# debug_backplane.net
KiCad netlist of a schematic drawn in EAGLE
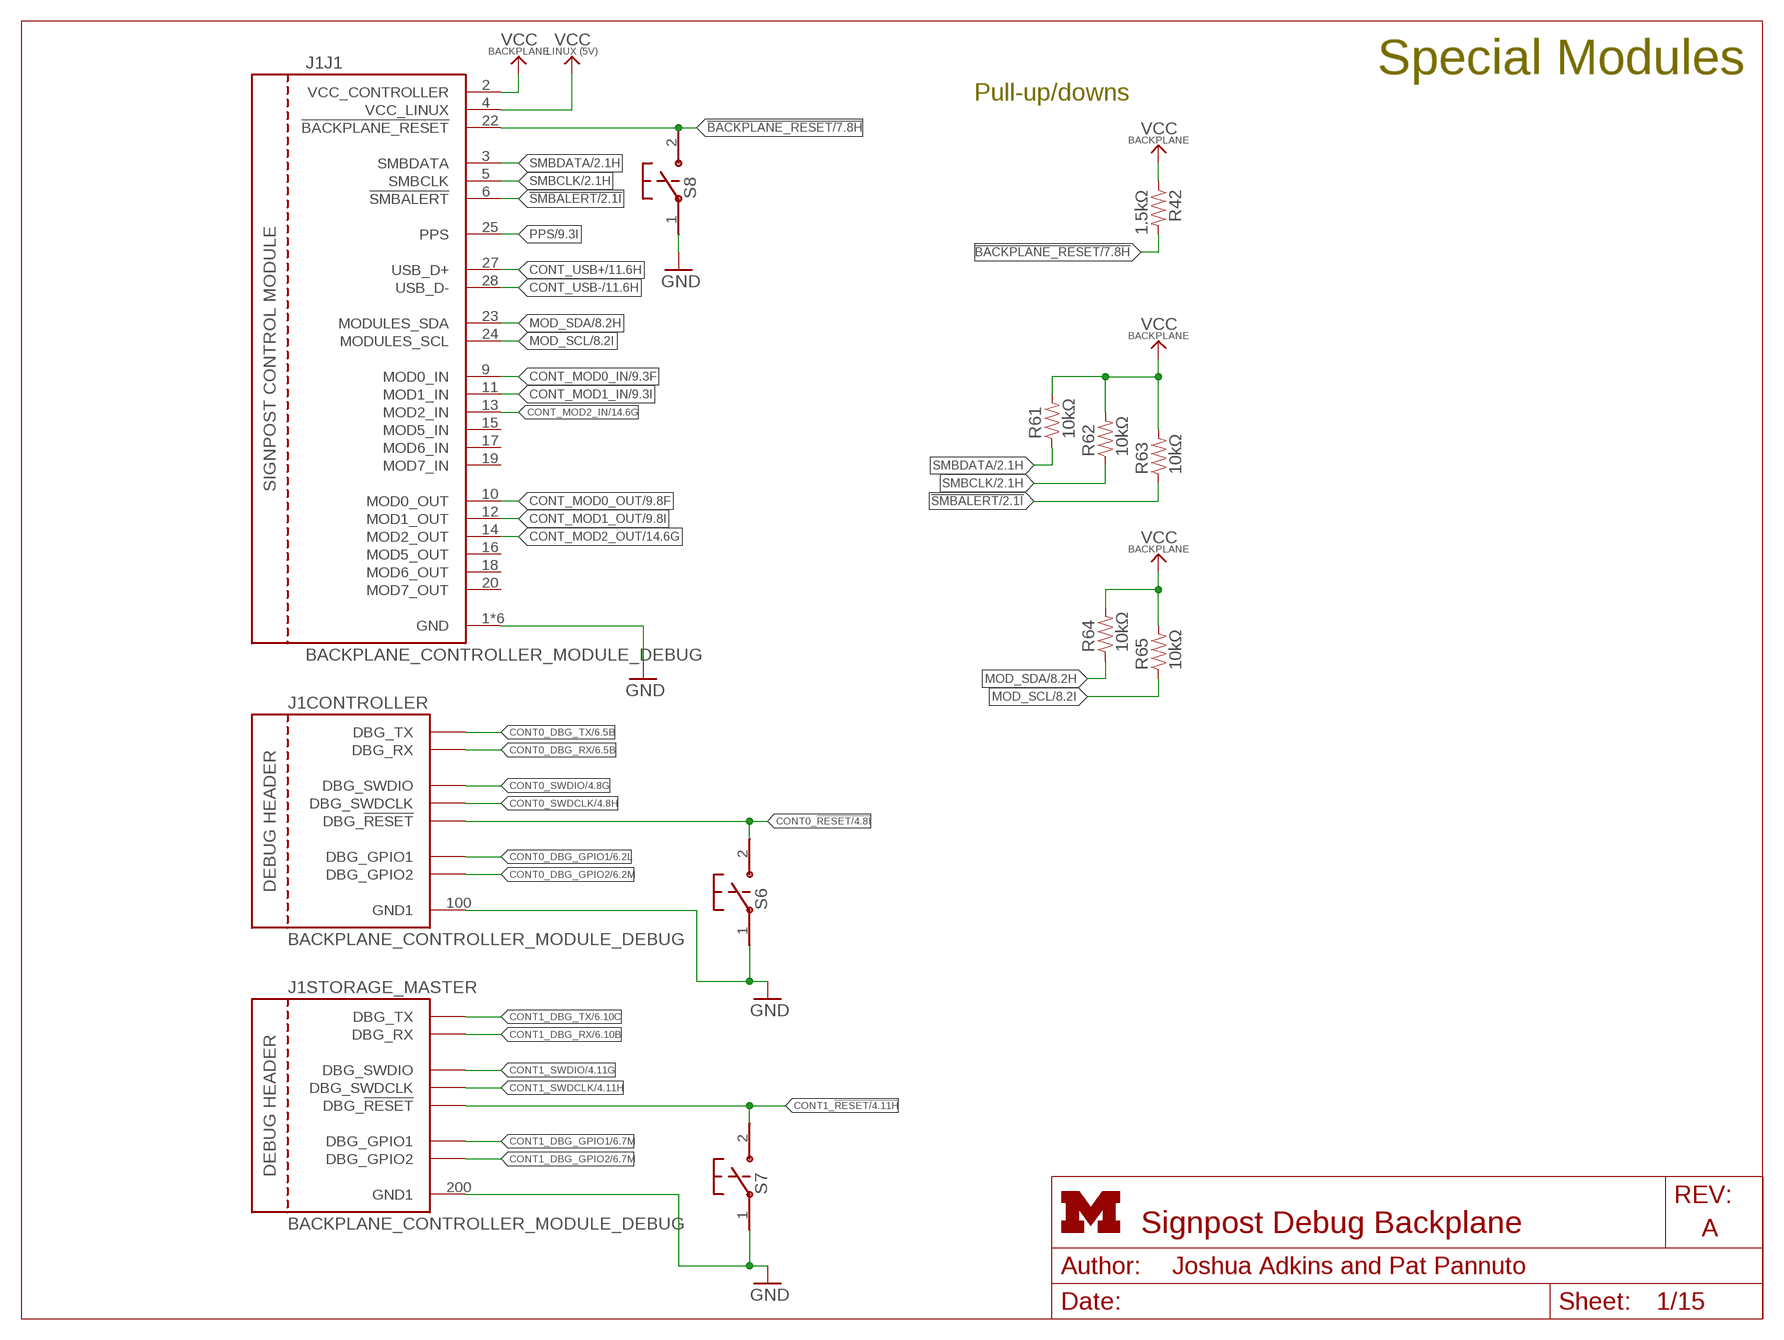
[diagram p0: schematic, sheet 1]
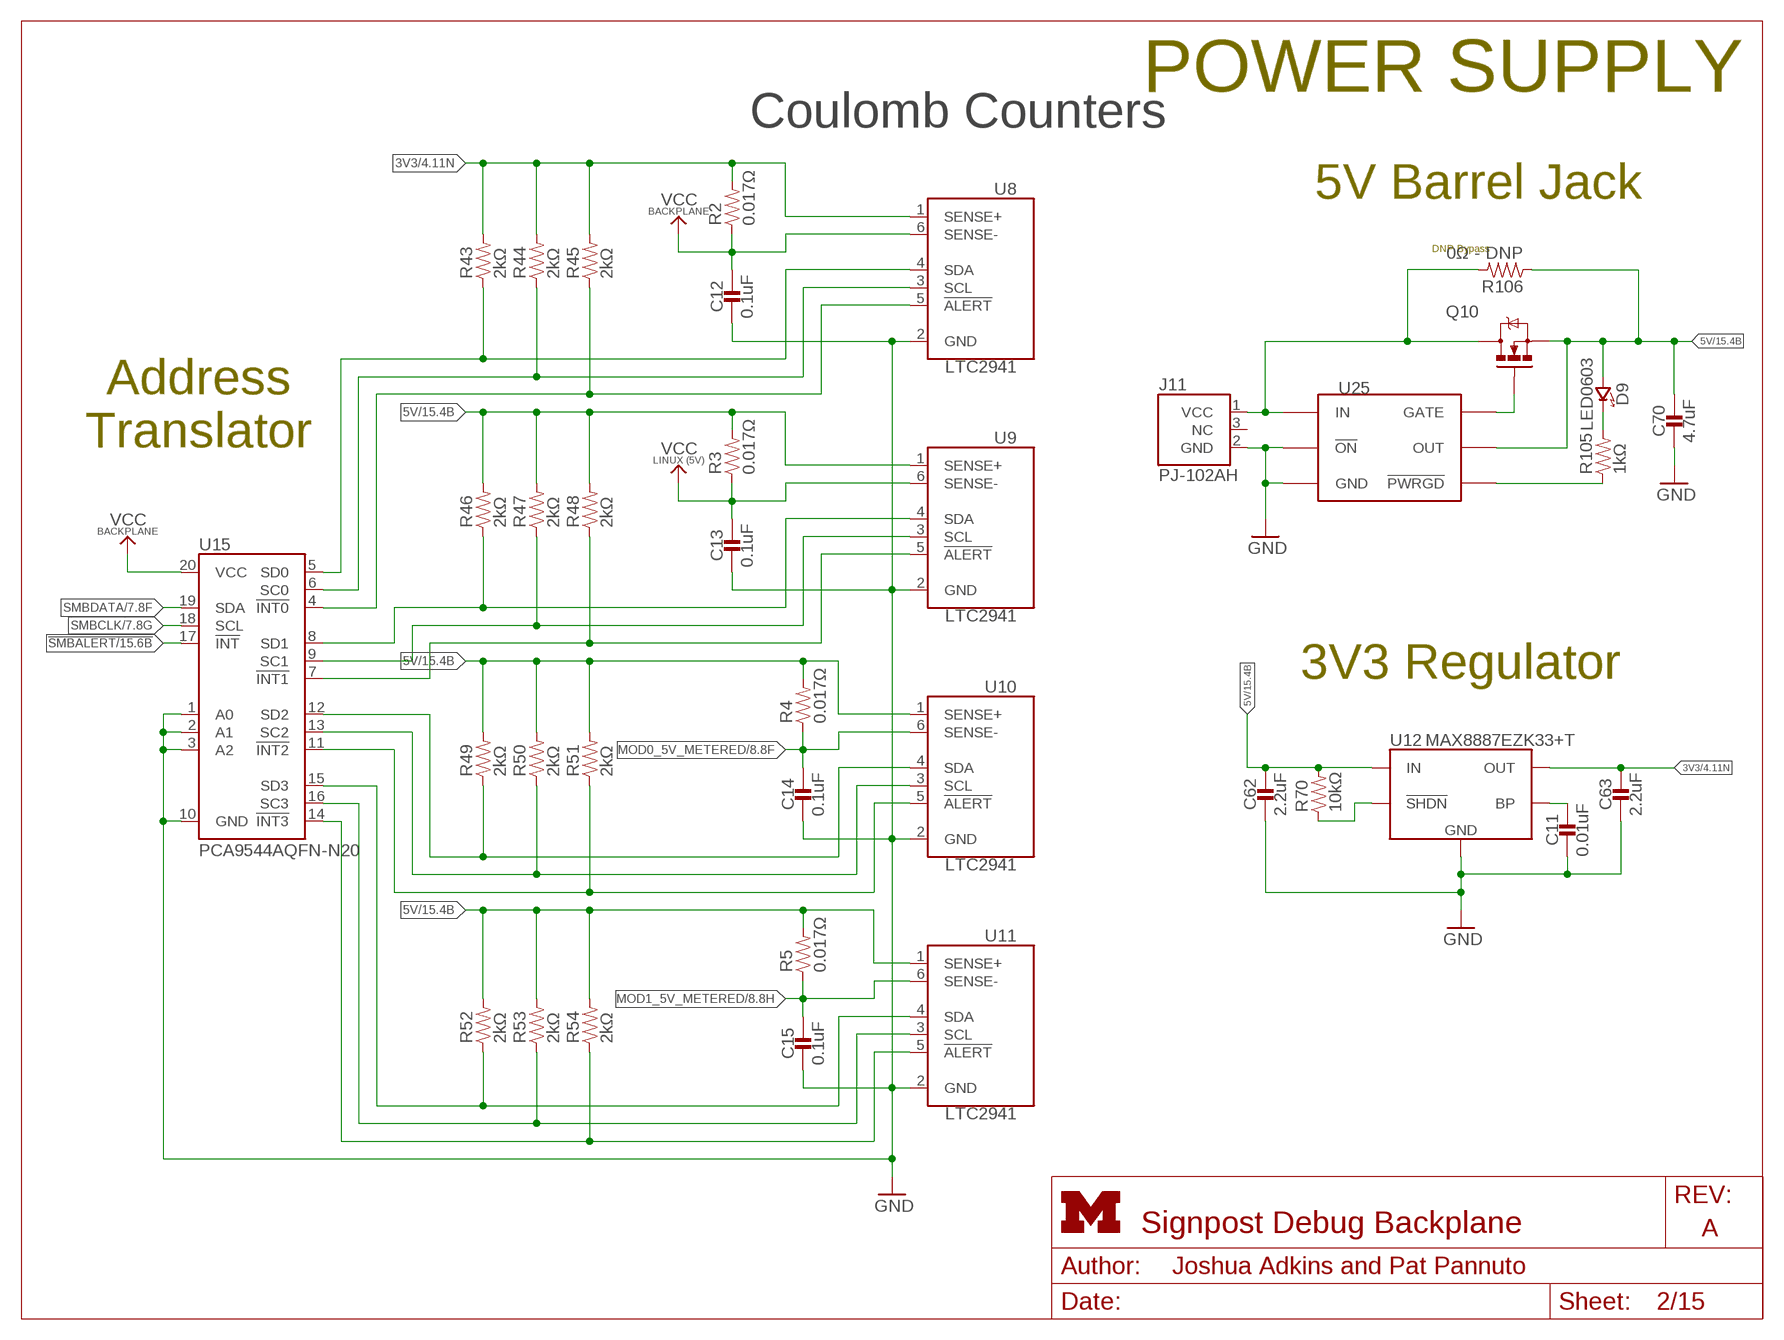
[diagram p1: schematic, sheet 2]
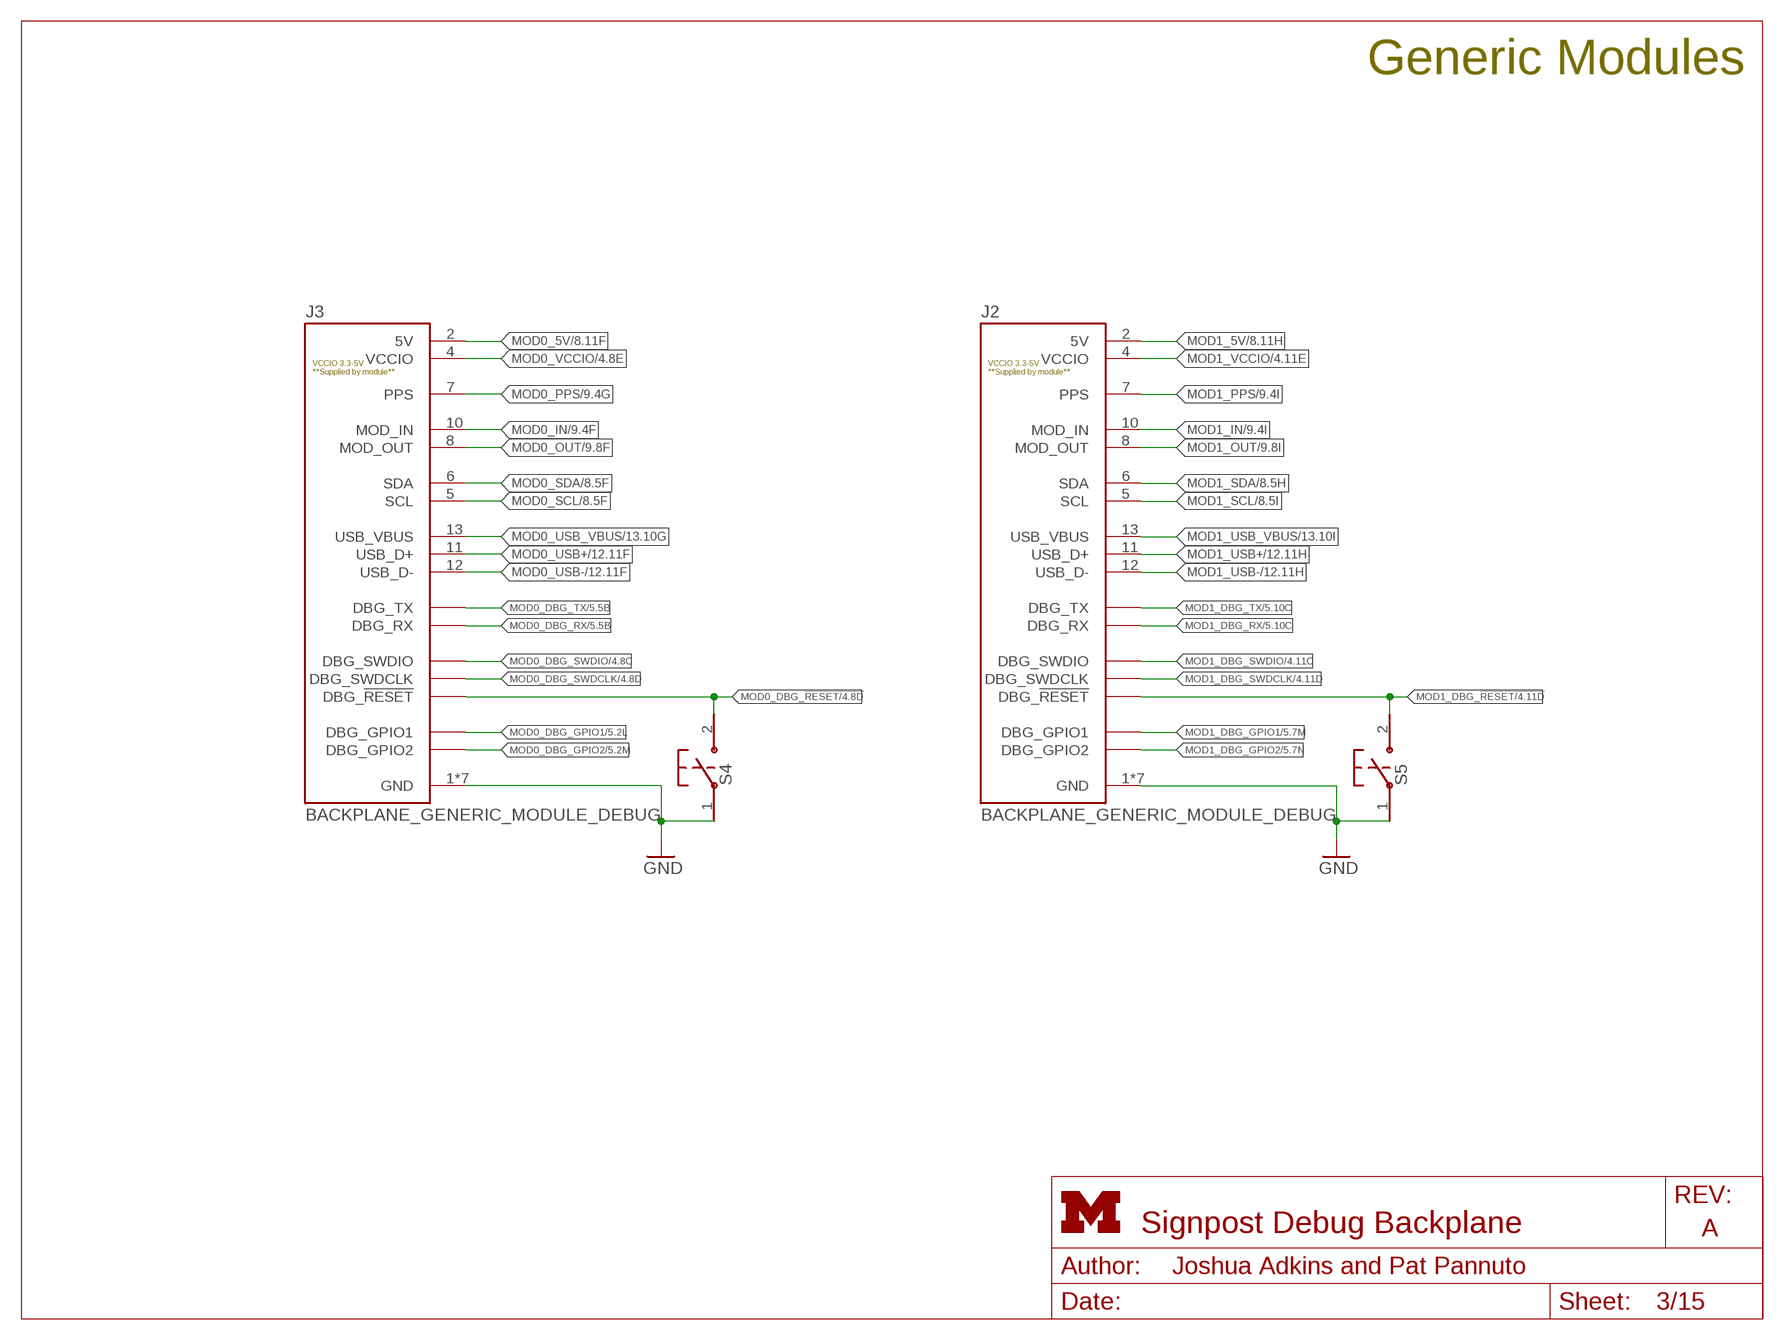
[diagram p2: schematic, sheet 3]
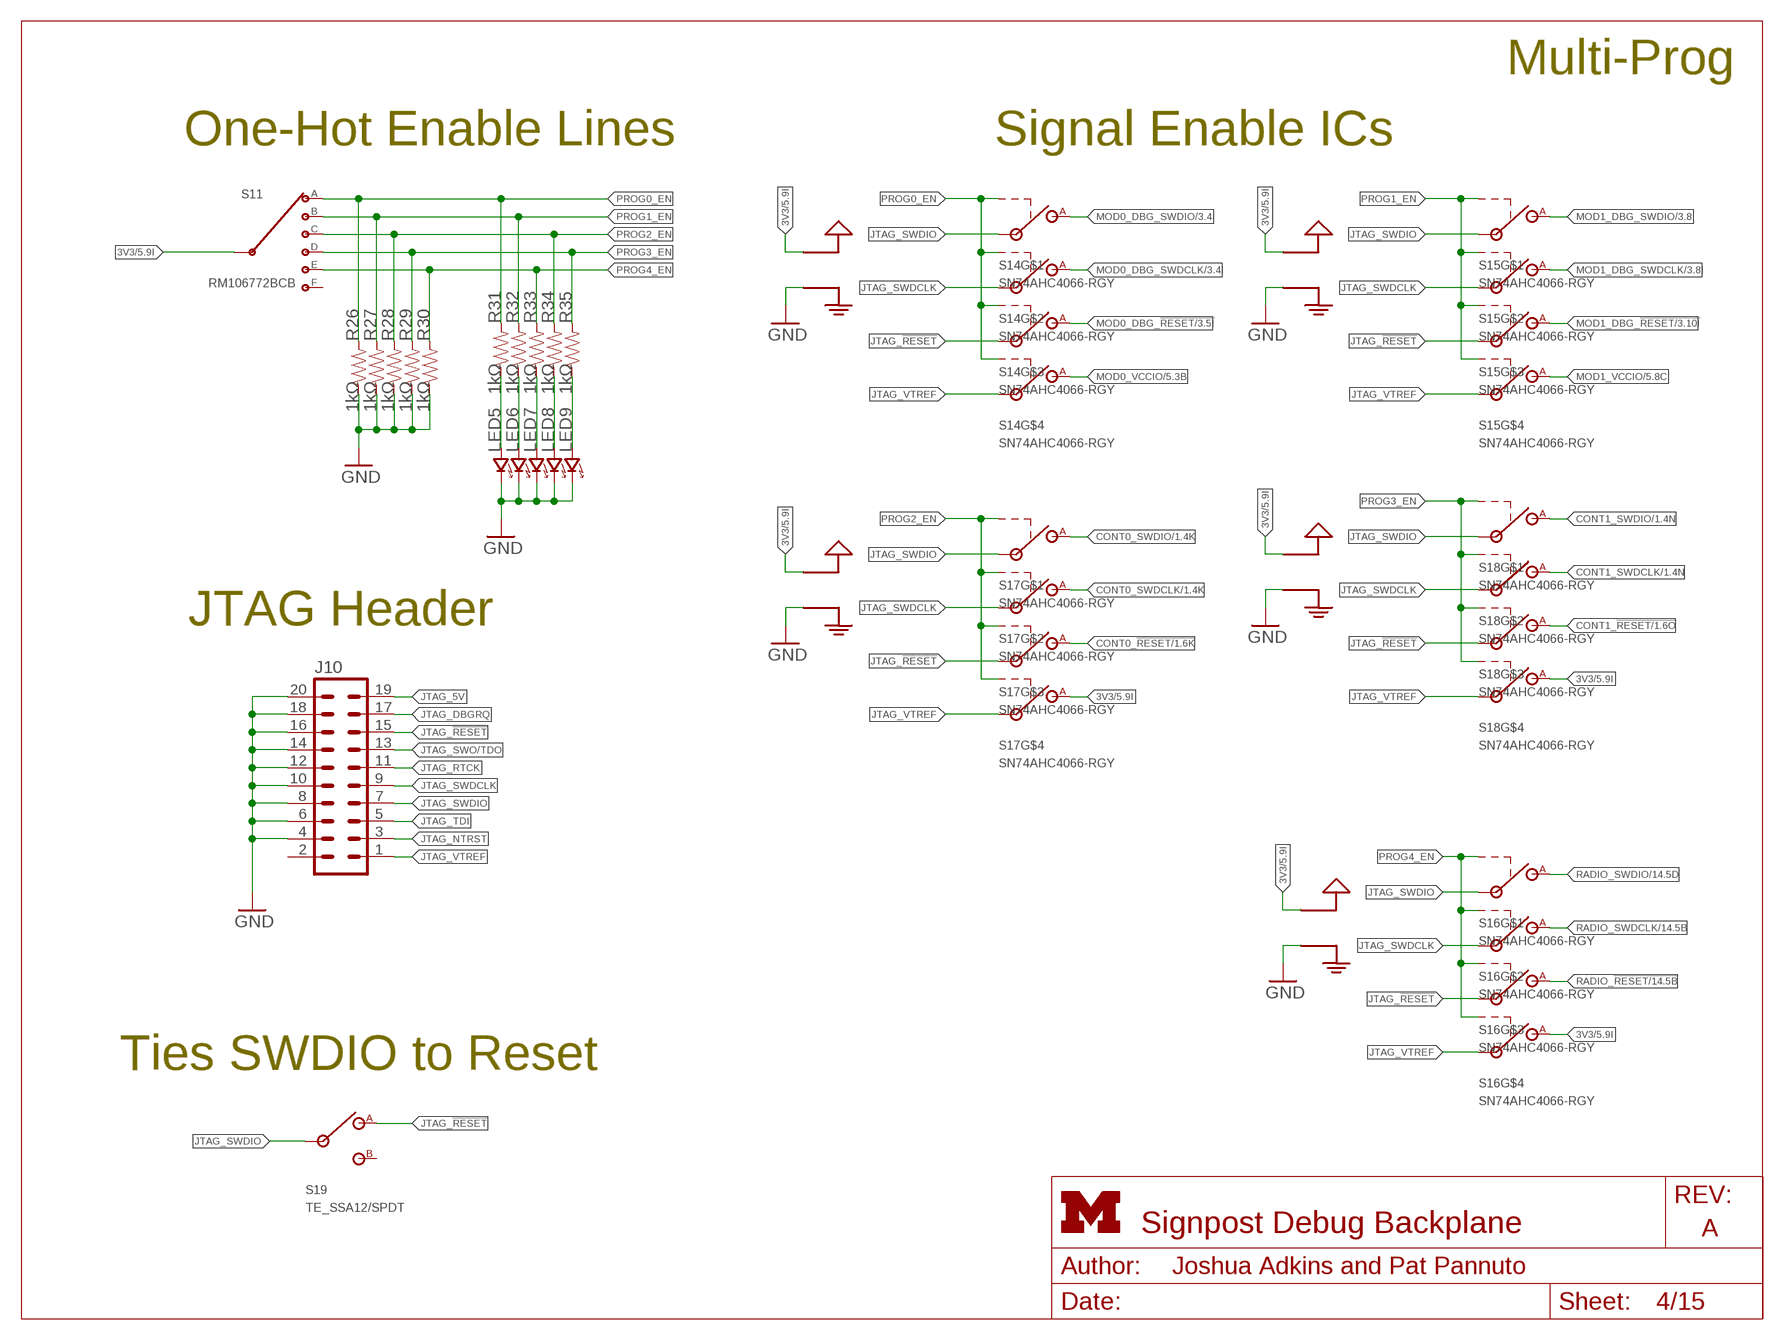
[diagram p3: schematic, sheet 4]
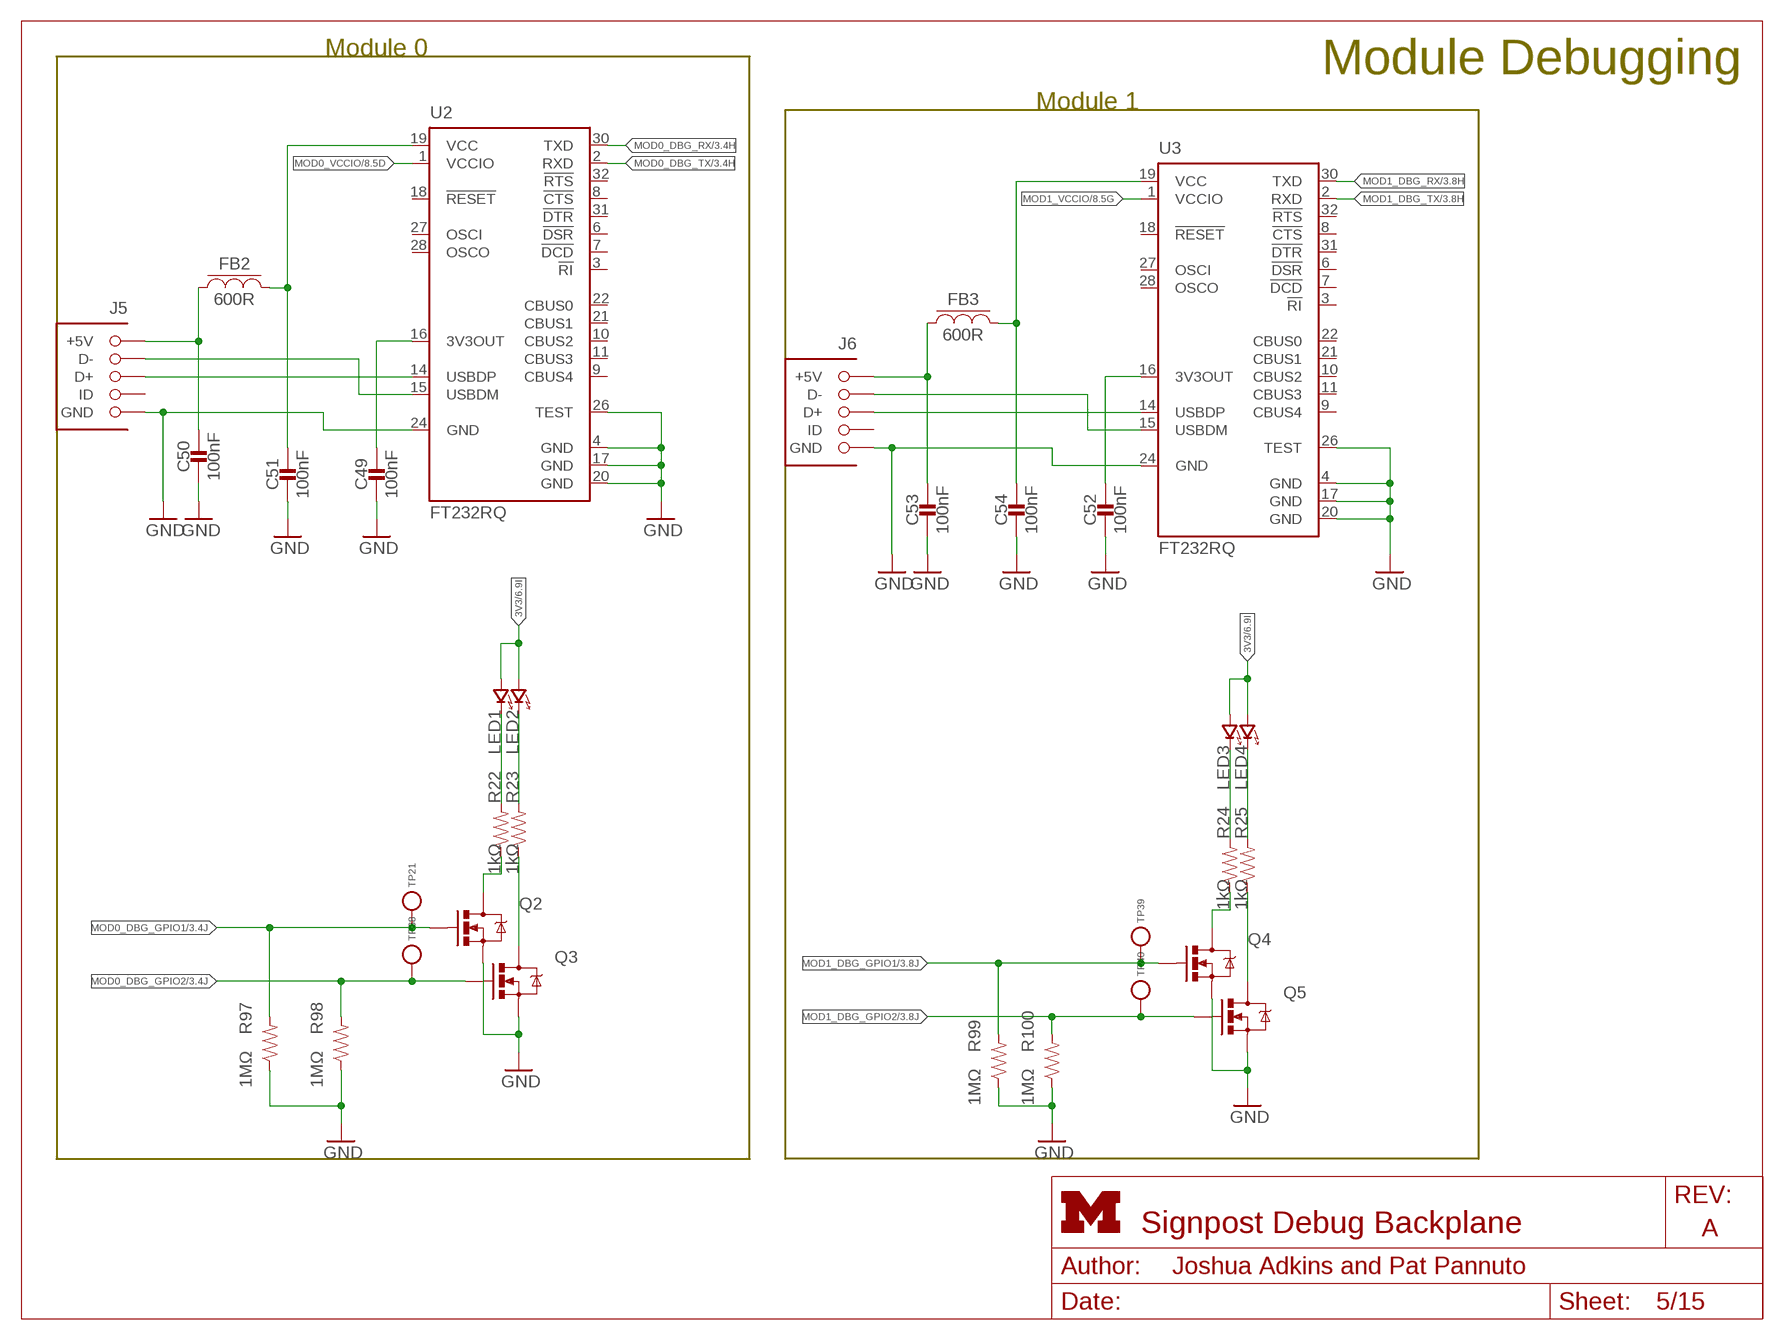
[diagram p4: schematic, sheet 5]
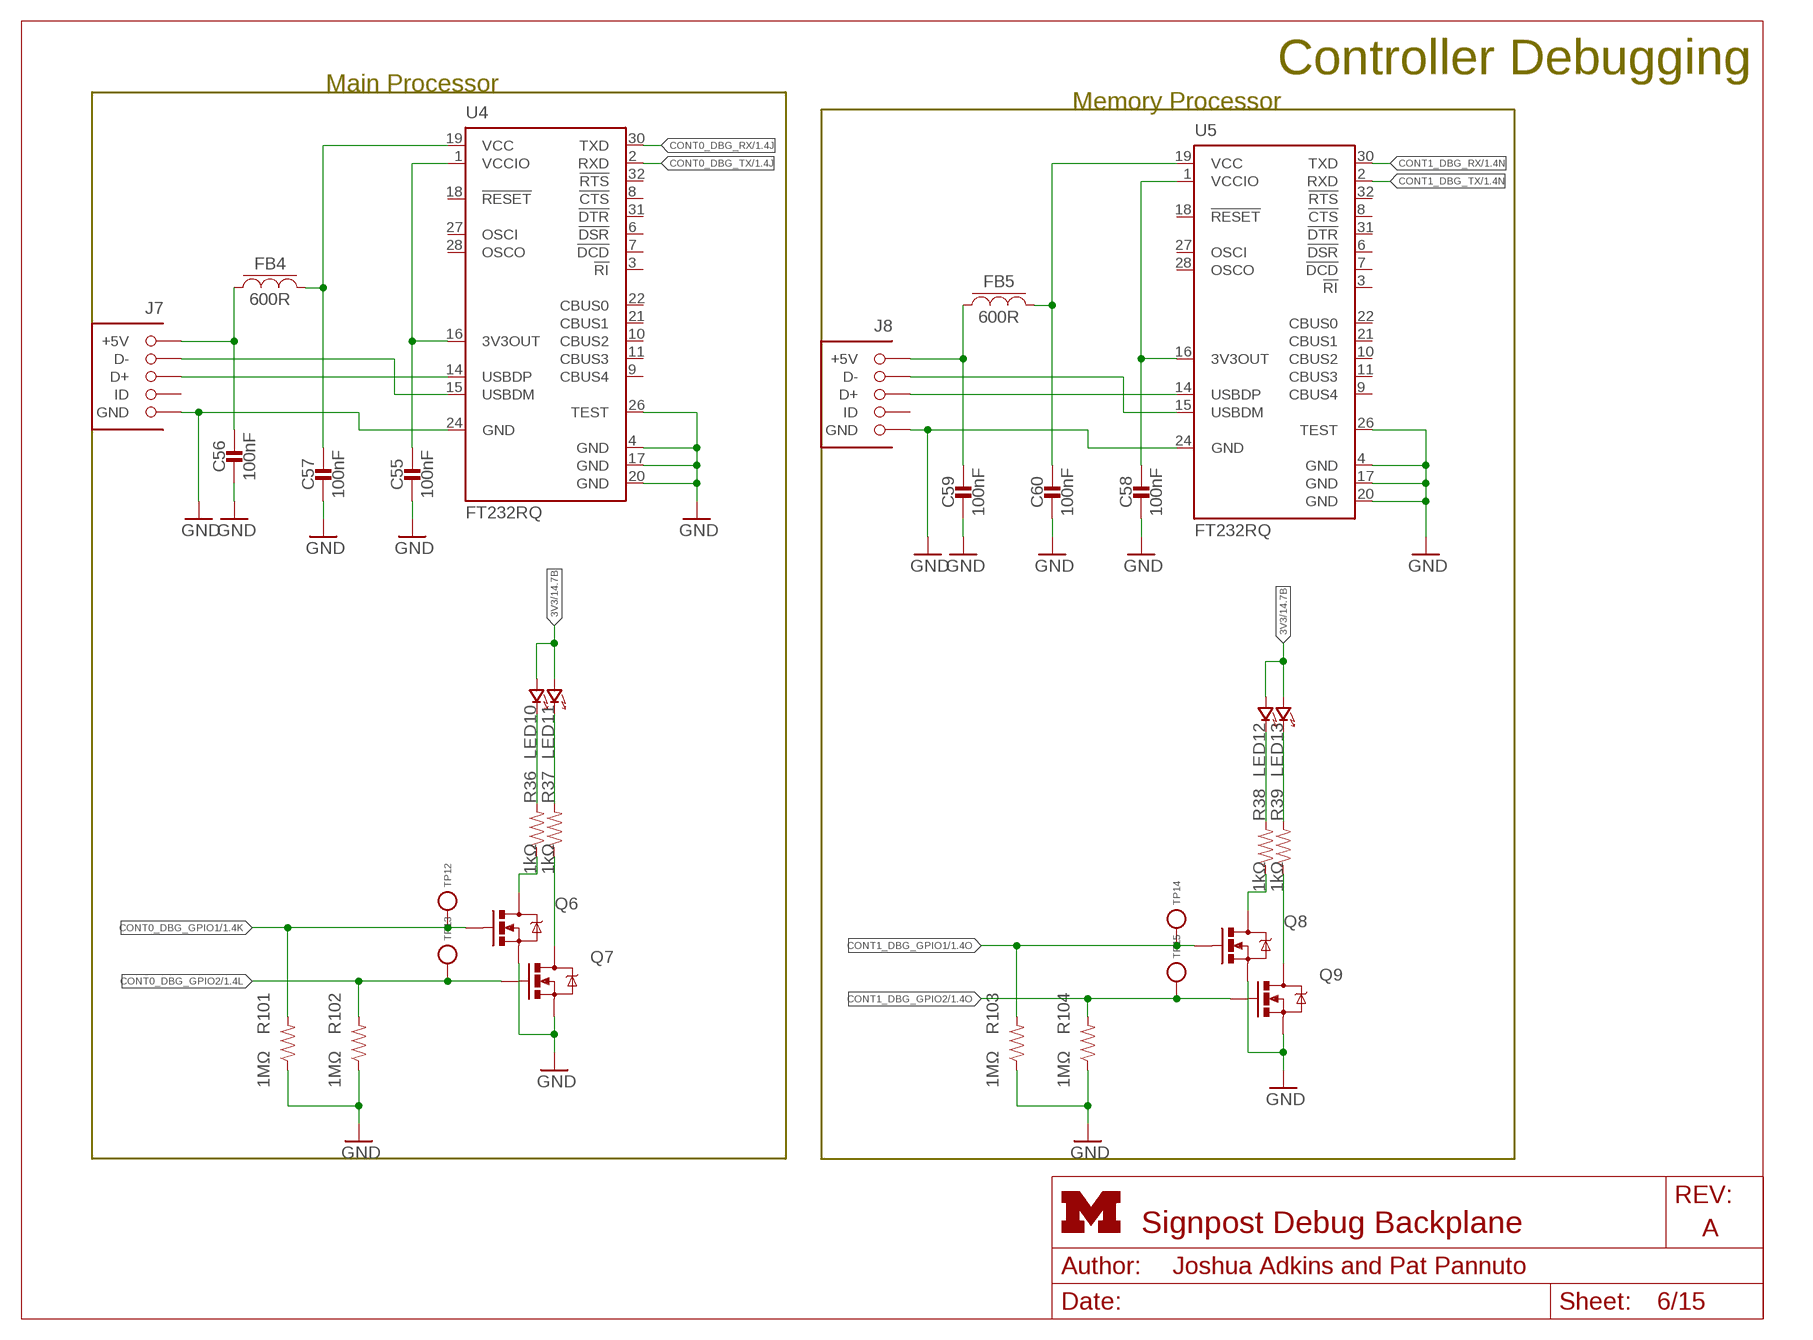
[diagram p5: schematic, sheet 6]
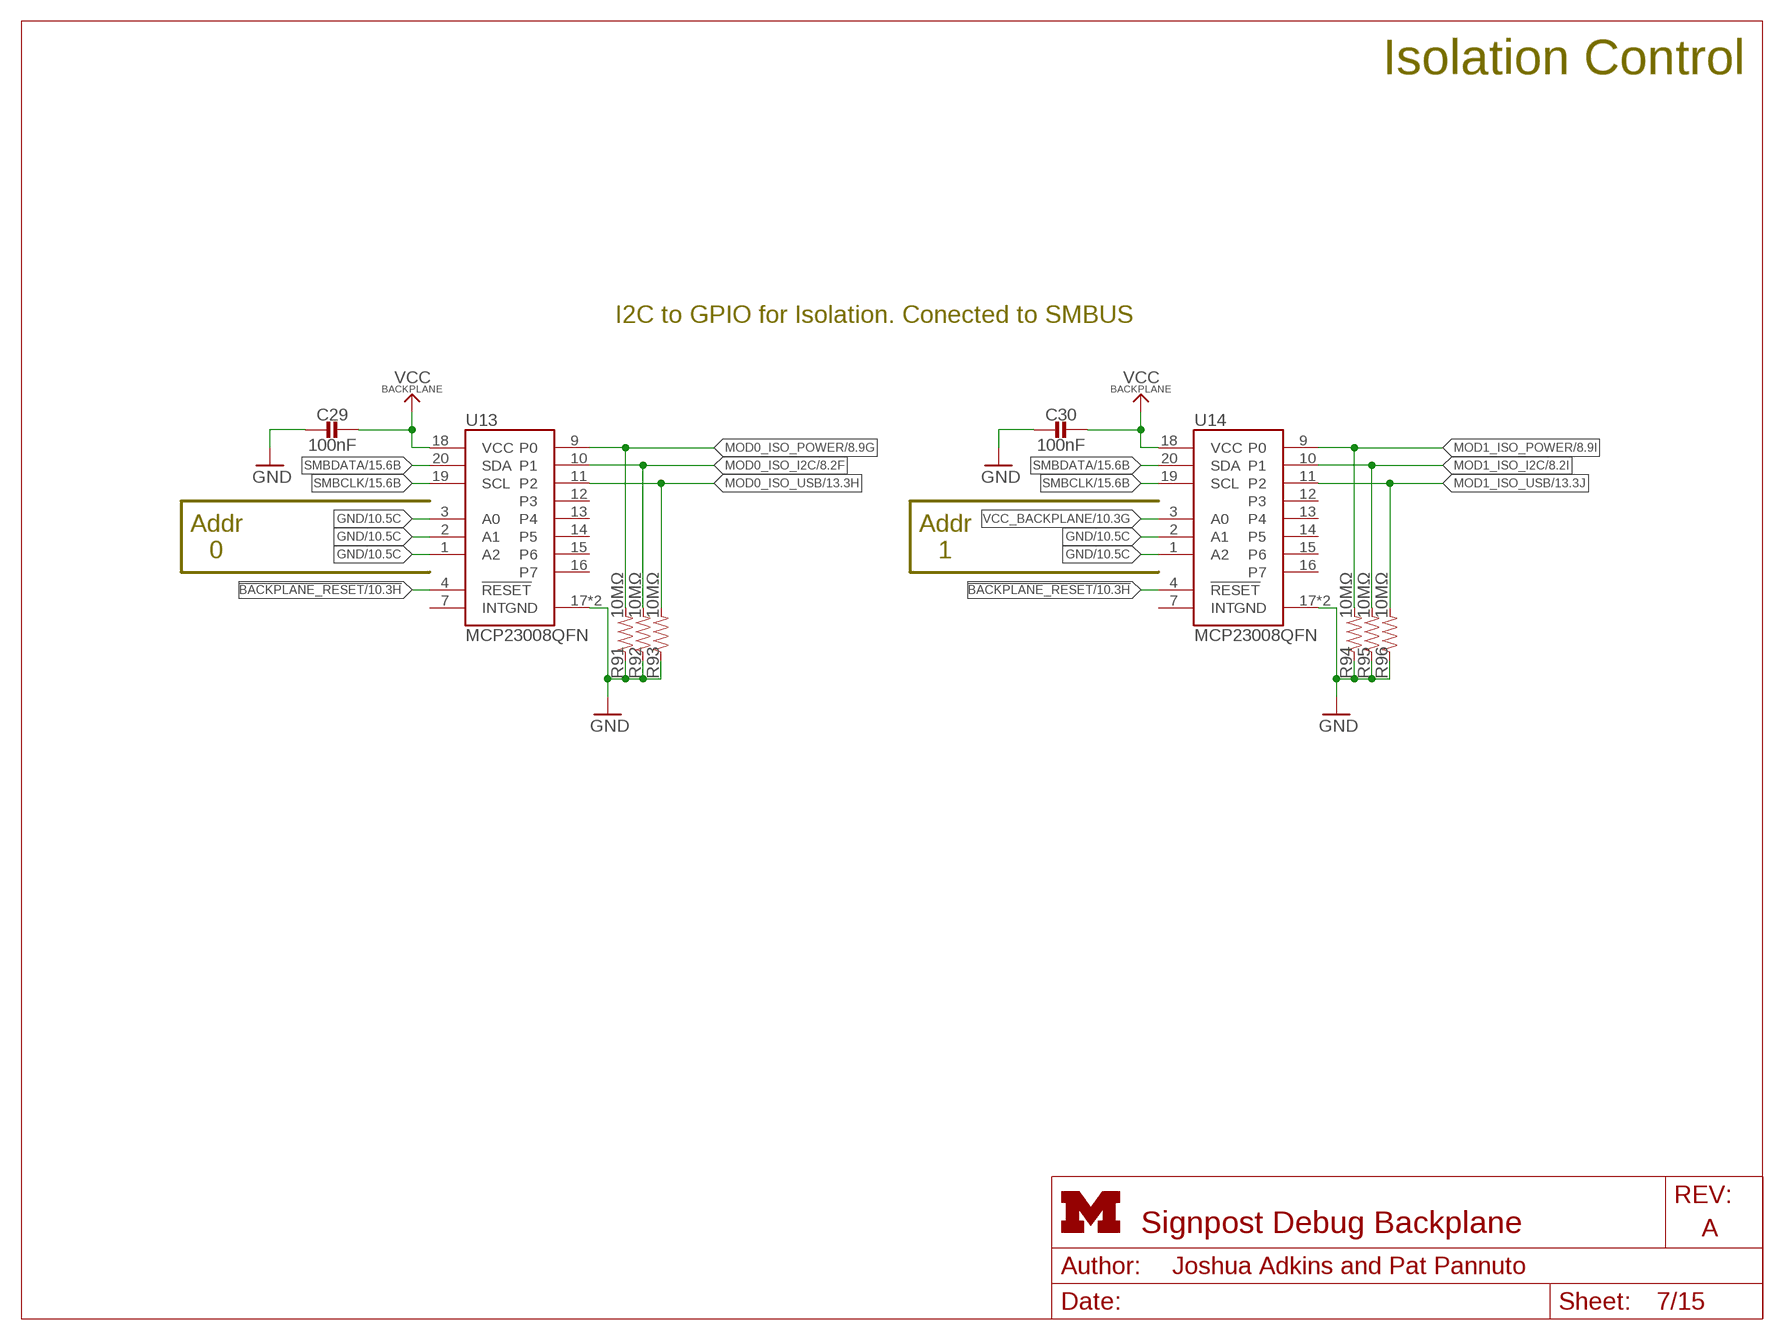
[diagram p6: schematic, sheet 7]
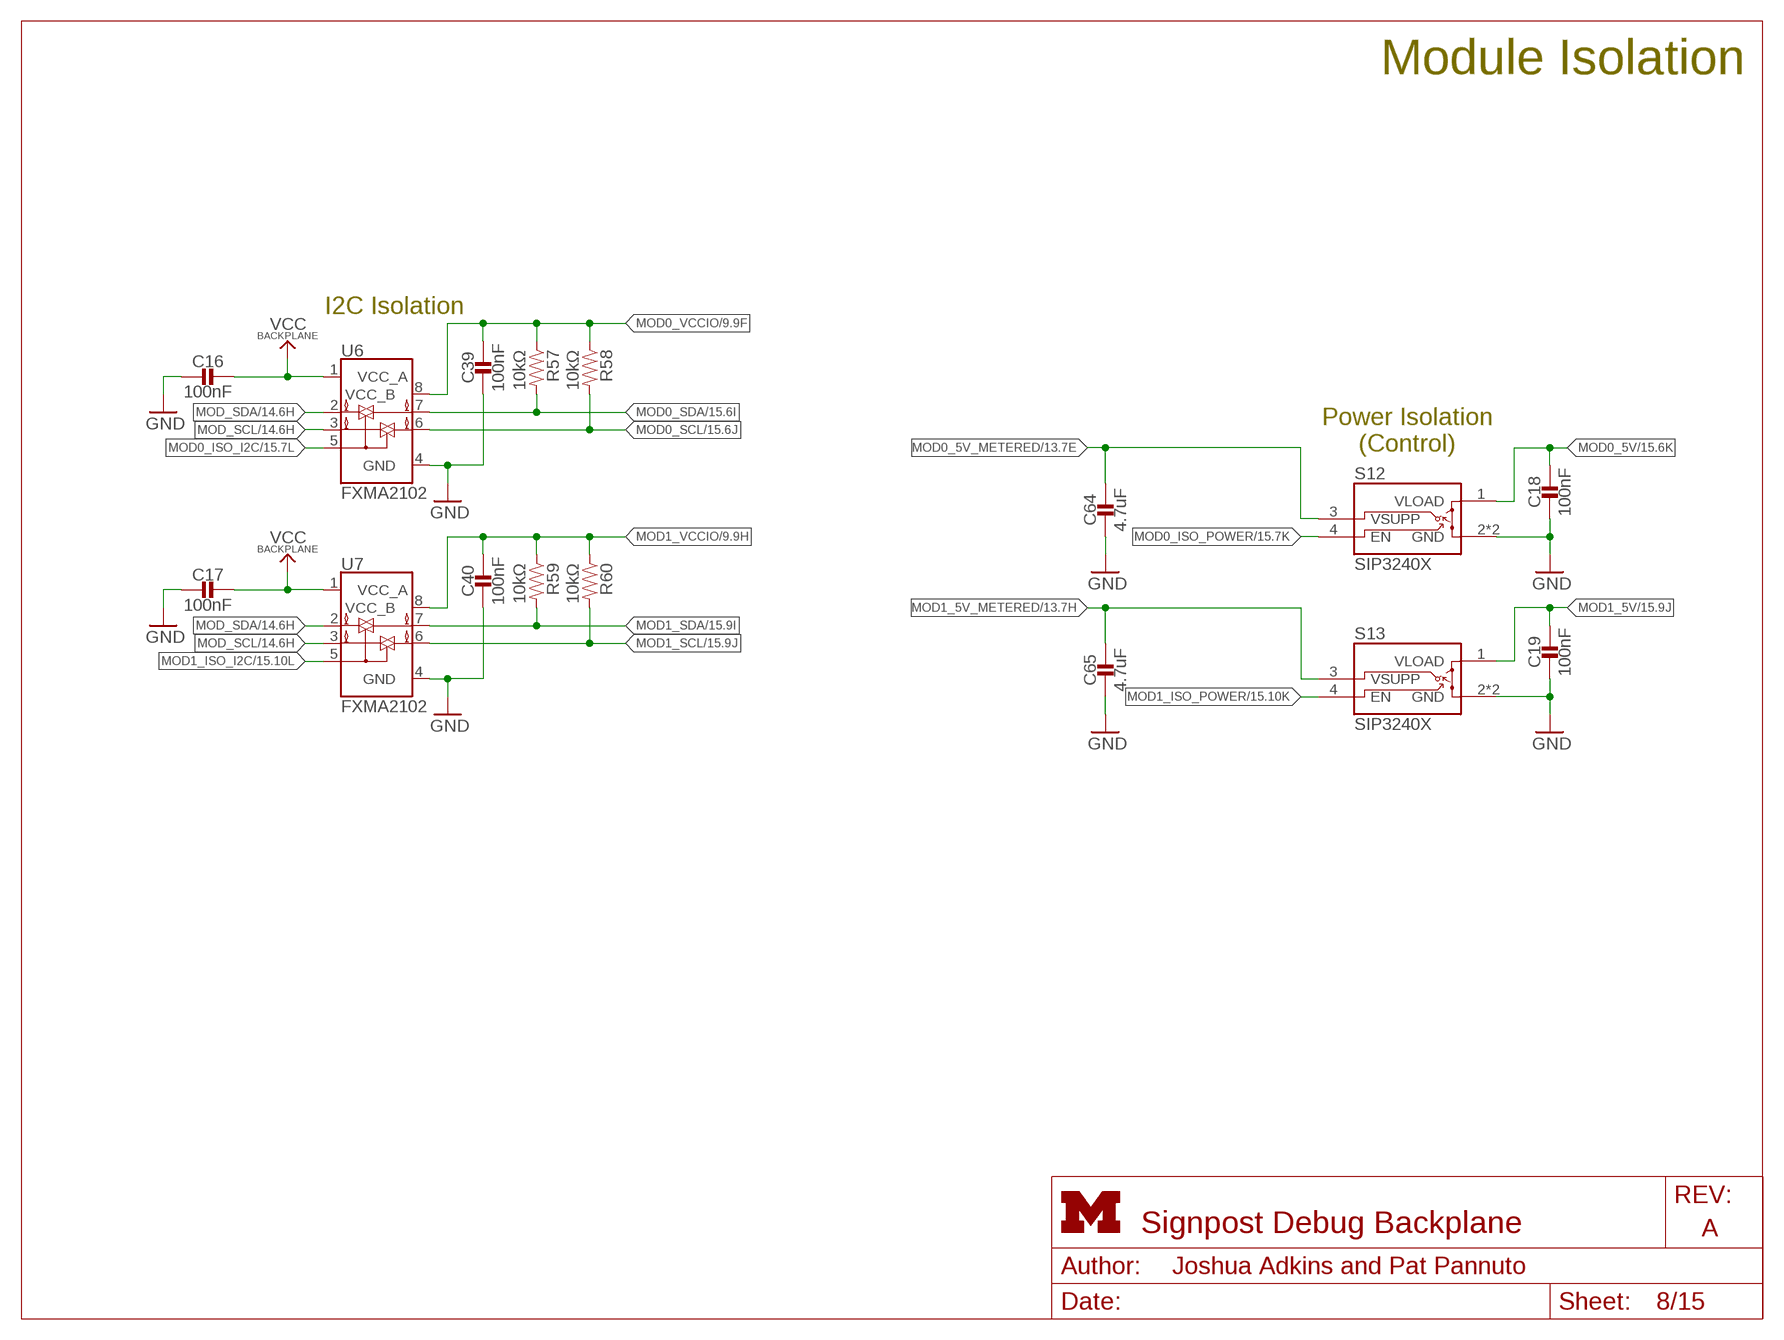
[diagram p7: schematic, sheet 8]
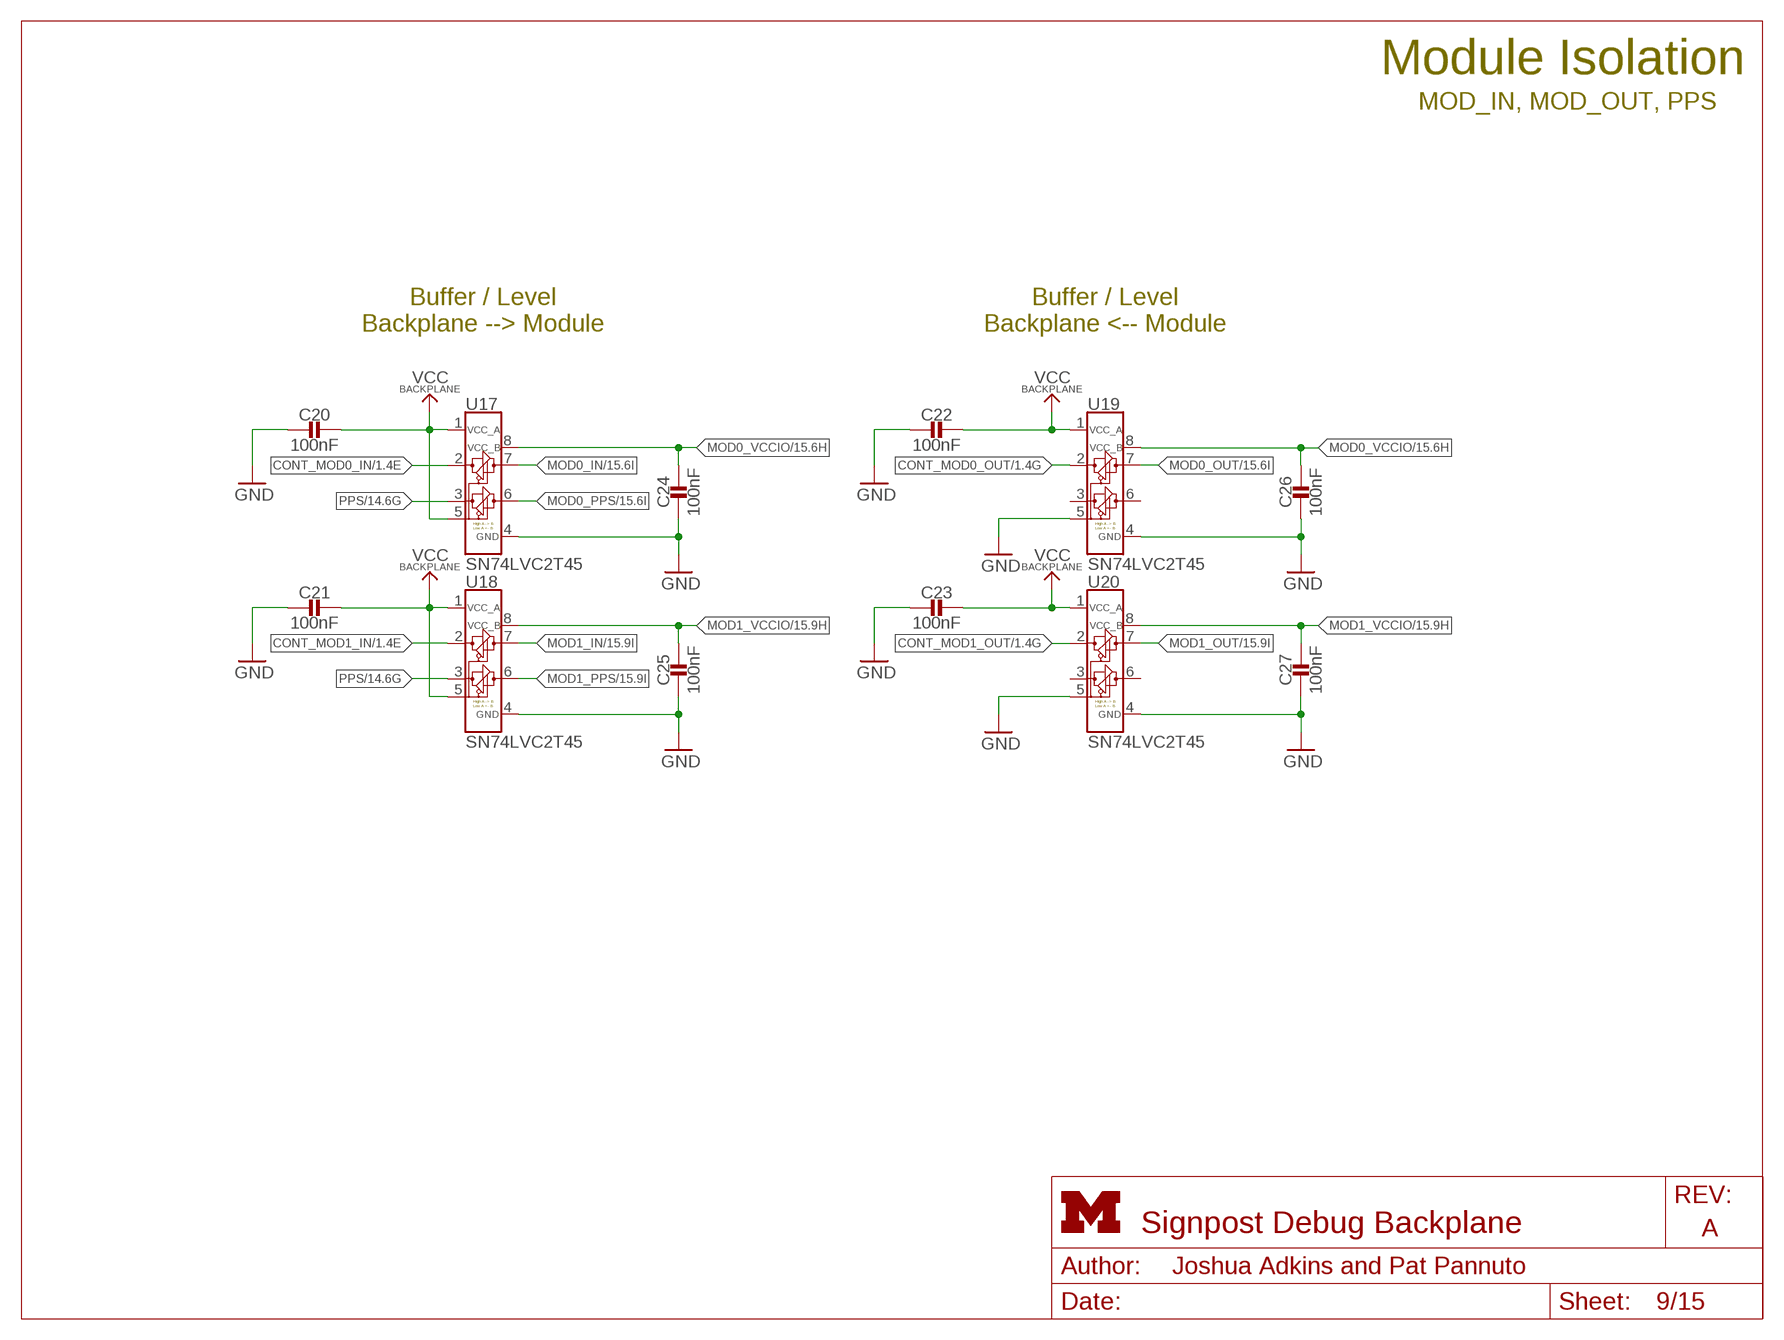
[diagram p8: schematic, sheet 9]
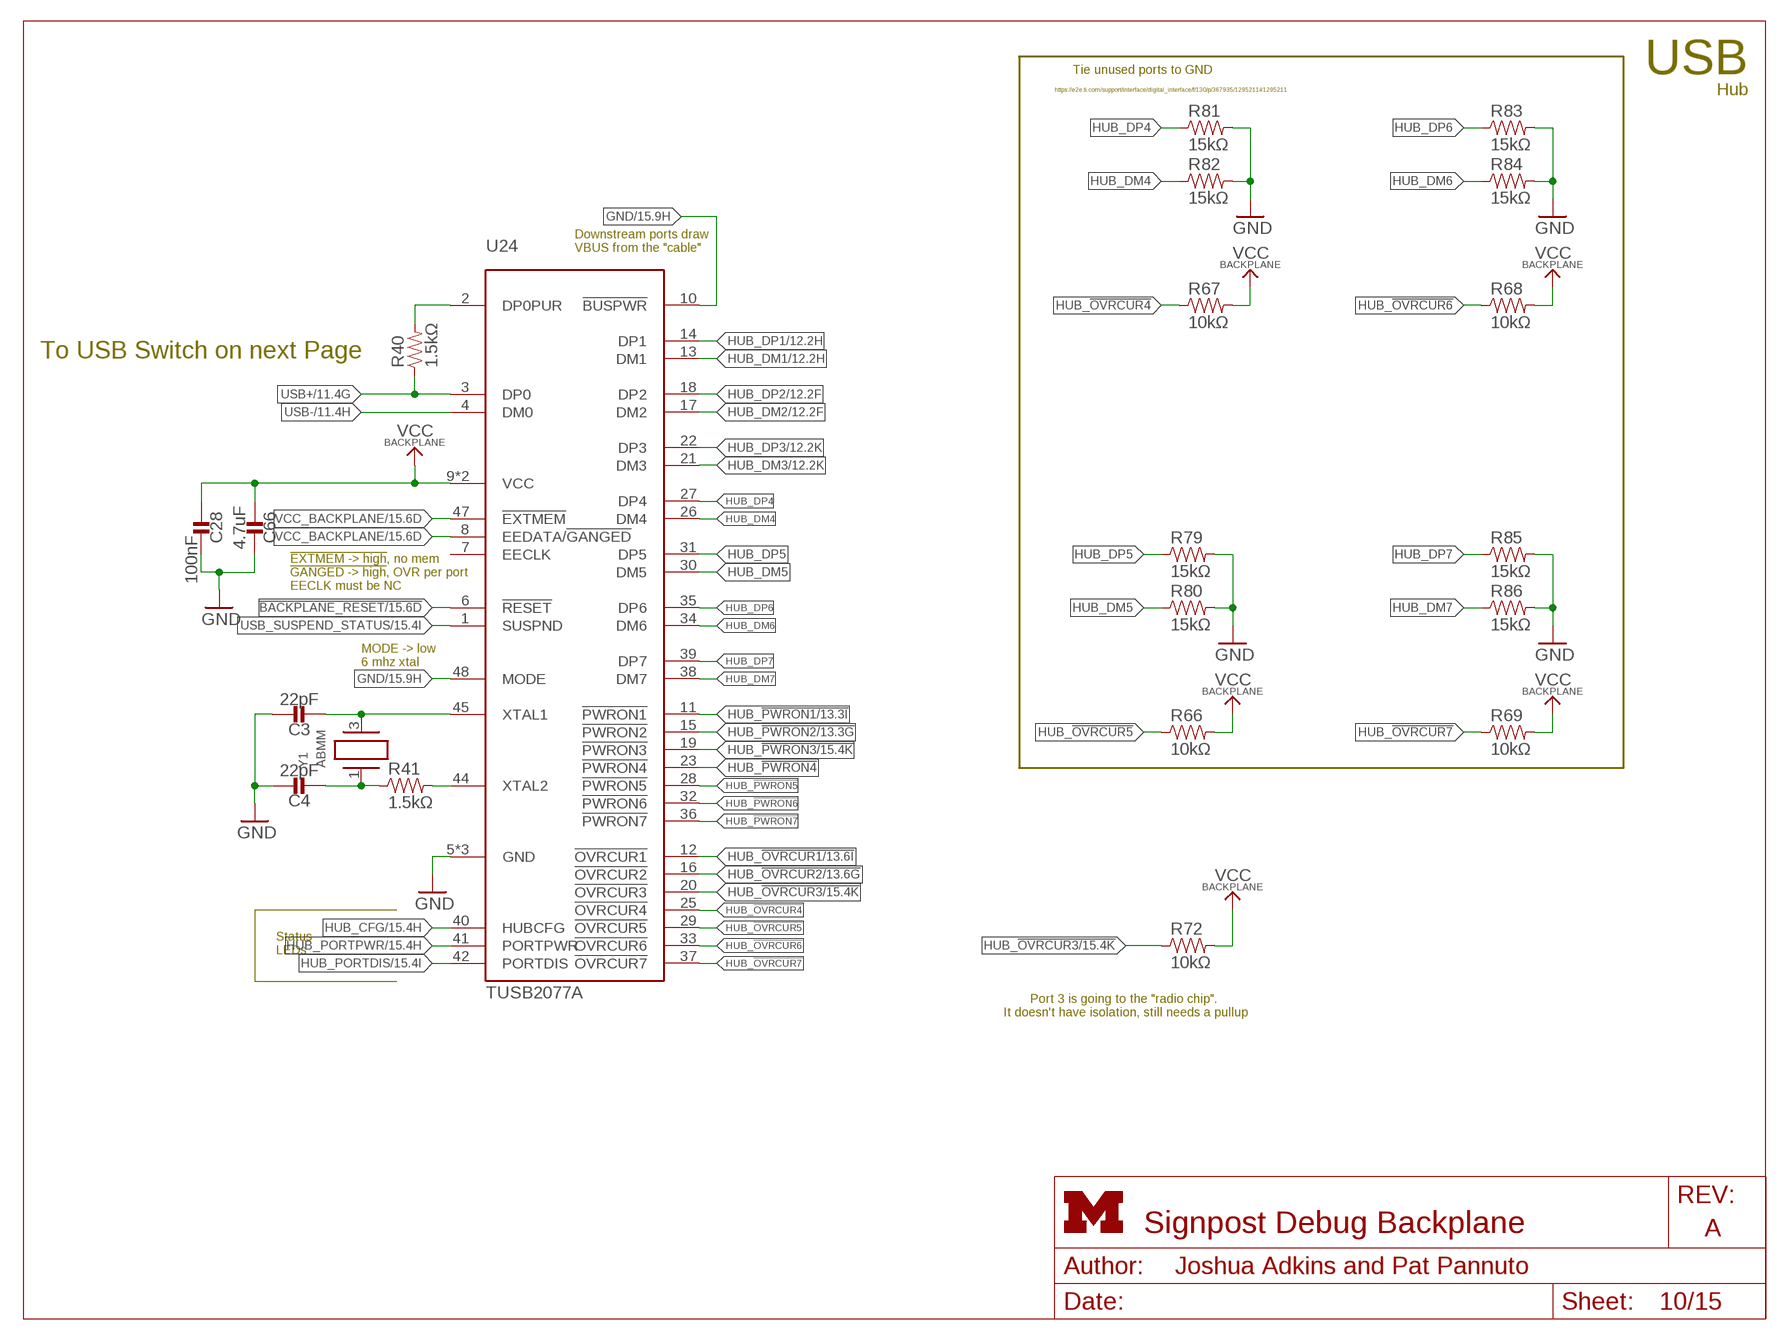
[diagram p9: schematic, sheet 10]
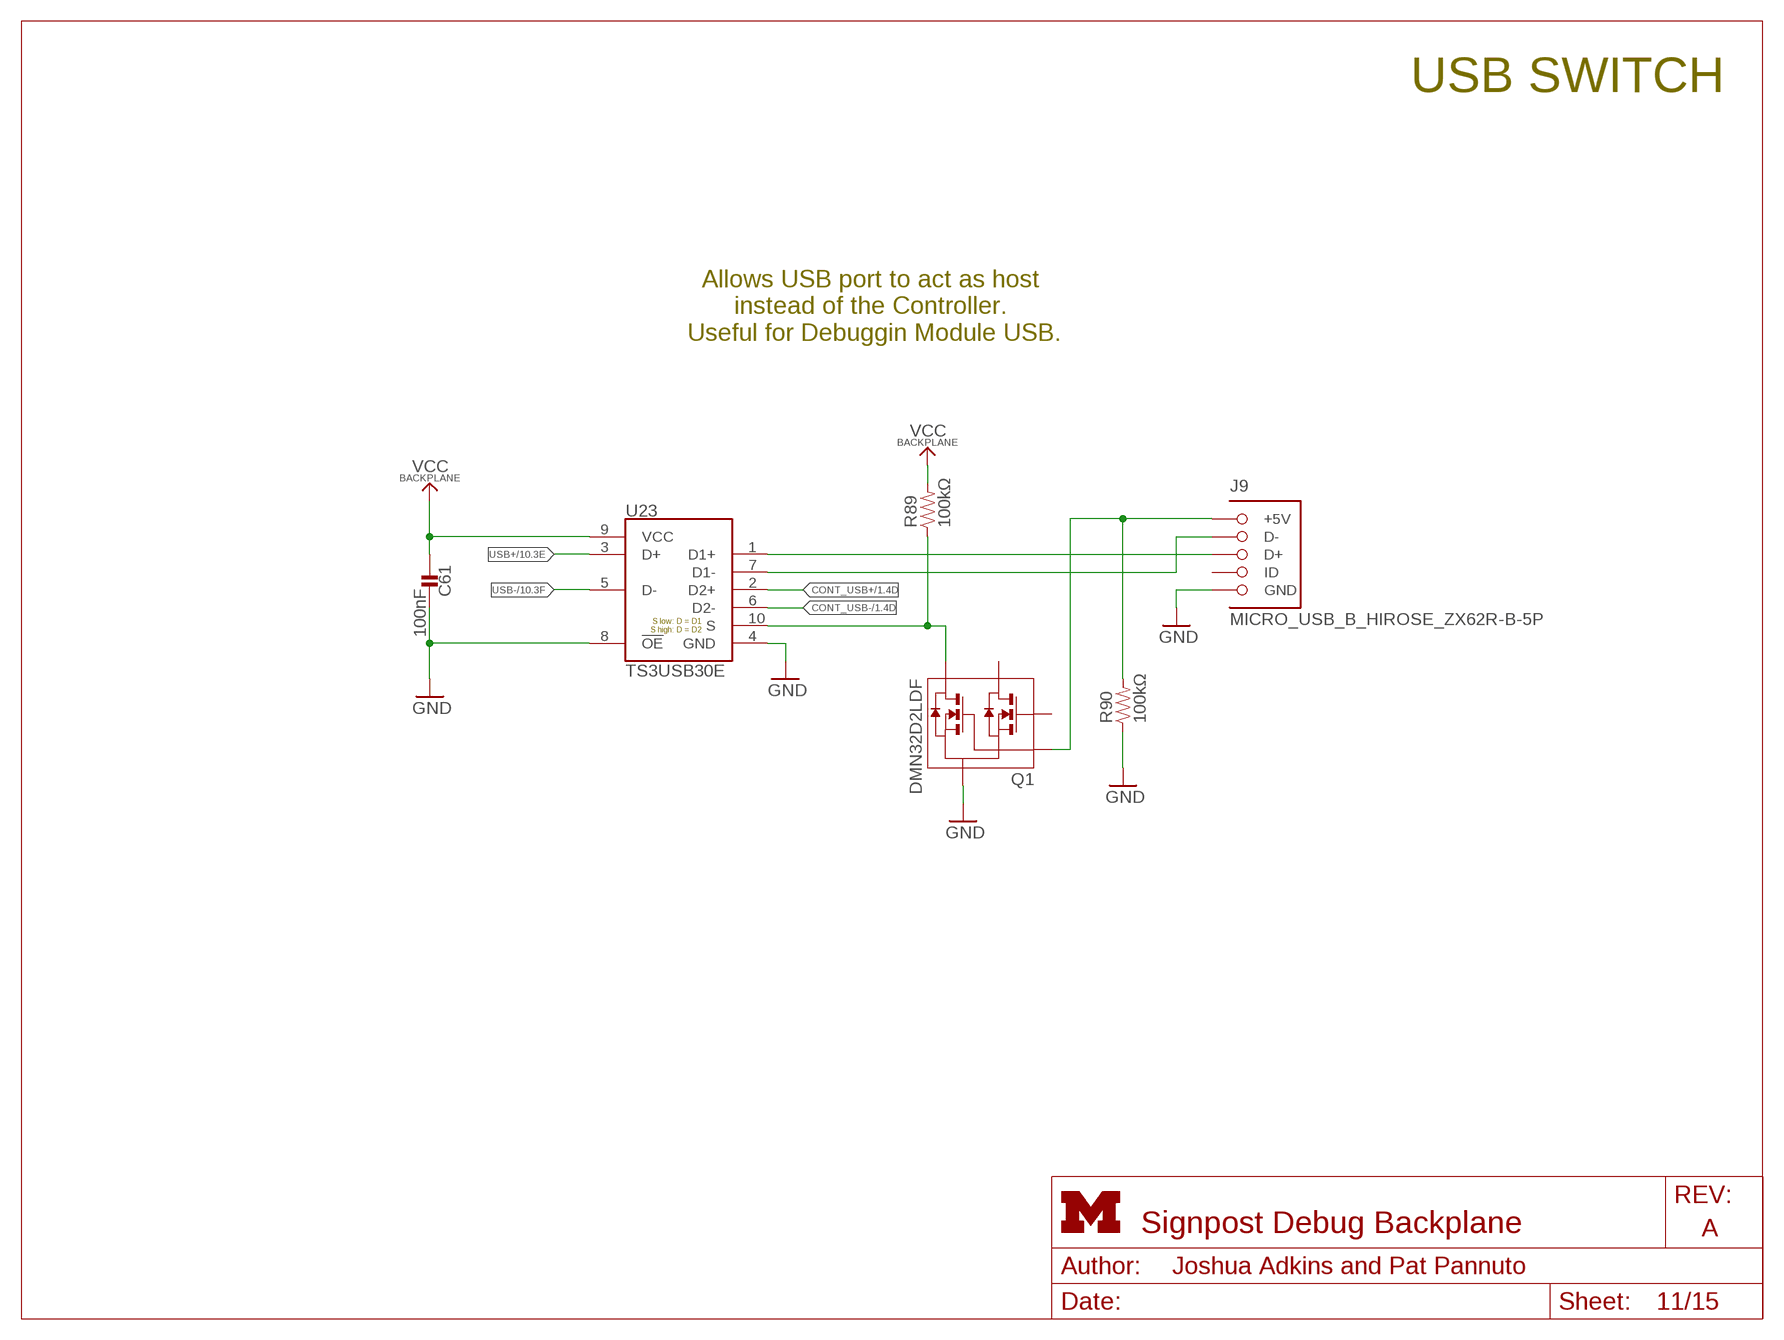
[diagram p10: schematic, sheet 11]
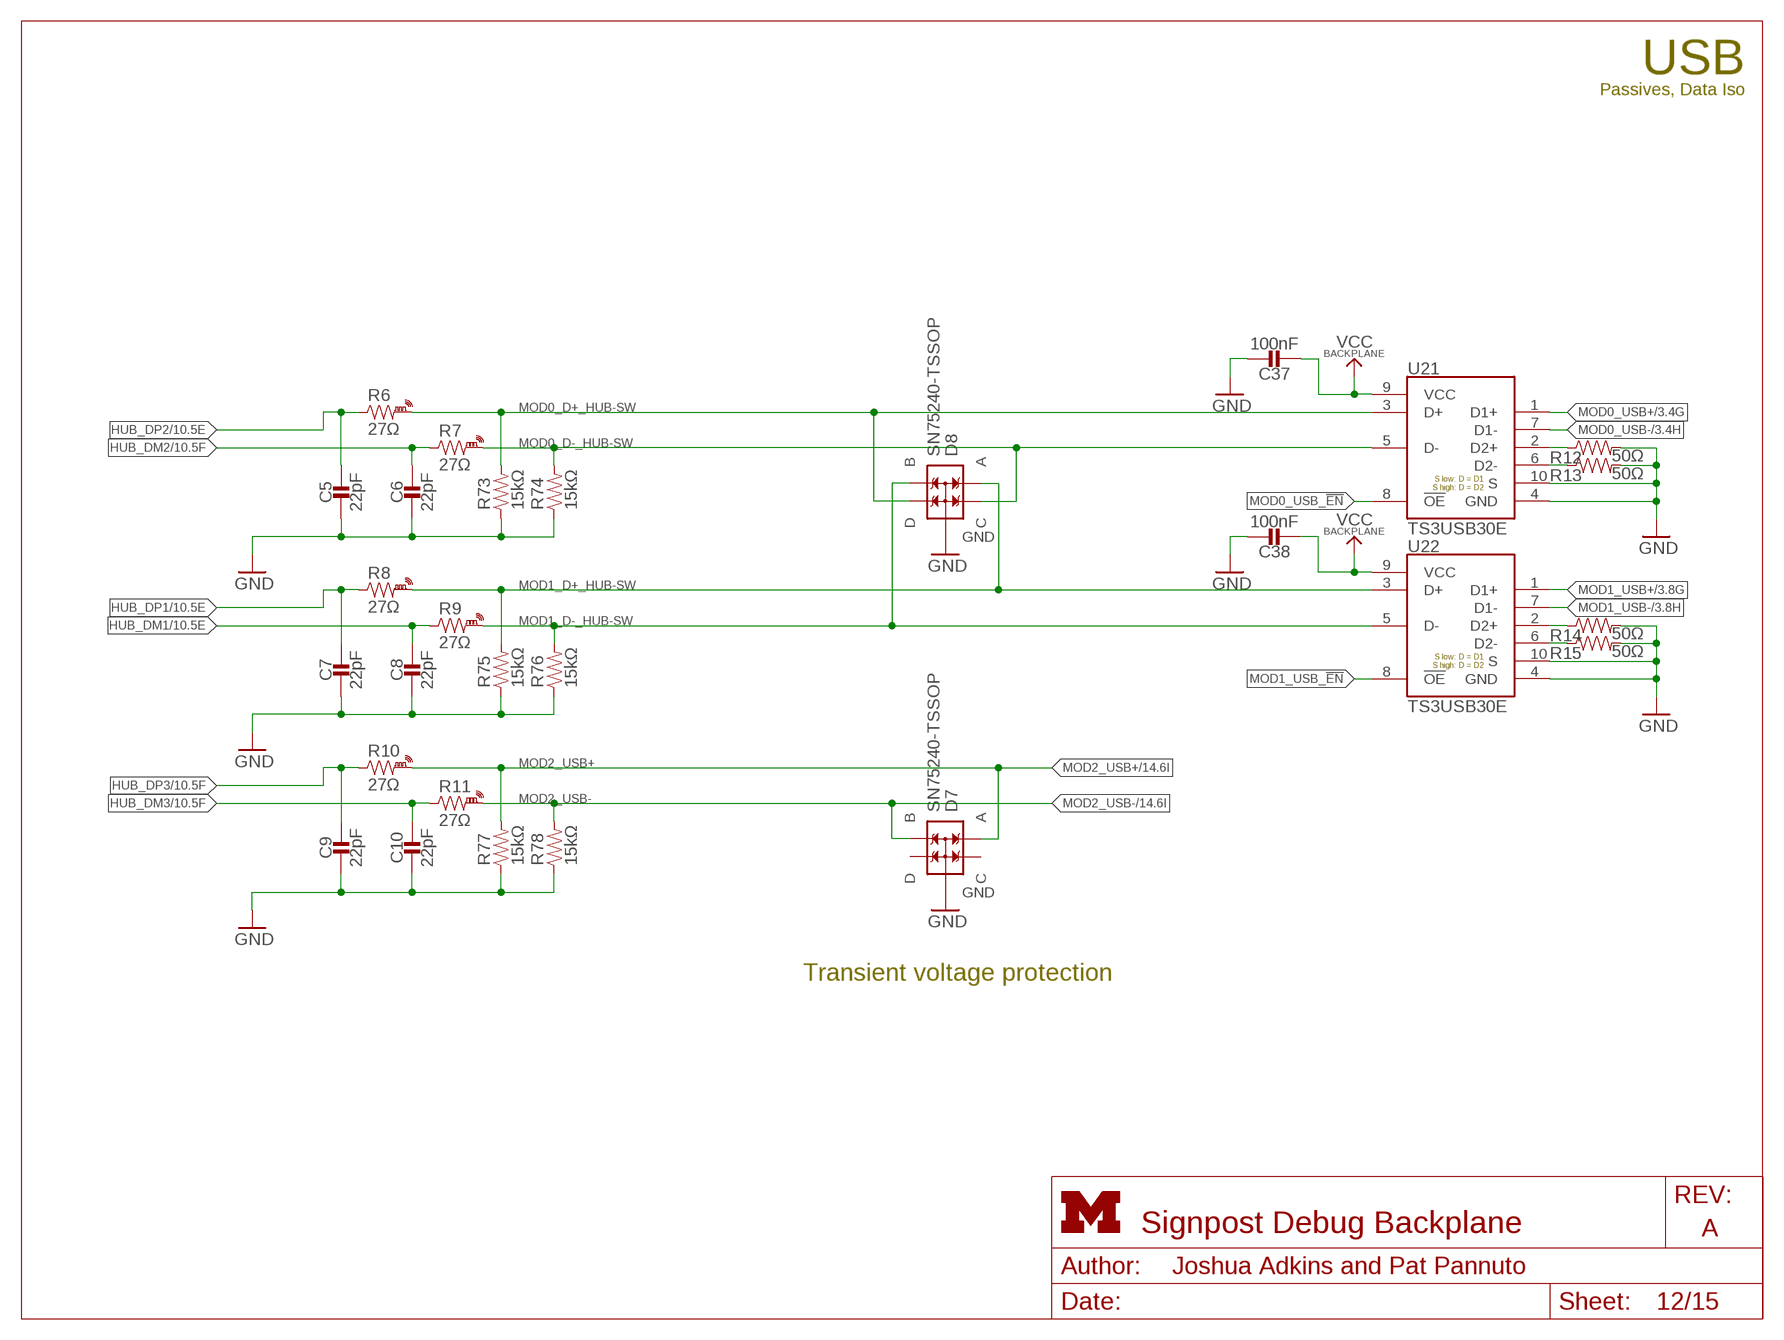
[diagram p11: schematic, sheet 12]
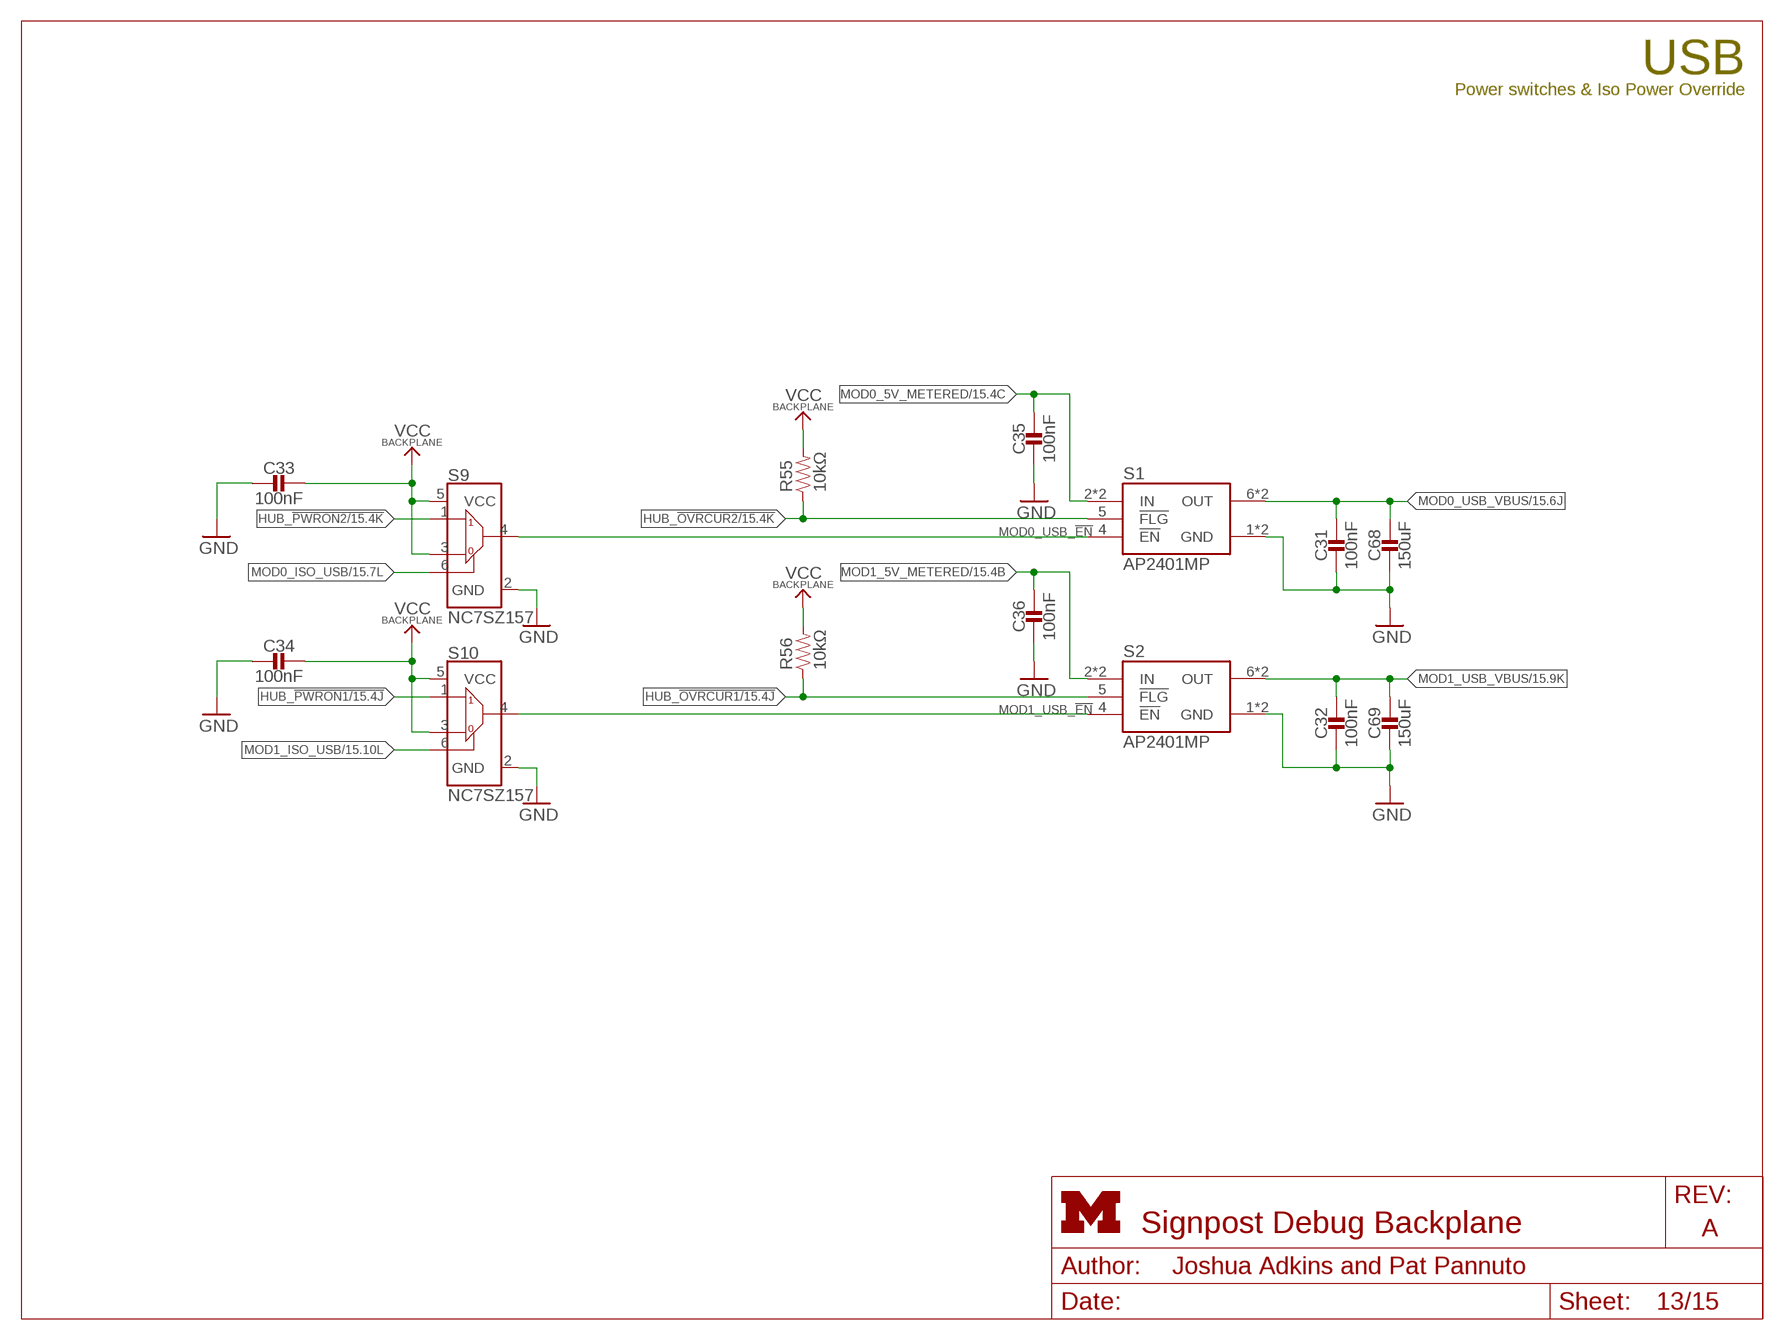
[diagram p12: schematic, sheet 13]
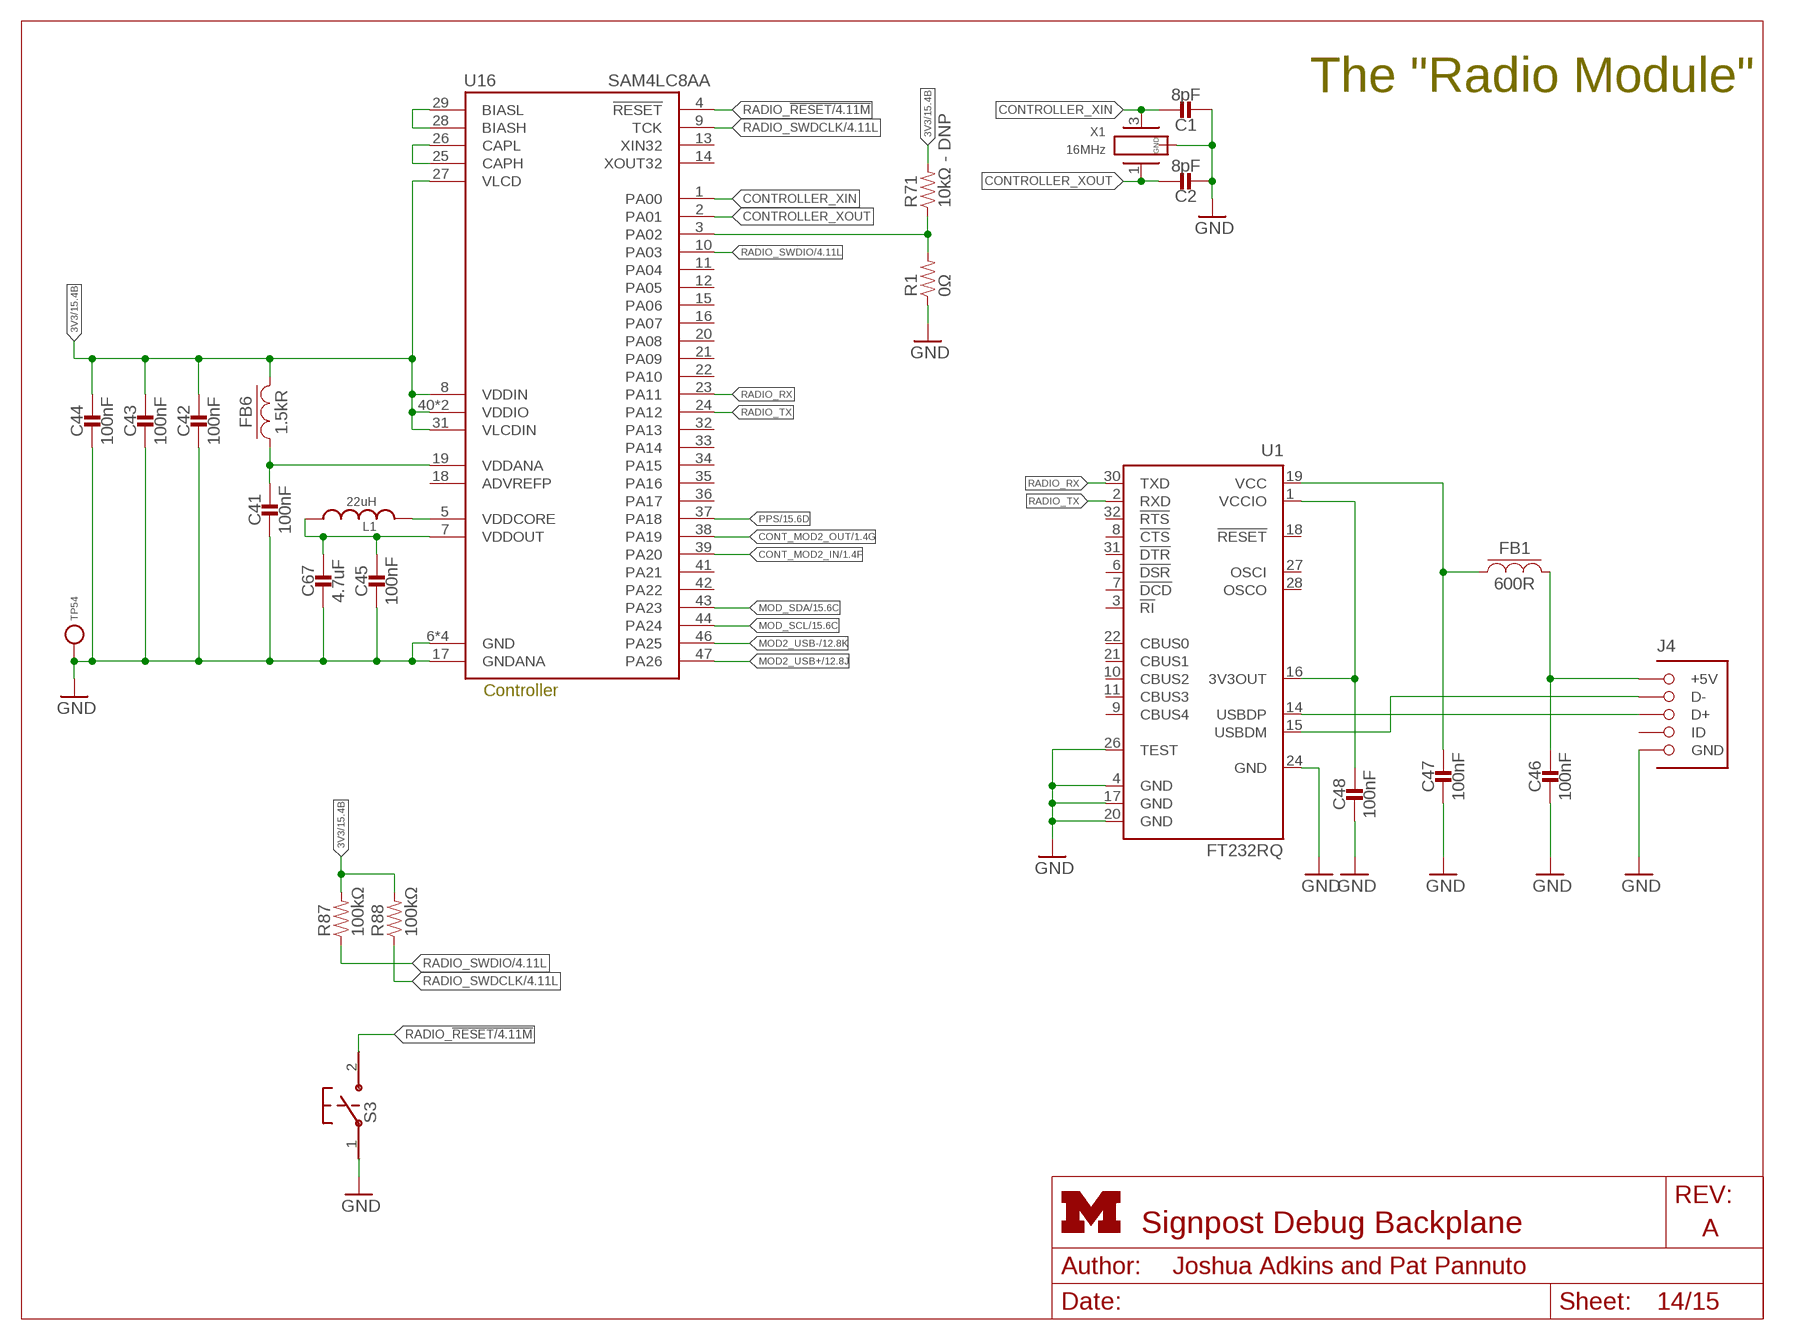
[diagram p13: schematic, sheet 14]
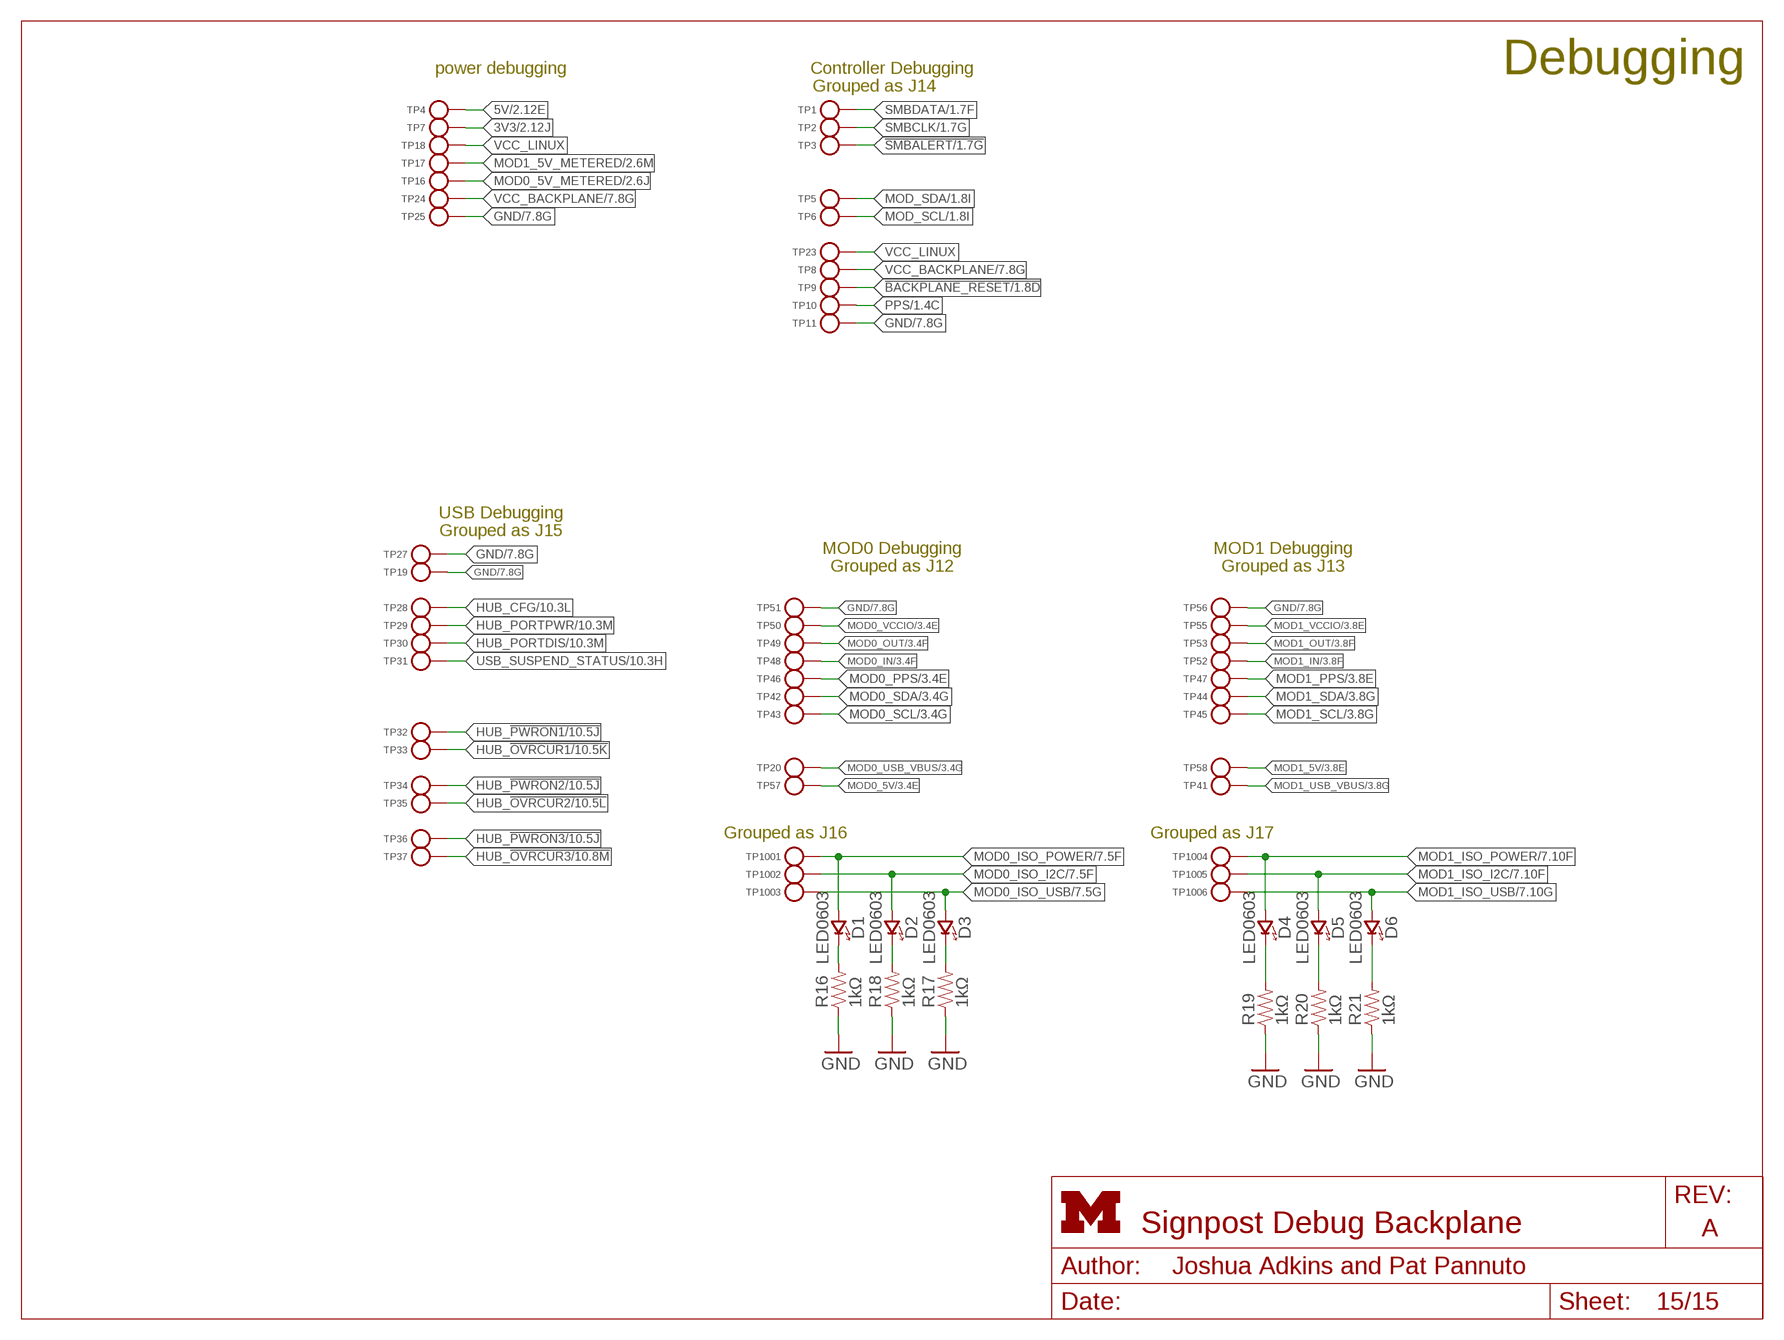
[diagram p14: schematic, sheet 15]

(export (version "E")
  (design (tool "Eeschema 10.0.6"))
  (components
    (comp (ref "C16")
      (value "100nF")
      (footprint "eagle-import:0603_CAP")
      (libsource (lib "eagle-import") (part "CAPACITOR0603_CAP"))
    )
    (comp (ref "C17")
      (value "100nF")
      (footprint "eagle-import:0603_CAP")
      (libsource (lib "eagle-import") (part "CAPACITOR0603_CAP"))
    )
    (comp (ref "C18")
      (value "100nF")
      (footprint "eagle-import:0603_CAP")
      (libsource (lib "eagle-import") (part "CAPACITOR0603_CAP"))
    )
    (comp (ref "C19")
      (value "100nF")
      (footprint "eagle-import:0603_CAP")
      (libsource (lib "eagle-import") (part "CAPACITOR0603_CAP"))
    )
    (comp (ref "C39")
      (value "100nF")
      (footprint "eagle-import:0603_CAP")
      (libsource (lib "eagle-import") (part "CAPACITOR0603_CAP"))
    )
    (comp (ref "C40")
      (value "100nF")
      (footprint "eagle-import:0603_CAP")
      (libsource (lib "eagle-import") (part "CAPACITOR0603_CAP"))
    )
    (comp (ref "C64")
      (value "4.7uF")
      (footprint "eagle-import:0603_CAP")
      (libsource (lib "eagle-import") (part "CAPACITOR0603_CAP"))
    )
    (comp (ref "C65")
      (value "4.7uF")
      (footprint "eagle-import:0603_CAP")
      (libsource (lib "eagle-import") (part "CAPACITOR0603_CAP"))
    )
    (comp (ref "R57")
      (value "10kΩ")
      (footprint "eagle-import:0603-RES")
      (libsource (lib "eagle-import") (part "RESISTOR0603_RES"))
    )
    (comp (ref "R58")
      (value "10kΩ")
      (footprint "eagle-import:0603-RES")
      (libsource (lib "eagle-import") (part "RESISTOR0603_RES"))
    )
    (comp (ref "R59")
      (value "10kΩ")
      (footprint "eagle-import:0603-RES")
      (libsource (lib "eagle-import") (part "RESISTOR0603_RES"))
    )
    (comp (ref "R60")
      (value "10kΩ")
      (footprint "eagle-import:0603-RES")
      (libsource (lib "eagle-import") (part "RESISTOR0603_RES"))
    )
    (comp (ref "S12")
      (value "SIP3240X")
      (footprint "eagle-import:TDFN4")
      (libsource (lib "eagle-import") (part "SIP3240X"))
    )
    (comp (ref "S13")
      (value "SIP3240X")
      (footprint "eagle-import:TDFN4")
      (libsource (lib "eagle-import") (part "SIP3240X"))
    )
    (comp (ref "U6")
      (value "FXMA2102")
      (footprint "eagle-import:UMLP-8")
      (libsource (lib "eagle-import") (part "FXMA2102"))
    )
    (comp (ref "U7")
      (value "FXMA2102")
      (footprint "eagle-import:UMLP-8")
      (libsource (lib "eagle-import") (part "FXMA2102"))
    )
    (comp (ref "C5")
      (value "22pF")
      (footprint "eagle-import:0402_CAP")
      (libsource (lib "eagle-import") (part "CAPACITOR0402_CAP"))
    )
    (comp (ref "C6")
      (value "22pF")
      (footprint "eagle-import:0402_CAP")
      (libsource (lib "eagle-import") (part "CAPACITOR0402_CAP"))
    )
    (comp (ref "C7")
      (value "22pF")
      (footprint "eagle-import:0402_CAP")
      (libsource (lib "eagle-import") (part "CAPACITOR0402_CAP"))
    )
    (comp (ref "C8")
      (value "22pF")
      (footprint "eagle-import:0402_CAP")
      (libsource (lib "eagle-import") (part "CAPACITOR0402_CAP"))
    )
    (comp (ref "C9")
      (value "22pF")
      (footprint "eagle-import:0402_CAP")
      (libsource (lib "eagle-import") (part "CAPACITOR0402_CAP"))
    )
    (comp (ref "C10")
      (value "22pF")
      (footprint "eagle-import:0402_CAP")
      (libsource (lib "eagle-import") (part "CAPACITOR0402_CAP"))
    )
    (comp (ref "C37")
      (value "100nF")
      (footprint "eagle-import:0603_CAP")
      (libsource (lib "eagle-import") (part "CAPACITOR0603_CAP"))
    )
    (comp (ref "C38")
      (value "100nF")
      (footprint "eagle-import:0603_CAP")
      (libsource (lib "eagle-import") (part "CAPACITOR0603_CAP"))
    )
    (comp (ref "D7")
      (value "SN75240-TSSOP")
      (footprint "eagle-import:TSSOP-8")
      (libsource (lib "eagle-import") (part "SN75240-TSSOP"))
    )
    (comp (ref "D8")
      (value "SN75240-TSSOP")
      (footprint "eagle-import:TSSOP-8")
      (libsource (lib "eagle-import") (part "SN75240-TSSOP"))
    )
    (comp (ref "R6")
      (value "27Ω")
      (footprint "eagle-import:0402_RES-HIGH_SPEED")
      (libsource (lib "eagle-import") (part "RESISTOR-HIGH_SPEED0402"))
    )
    (comp (ref "R7")
      (value "27Ω")
      (footprint "eagle-import:0402_RES-HIGH_SPEED")
      (libsource (lib "eagle-import") (part "RESISTOR-HIGH_SPEED0402"))
    )
    (comp (ref "R8")
      (value "27Ω")
      (footprint "eagle-import:0402_RES-HIGH_SPEED")
      (libsource (lib "eagle-import") (part "RESISTOR-HIGH_SPEED0402"))
    )
    (comp (ref "R9")
      (value "27Ω")
      (footprint "eagle-import:0402_RES-HIGH_SPEED")
      (libsource (lib "eagle-import") (part "RESISTOR-HIGH_SPEED0402"))
    )
    (comp (ref "R10")
      (value "27Ω")
      (footprint "eagle-import:0402_RES-HIGH_SPEED")
      (libsource (lib "eagle-import") (part "RESISTOR-HIGH_SPEED0402"))
    )
    (comp (ref "R11")
      (value "27Ω")
      (footprint "eagle-import:0402_RES-HIGH_SPEED")
      (libsource (lib "eagle-import") (part "RESISTOR-HIGH_SPEED0402"))
    )
    (comp (ref "R12")
      (value "50Ω")
      (footprint "eagle-import:0603-RES")
      (libsource (lib "eagle-import") (part "RESISTOR0603_RES"))
    )
    (comp (ref "R13")
      (value "50Ω")
      (footprint "eagle-import:0603-RES")
      (libsource (lib "eagle-import") (part "RESISTOR0603_RES"))
    )
    (comp (ref "R14")
      (value "50Ω")
      (footprint "eagle-import:0603-RES")
      (libsource (lib "eagle-import") (part "RESISTOR0603_RES"))
    )
    (comp (ref "R15")
      (value "50Ω")
      (footprint "eagle-import:0603-RES")
      (libsource (lib "eagle-import") (part "RESISTOR0603_RES"))
    )
    (comp (ref "R73")
      (value "15kΩ")
      (footprint "eagle-import:0603-RES")
      (libsource (lib "eagle-import") (part "RESISTOR0603_RES"))
    )
    (comp (ref "R74")
      (value "15kΩ")
      (footprint "eagle-import:0603-RES")
      (libsource (lib "eagle-import") (part "RESISTOR0603_RES"))
    )
    (comp (ref "R75")
      (value "15kΩ")
      (footprint "eagle-import:0603-RES")
      (libsource (lib "eagle-import") (part "RESISTOR0603_RES"))
    )
    (comp (ref "R76")
      (value "15kΩ")
      (footprint "eagle-import:0603-RES")
      (libsource (lib "eagle-import") (part "RESISTOR0603_RES"))
    )
    (comp (ref "R77")
      (value "15kΩ")
      (footprint "eagle-import:0603-RES")
      (libsource (lib "eagle-import") (part "RESISTOR0603_RES"))
    )
    (comp (ref "R78")
      (value "15kΩ")
      (footprint "eagle-import:0603-RES")
      (libsource (lib "eagle-import") (part "RESISTOR0603_RES"))
    )
    (comp (ref "U21")
      (value "TS3USB30E")
      (footprint "eagle-import:UQFN-10")
      (libsource (lib "eagle-import") (part "TS3USB30E"))
    )
    (comp (ref "U22")
      (value "TS3USB30E")
      (footprint "eagle-import:UQFN-10")
      (libsource (lib "eagle-import") (part "TS3USB30E"))
    )
    (comp (ref "C3")
      (value "22pF")
      (footprint "eagle-import:0603_CAP")
      (libsource (lib "eagle-import") (part "CAPACITOR0603_CAP"))
    )
    (comp (ref "C4")
      (value "22pF")
      (footprint "eagle-import:0603_CAP")
      (libsource (lib "eagle-import") (part "CAPACITOR0603_CAP"))
    )
    (comp (ref "C28")
      (value "100nF")
      (footprint "eagle-import:0603_CAP")
      (libsource (lib "eagle-import") (part "CAPACITOR0603_CAP"))
    )
    (comp (ref "C66")
      (value "4.7uF")
      (footprint "eagle-import:0603_CAP")
      (libsource (lib "eagle-import") (part "CAPACITOR0603_CAP"))
    )
    (comp (ref "R40")
      (value "1.5kΩ")
      (footprint "eagle-import:0603-RES")
      (libsource (lib "eagle-import") (part "RESISTOR0603_RES"))
    )
    (comp (ref "R41")
      (value "1.5kΩ")
      (footprint "eagle-import:0603-RES")
      (libsource (lib "eagle-import") (part "RESISTOR0603_RES"))
    )
    (comp (ref "R66")
      (value "10kΩ")
      (footprint "eagle-import:0603-RES")
      (libsource (lib "eagle-import") (part "RESISTOR0603_RES"))
    )
    (comp (ref "R67")
      (value "10kΩ")
      (footprint "eagle-import:0603-RES")
      (libsource (lib "eagle-import") (part "RESISTOR0603_RES"))
    )
    (comp (ref "R68")
      (value "10kΩ")
      (footprint "eagle-import:0603-RES")
      (libsource (lib "eagle-import") (part "RESISTOR0603_RES"))
    )
    (comp (ref "R69")
      (value "10kΩ")
      (footprint "eagle-import:0603-RES")
      (libsource (lib "eagle-import") (part "RESISTOR0603_RES"))
    )
    (comp (ref "R72")
      (value "10kΩ")
      (footprint "eagle-import:0603-RES")
      (libsource (lib "eagle-import") (part "RESISTOR0603_RES"))
    )
    (comp (ref "R79")
      (value "15kΩ")
      (footprint "eagle-import:0603-RES")
      (libsource (lib "eagle-import") (part "RESISTOR0603_RES"))
    )
    (comp (ref "R80")
      (value "15kΩ")
      (footprint "eagle-import:0603-RES")
      (libsource (lib "eagle-import") (part "RESISTOR0603_RES"))
    )
    (comp (ref "R81")
      (value "15kΩ")
      (footprint "eagle-import:0603-RES")
      (libsource (lib "eagle-import") (part "RESISTOR0603_RES"))
    )
    (comp (ref "R82")
      (value "15kΩ")
      (footprint "eagle-import:0603-RES")
      (libsource (lib "eagle-import") (part "RESISTOR0603_RES"))
    )
    (comp (ref "R83")
      (value "15kΩ")
      (footprint "eagle-import:0603-RES")
      (libsource (lib "eagle-import") (part "RESISTOR0603_RES"))
    )
    (comp (ref "R84")
      (value "15kΩ")
      (footprint "eagle-import:0603-RES")
      (libsource (lib "eagle-import") (part "RESISTOR0603_RES"))
    )
    (comp (ref "R85")
      (value "15kΩ")
      (footprint "eagle-import:0603-RES")
      (libsource (lib "eagle-import") (part "RESISTOR0603_RES"))
    )
    (comp (ref "R86")
      (value "15kΩ")
      (footprint "eagle-import:0603-RES")
      (libsource (lib "eagle-import") (part "RESISTOR0603_RES"))
    )
    (comp (ref "U24")
      (value "TUSB2077A")
      (footprint "eagle-import:LQFP-48")
      (libsource (lib "eagle-import") (part "TUSB2077A"))
    )
    (comp (ref "Y1")
      (value "ABMM")
      (footprint "eagle-import:ABMM")
      (libsource (lib "eagle-import") (part "ABMM"))
    )
    (comp (ref "C20")
      (value "100nF")
      (footprint "eagle-import:0603_CAP")
      (libsource (lib "eagle-import") (part "CAPACITOR0603_CAP"))
    )
    (comp (ref "C21")
      (value "100nF")
      (footprint "eagle-import:0603_CAP")
      (libsource (lib "eagle-import") (part "CAPACITOR0603_CAP"))
    )
    (comp (ref "C22")
      (value "100nF")
      (footprint "eagle-import:0603_CAP")
      (libsource (lib "eagle-import") (part "CAPACITOR0603_CAP"))
    )
    (comp (ref "C23")
      (value "100nF")
      (footprint "eagle-import:0603_CAP")
      (libsource (lib "eagle-import") (part "CAPACITOR0603_CAP"))
    )
    (comp (ref "C24")
      (value "100nF")
      (footprint "eagle-import:0603_CAP")
      (libsource (lib "eagle-import") (part "CAPACITOR0603_CAP"))
    )
    (comp (ref "C25")
      (value "100nF")
      (footprint "eagle-import:0603_CAP")
      (libsource (lib "eagle-import") (part "CAPACITOR0603_CAP"))
    )
    (comp (ref "C26")
      (value "100nF")
      (footprint "eagle-import:0603_CAP")
      (libsource (lib "eagle-import") (part "CAPACITOR0603_CAP"))
    )
    (comp (ref "C27")
      (value "100nF")
      (footprint "eagle-import:0603_CAP")
      (libsource (lib "eagle-import") (part "CAPACITOR0603_CAP"))
    )
    (comp (ref "U17")
      (value "SN74LVC2T45")
      (footprint "eagle-import:VFSOP-8")
      (libsource (lib "eagle-import") (part "SN74LVC2T45"))
    )
    (comp (ref "U18")
      (value "SN74LVC2T45")
      (footprint "eagle-import:VFSOP-8")
      (libsource (lib "eagle-import") (part "SN74LVC2T45"))
    )
    (comp (ref "U19")
      (value "SN74LVC2T45")
      (footprint "eagle-import:VFSOP-8")
      (libsource (lib "eagle-import") (part "SN74LVC2T45"))
    )
    (comp (ref "U20")
      (value "SN74LVC2T45")
      (footprint "eagle-import:VFSOP-8")
      (libsource (lib "eagle-import") (part "SN74LVC2T45"))
    )
    (comp (ref "J10")
      (value "ML20")
      (footprint "eagle-import:ML20")
      (libsource (lib "eagle-import") (part "ML20"))
    )
    (comp (ref "LED5")
      (value "LED0603")
      (footprint "eagle-import:LED-0603")
      (libsource (lib "eagle-import") (part "LED0603"))
    )
    (comp (ref "LED6")
      (value "LED0603")
      (footprint "eagle-import:LED-0603")
      (libsource (lib "eagle-import") (part "LED0603"))
    )
    (comp (ref "LED7")
      (value "LED0603")
      (footprint "eagle-import:LED-0603")
      (libsource (lib "eagle-import") (part "LED0603"))
    )
    (comp (ref "LED8")
      (value "LED0603")
      (footprint "eagle-import:LED-0603")
      (libsource (lib "eagle-import") (part "LED0603"))
    )
    (comp (ref "LED9")
      (value "LED0603")
      (footprint "eagle-import:LED-0603")
      (libsource (lib "eagle-import") (part "LED0603"))
    )
    (comp (ref "R26")
      (value "1kΩ")
      (footprint "eagle-import:0603-RES")
      (libsource (lib "eagle-import") (part "RESISTOR0603_RES"))
    )
    (comp (ref "R27")
      (value "1kΩ")
      (footprint "eagle-import:0603-RES")
      (libsource (lib "eagle-import") (part "RESISTOR0603_RES"))
    )
    (comp (ref "R28")
      (value "1kΩ")
      (footprint "eagle-import:0603-RES")
      (libsource (lib "eagle-import") (part "RESISTOR0603_RES"))
    )
    (comp (ref "R29")
      (value "1kΩ")
      (footprint "eagle-import:0603-RES")
      (libsource (lib "eagle-import") (part "RESISTOR0603_RES"))
    )
    (comp (ref "R30")
      (value "1kΩ")
      (footprint "eagle-import:0603-RES")
      (libsource (lib "eagle-import") (part "RESISTOR0603_RES"))
    )
    (comp (ref "R31")
      (value "1kΩ")
      (footprint "eagle-import:0603-RES")
      (libsource (lib "eagle-import") (part "RESISTOR0603_RES"))
    )
    (comp (ref "R32")
      (value "1kΩ")
      (footprint "eagle-import:0603-RES")
      (libsource (lib "eagle-import") (part "RESISTOR0603_RES"))
    )
    (comp (ref "R33")
      (value "1kΩ")
      (footprint "eagle-import:0603-RES")
      (libsource (lib "eagle-import") (part "RESISTOR0603_RES"))
    )
    (comp (ref "R34")
      (value "1kΩ")
      (footprint "eagle-import:0603-RES")
      (libsource (lib "eagle-import") (part "RESISTOR0603_RES"))
    )
    (comp (ref "R35")
      (value "1kΩ")
      (footprint "eagle-import:0603-RES")
      (libsource (lib "eagle-import") (part "RESISTOR0603_RES"))
    )
    (comp (ref "S11")
      (value "RM106772BCB")
      (footprint "eagle-import:RM-SWITCH")
      (libsource (lib "eagle-import") (part "RM106772BCB"))
    )
    (comp (ref "S14")
      (value "SN74AHC4066-RGY")
      (footprint "eagle-import:S-PVQFN-N14-3.5MM")
      (libsource (lib "eagle-import") (part "SN74AHC4066-RGY"))
    )
    (comp (ref "S15")
      (value "SN74AHC4066-RGY")
      (footprint "eagle-import:S-PVQFN-N14-3.5MM")
      (libsource (lib "eagle-import") (part "SN74AHC4066-RGY"))
    )
    (comp (ref "S16")
      (value "SN74AHC4066-RGY")
      (footprint "eagle-import:S-PVQFN-N14-3.5MM")
      (libsource (lib "eagle-import") (part "SN74AHC4066-RGY"))
    )
    (comp (ref "S17")
      (value "SN74AHC4066-RGY")
      (footprint "eagle-import:S-PVQFN-N14-3.5MM")
      (libsource (lib "eagle-import") (part "SN74AHC4066-RGY"))
    )
    (comp (ref "S18")
      (value "SN74AHC4066-RGY")
      (footprint "eagle-import:S-PVQFN-N14-3.5MM")
      (libsource (lib "eagle-import") (part "SN74AHC4066-RGY"))
    )
    (comp (ref "S19")
      (value "TE_SSA12/SPDT")
      (footprint "eagle-import:TE_SSA12_SPDT")
      (libsource (lib "eagle-import") (part "TE_SSA12/SPDT"))
    )
    (comp (ref "C29")
      (value "100nF")
      (footprint "eagle-import:0603_CAP")
      (libsource (lib "eagle-import") (part "CAPACITOR0603_CAP"))
    )
    (comp (ref "C30")
      (value "100nF")
      (footprint "eagle-import:0603_CAP")
      (libsource (lib "eagle-import") (part "CAPACITOR0603_CAP"))
    )
    (comp (ref "R91")
      (value "10MΩ")
      (footprint "eagle-import:0603-RES")
      (libsource (lib "eagle-import") (part "RESISTOR0603_RES"))
    )
    (comp (ref "R92")
      (value "10MΩ")
      (footprint "eagle-import:0603-RES")
      (libsource (lib "eagle-import") (part "RESISTOR0603_RES"))
    )
    (comp (ref "R93")
      (value "10MΩ")
      (footprint "eagle-import:0603-RES")
      (libsource (lib "eagle-import") (part "RESISTOR0603_RES"))
    )
    (comp (ref "R94")
      (value "10MΩ")
      (footprint "eagle-import:0603-RES")
      (libsource (lib "eagle-import") (part "RESISTOR0603_RES"))
    )
    (comp (ref "R95")
      (value "10MΩ")
      (footprint "eagle-import:0603-RES")
      (libsource (lib "eagle-import") (part "RESISTOR0603_RES"))
    )
    (comp (ref "R96")
      (value "10MΩ")
      (footprint "eagle-import:0603-RES")
      (libsource (lib "eagle-import") (part "RESISTOR0603_RES"))
    )
    (comp (ref "U13")
      (value "MCP23008QFN")
      (footprint "eagle-import:QFN-20-4MM")
      (libsource (lib "eagle-import") (part "MCP23008QFN"))
    )
    (comp (ref "U14")
      (value "MCP23008QFN")
      (footprint "eagle-import:QFN-20-4MM")
      (libsource (lib "eagle-import") (part "MCP23008QFN"))
    )
    (comp (ref "C1")
      (value "8pF")
      (footprint "eagle-import:0603_CAP")
      (libsource (lib "eagle-import") (part "CAPACITOR0603_CAP"))
    )
    (comp (ref "C2")
      (value "8pF")
      (footprint "eagle-import:0603_CAP")
      (libsource (lib "eagle-import") (part "CAPACITOR0603_CAP"))
    )
    (comp (ref "C41")
      (value "100nF")
      (footprint "eagle-import:0603_CAP")
      (libsource (lib "eagle-import") (part "CAPACITOR0603_CAP"))
    )
    (comp (ref "C42")
      (value "100nF")
      (footprint "eagle-import:0603_CAP")
      (libsource (lib "eagle-import") (part "CAPACITOR0603_CAP"))
    )
    (comp (ref "C43")
      (value "100nF")
      (footprint "eagle-import:0603_CAP")
      (libsource (lib "eagle-import") (part "CAPACITOR0603_CAP"))
    )
    (comp (ref "C44")
      (value "100nF")
      (footprint "eagle-import:0603_CAP")
      (libsource (lib "eagle-import") (part "CAPACITOR0603_CAP"))
    )
    (comp (ref "C45")
      (value "100nF")
      (footprint "eagle-import:0402_CAP")
      (libsource (lib "eagle-import") (part "CAPACITOR0402_CAP"))
    )
    (comp (ref "C46")
      (value "100nF")
      (footprint "eagle-import:0603_CAP")
      (libsource (lib "eagle-import") (part "CAPACITOR0603_CAP"))
    )
    (comp (ref "C47")
      (value "100nF")
      (footprint "eagle-import:0603_CAP")
      (libsource (lib "eagle-import") (part "CAPACITOR0603_CAP"))
    )
    (comp (ref "C48")
      (value "100nF")
      (footprint "eagle-import:0603_CAP")
      (libsource (lib "eagle-import") (part "CAPACITOR0603_CAP"))
    )
    (comp (ref "C67")
      (value "4.7uF")
      (footprint "eagle-import:0402_CAP")
      (libsource (lib "eagle-import") (part "CAPACITOR0402_CAP"))
    )
    (comp (ref "FB1")
      (value "600R")
      (footprint "eagle-import:0603_CAP")
      (libsource (lib "eagle-import") (part "FERRITE_BEAD0603"))
    )
    (comp (ref "FB6")
      (value "1.5kR")
      (footprint "eagle-import:0603_CAP")
      (libsource (lib "eagle-import") (part "FERRITE_BEAD0603"))
    )
    (comp (ref "J4")
      (value "MICRO_USB_B_HIROSE_ZX62R-B-5P")
      (footprint "eagle-import:USB_MICRO_B-HIROSE-ZX62R-B-5P")
      (libsource (lib "eagle-import") (part "MICRO_USB_B_HIROSE_ZX62R-B-5P"))
    )
    (comp (ref "L1")
      (value "22uH")
      (footprint "eagle-import:1212")
      (libsource (lib "eagle-import") (part "LHQ3NP"))
    )
    (comp (ref "R1")
      (value "0Ω")
      (footprint "eagle-import:0603-RES")
      (libsource (lib "eagle-import") (part "RESISTOR0603_RES"))
    )
    (comp (ref "R71")
      (value "10kΩ - DNP")
      (footprint "eagle-import:0603-RES")
      (libsource (lib "eagle-import") (part "RESISTOR0603_RES"))
    )
    (comp (ref "R87")
      (value "100kΩ")
      (footprint "eagle-import:0603-RES")
      (libsource (lib "eagle-import") (part "RESISTOR0603_RES"))
    )
    (comp (ref "R88")
      (value "100kΩ")
      (footprint "eagle-import:0603-RES")
      (libsource (lib "eagle-import") (part "RESISTOR0603_RES"))
    )
    (comp (ref "S3")
      (value "B3U-1000P")
      (footprint "eagle-import:B3U-1000P")
      (libsource (lib "eagle-import") (part "B3U-1000P"))
    )
    (comp (ref "TP54")
      (value "TEST_POINT_0.040IN")
      (footprint "eagle-import:TESTPOINT_0.040IN")
      (libsource (lib "eagle-import") (part "TEST_POINT_0.040IN"))
    )
    (comp (ref "U1")
      (value "FT232RQ")
      (footprint "eagle-import:QFN32")
      (libsource (lib "eagle-import") (part "FT232RQ"))
    )
    (comp (ref "U16")
      (value "SAM4LC8AA")
      (footprint "eagle-import:QFN-48-7MM")
      (libsource (lib "eagle-import") (part "SAM4LC8AA"))
    )
    (comp (ref "X1")
      (value "16MHz")
      (footprint "eagle-import:FHXXX")
      (libsource (lib "eagle-import") (part "FH1600015"))
    )
    (comp (ref "C11")
      (value "0.01uF")
      (footprint "eagle-import:0402_CAP")
      (libsource (lib "eagle-import") (part "CAPACITOR0402_CAP"))
    )
    (comp (ref "C12")
      (value "0.1uF")
      (footprint "eagle-import:0402_CAP")
      (libsource (lib "eagle-import") (part "CAPACITOR0402_CAP"))
    )
    (comp (ref "C13")
      (value "0.1uF")
      (footprint "eagle-import:0402_CAP")
      (libsource (lib "eagle-import") (part "CAPACITOR0402_CAP"))
    )
    (comp (ref "C14")
      (value "0.1uF")
      (footprint "eagle-import:0402_CAP")
      (libsource (lib "eagle-import") (part "CAPACITOR0402_CAP"))
    )
    (comp (ref "C15")
      (value "0.1uF")
      (footprint "eagle-import:0402_CAP")
      (libsource (lib "eagle-import") (part "CAPACITOR0402_CAP"))
    )
    (comp (ref "C62")
      (value "2.2uF")
      (footprint "eagle-import:0603_CAP")
      (libsource (lib "eagle-import") (part "CAPACITOR0603_CAP"))
    )
    (comp (ref "C63")
      (value "2.2uF")
      (footprint "eagle-import:0603_CAP")
      (libsource (lib "eagle-import") (part "CAPACITOR0603_CAP"))
    )
    (comp (ref "C70")
      (value "4.7uF")
      (footprint "eagle-import:0603_CAP")
      (libsource (lib "eagle-import") (part "CAPACITOR0603_CAP"))
    )
    (comp (ref "D9")
      (value "LED0603")
      (footprint "eagle-import:LED-0603")
      (libsource (lib "eagle-import") (part "LED0603"))
    )
    (comp (ref "J11")
      (value "PJ-102AH")
      (footprint "eagle-import:PJ-102AH")
      (libsource (lib "eagle-import") (part "PJ-102AH"))
    )
    (comp (ref "Q10")
      (value "MOSFET-NCHANNELSMD")
      (footprint "eagle-import:SOT23-3")
      (libsource (lib "eagle-import") (part "MOSFET-NCHANNELSMD"))
    )
    (comp (ref "R2")
      (value "0.017Ω")
      (footprint "eagle-import:0805_RES")
      (libsource (lib "eagle-import") (part "RESISTOR0805_RES"))
    )
    (comp (ref "R3")
      (value "0.017Ω")
      (footprint "eagle-import:0805_RES")
      (libsource (lib "eagle-import") (part "RESISTOR0805_RES"))
    )
    (comp (ref "R4")
      (value "0.017Ω")
      (footprint "eagle-import:0805_RES")
      (libsource (lib "eagle-import") (part "RESISTOR0805_RES"))
    )
    (comp (ref "R5")
      (value "0.017Ω")
      (footprint "eagle-import:0805_RES")
      (libsource (lib "eagle-import") (part "RESISTOR0805_RES"))
    )
    (comp (ref "R43")
      (value "2kΩ")
      (footprint "eagle-import:0402_RES")
      (libsource (lib "eagle-import") (part "RESISTOR0402_RES"))
    )
    (comp (ref "R44")
      (value "2kΩ")
      (footprint "eagle-import:0402_RES")
      (libsource (lib "eagle-import") (part "RESISTOR0402_RES"))
    )
    (comp (ref "R45")
      (value "2kΩ")
      (footprint "eagle-import:0402_RES")
      (libsource (lib "eagle-import") (part "RESISTOR0402_RES"))
    )
    (comp (ref "R46")
      (value "2kΩ")
      (footprint "eagle-import:0402_RES")
      (libsource (lib "eagle-import") (part "RESISTOR0402_RES"))
    )
    (comp (ref "R47")
      (value "2kΩ")
      (footprint "eagle-import:0402_RES")
      (libsource (lib "eagle-import") (part "RESISTOR0402_RES"))
    )
    (comp (ref "R48")
      (value "2kΩ")
      (footprint "eagle-import:0402_RES")
      (libsource (lib "eagle-import") (part "RESISTOR0402_RES"))
    )
    (comp (ref "R49")
      (value "2kΩ")
      (footprint "eagle-import:0402_RES")
      (libsource (lib "eagle-import") (part "RESISTOR0402_RES"))
    )
    (comp (ref "R50")
      (value "2kΩ")
      (footprint "eagle-import:0402_RES")
      (libsource (lib "eagle-import") (part "RESISTOR0402_RES"))
    )
    (comp (ref "R51")
      (value "2kΩ")
      (footprint "eagle-import:0402_RES")
      (libsource (lib "eagle-import") (part "RESISTOR0402_RES"))
    )
    (comp (ref "R52")
      (value "2kΩ")
      (footprint "eagle-import:0402_RES")
      (libsource (lib "eagle-import") (part "RESISTOR0402_RES"))
    )
    (comp (ref "R53")
      (value "2kΩ")
      (footprint "eagle-import:0402_RES")
      (libsource (lib "eagle-import") (part "RESISTOR0402_RES"))
    )
    (comp (ref "R54")
      (value "2kΩ")
      (footprint "eagle-import:0402_RES")
      (libsource (lib "eagle-import") (part "RESISTOR0402_RES"))
    )
    (comp (ref "R70")
      (value "10kΩ")
      (footprint "eagle-import:0603-RES")
      (libsource (lib "eagle-import") (part "RESISTOR0603_RES"))
    )
    (comp (ref "R105")
      (value "1kΩ")
      (footprint "eagle-import:0603-RES")
      (libsource (lib "eagle-import") (part "RESISTOR0603_RES"))
    )
    (comp (ref "R106")
      (value "0Ω - DNP")
      (footprint "eagle-import:0603-RES")
      (libsource (lib "eagle-import") (part "RESISTOR0603_RES"))
    )
    (comp (ref "U8")
      (value "LTC2941")
      (footprint "eagle-import:DFN-6-2MMX3MM")
      (libsource (lib "eagle-import") (part "LTC2941"))
    )
    (comp (ref "U9")
      (value "LTC2941")
      (footprint "eagle-import:DFN-6-2MMX3MM")
      (libsource (lib "eagle-import") (part "LTC2941"))
    )
    (comp (ref "U10")
      (value "LTC2941")
      (footprint "eagle-import:DFN-6-2MMX3MM")
      (libsource (lib "eagle-import") (part "LTC2941"))
    )
    (comp (ref "U11")
      (value "LTC2941")
      (footprint "eagle-import:DFN-6-2MMX3MM")
      (libsource (lib "eagle-import") (part "LTC2941"))
    )
    (comp (ref "U12")
      (value "MAX8887EZK33+T")
      (footprint "eagle-import:SOT-23-5")
      (libsource (lib "eagle-import") (part "MAX8887EZK33+T"))
    )
    (comp (ref "U15")
      (value "PCA9544AQFN-N20")
      (footprint "eagle-import:QFN-N20")
      (libsource (lib "eagle-import") (part "PCA9544AQFN-N20"))
    )
    (comp (ref "U25")
      (value "LTC4360")
      (footprint "eagle-import:SC70-8")
      (libsource (lib "eagle-import") (part "LTC4360"))
    )
    (comp (ref "D1")
      (value "LED0603")
      (footprint "eagle-import:LED-0603")
      (libsource (lib "eagle-import") (part "LED0603"))
    )
    (comp (ref "D2")
      (value "LED0603")
      (footprint "eagle-import:LED-0603")
      (libsource (lib "eagle-import") (part "LED0603"))
    )
    (comp (ref "D3")
      (value "LED0603")
      (footprint "eagle-import:LED-0603")
      (libsource (lib "eagle-import") (part "LED0603"))
    )
    (comp (ref "D4")
      (value "LED0603")
      (footprint "eagle-import:LED-0603")
      (libsource (lib "eagle-import") (part "LED0603"))
    )
    (comp (ref "D5")
      (value "LED0603")
      (footprint "eagle-import:LED-0603")
      (libsource (lib "eagle-import") (part "LED0603"))
    )
    (comp (ref "D6")
      (value "LED0603")
      (footprint "eagle-import:LED-0603")
      (libsource (lib "eagle-import") (part "LED0603"))
    )
    (comp (ref "R16")
      (value "1kΩ")
      (footprint "eagle-import:0603-RES")
      (libsource (lib "eagle-import") (part "RESISTOR0603_RES"))
    )
    (comp (ref "R17")
      (value "1kΩ")
      (footprint "eagle-import:0603-RES")
      (libsource (lib "eagle-import") (part "RESISTOR0603_RES"))
    )
    (comp (ref "R18")
      (value "1kΩ")
      (footprint "eagle-import:0603-RES")
      (libsource (lib "eagle-import") (part "RESISTOR0603_RES"))
    )
    (comp (ref "R19")
      (value "1kΩ")
      (footprint "eagle-import:0603-RES")
      (libsource (lib "eagle-import") (part "RESISTOR0603_RES"))
    )
    (comp (ref "R20")
      (value "1kΩ")
      (footprint "eagle-import:0603-RES")
      (libsource (lib "eagle-import") (part "RESISTOR0603_RES"))
    )
    (comp (ref "R21")
      (value "1kΩ")
      (footprint "eagle-import:0603-RES")
      (libsource (lib "eagle-import") (part "RESISTOR0603_RES"))
    )
    (comp (ref "TP1")
      (value "TEST_POINT_0.040IN")
      (footprint "eagle-import:TESTPOINT_0.040IN")
      (libsource (lib "eagle-import") (part "TEST_POINT_0.040IN"))
    )
    (comp (ref "TP2")
      (value "TEST_POINT_0.040IN")
      (footprint "eagle-import:TESTPOINT_0.040IN")
      (libsource (lib "eagle-import") (part "TEST_POINT_0.040IN"))
    )
    (comp (ref "TP3")
      (value "TEST_POINT_0.040IN")
      (footprint "eagle-import:TESTPOINT_0.040IN")
      (libsource (lib "eagle-import") (part "TEST_POINT_0.040IN"))
    )
    (comp (ref "TP4")
      (value "TEST_POINT_0.040IN")
      (footprint "eagle-import:TESTPOINT_0.040IN")
      (libsource (lib "eagle-import") (part "TEST_POINT_0.040IN"))
    )
    (comp (ref "TP5")
      (value "TEST_POINT_0.040IN")
      (footprint "eagle-import:TESTPOINT_0.040IN")
      (libsource (lib "eagle-import") (part "TEST_POINT_0.040IN"))
    )
    (comp (ref "TP6")
      (value "TEST_POINT_0.040IN")
      (footprint "eagle-import:TESTPOINT_0.040IN")
      (libsource (lib "eagle-import") (part "TEST_POINT_0.040IN"))
    )
    (comp (ref "TP7")
      (value "TEST_POINT_0.040IN")
      (footprint "eagle-import:TESTPOINT_0.040IN")
      (libsource (lib "eagle-import") (part "TEST_POINT_0.040IN"))
    )
    (comp (ref "TP8")
      (value "TEST_POINT_0.040IN")
      (footprint "eagle-import:TESTPOINT_0.040IN")
      (libsource (lib "eagle-import") (part "TEST_POINT_0.040IN"))
    )
    (comp (ref "TP9")
      (value "TEST_POINT_0.040IN")
      (footprint "eagle-import:TESTPOINT_0.040IN")
      (libsource (lib "eagle-import") (part "TEST_POINT_0.040IN"))
    )
    (comp (ref "TP10")
      (value "TEST_POINT_0.040IN")
      (footprint "eagle-import:TESTPOINT_0.040IN")
      (libsource (lib "eagle-import") (part "TEST_POINT_0.040IN"))
    )
    (comp (ref "TP11")
      (value "TEST_POINT_0.040IN")
      (footprint "eagle-import:TESTPOINT_0.040IN")
      (libsource (lib "eagle-import") (part "TEST_POINT_0.040IN"))
    )
    (comp (ref "TP16")
      (value "TEST_POINT_0.040IN")
      (footprint "eagle-import:TESTPOINT_0.040IN")
      (libsource (lib "eagle-import") (part "TEST_POINT_0.040IN"))
    )
    (comp (ref "TP17")
      (value "TEST_POINT_0.040IN")
      (footprint "eagle-import:TESTPOINT_0.040IN")
      (libsource (lib "eagle-import") (part "TEST_POINT_0.040IN"))
    )
    (comp (ref "TP18")
      (value "TEST_POINT_0.040IN")
      (footprint "eagle-import:TESTPOINT_0.040IN")
      (libsource (lib "eagle-import") (part "TEST_POINT_0.040IN"))
    )
    (comp (ref "TP19")
      (value "TEST_POINT_0.040IN")
      (footprint "eagle-import:TESTPOINT_0.040IN")
      (libsource (lib "eagle-import") (part "TEST_POINT_0.040IN"))
    )
    (comp (ref "TP20")
      (value "TEST_POINT_0.040IN")
      (footprint "eagle-import:TESTPOINT_0.040IN")
      (libsource (lib "eagle-import") (part "TEST_POINT_0.040IN"))
    )
    (comp (ref "TP23")
      (value "TEST_POINT_0.040IN")
      (footprint "eagle-import:TESTPOINT_0.040IN")
      (libsource (lib "eagle-import") (part "TEST_POINT_0.040IN"))
    )
    (comp (ref "TP24")
      (value "TEST_POINT_0.040IN")
      (footprint "eagle-import:TESTPOINT_0.040IN")
      (libsource (lib "eagle-import") (part "TEST_POINT_0.040IN"))
    )
    (comp (ref "TP25")
      (value "TEST_POINT_0.040IN")
      (footprint "eagle-import:TESTPOINT_0.040IN")
      (libsource (lib "eagle-import") (part "TEST_POINT_0.040IN"))
    )
    (comp (ref "TP27")
      (value "TEST_POINT_0.040IN")
      (footprint "eagle-import:TESTPOINT_0.040IN")
      (libsource (lib "eagle-import") (part "TEST_POINT_0.040IN"))
    )
    (comp (ref "TP28")
      (value "TEST_POINT_0.040IN")
      (footprint "eagle-import:TESTPOINT_0.040IN")
      (libsource (lib "eagle-import") (part "TEST_POINT_0.040IN"))
    )
    (comp (ref "TP29")
      (value "TEST_POINT_0.040IN")
      (footprint "eagle-import:TESTPOINT_0.040IN")
      (libsource (lib "eagle-import") (part "TEST_POINT_0.040IN"))
    )
    (comp (ref "TP30")
      (value "TEST_POINT_0.040IN")
      (footprint "eagle-import:TESTPOINT_0.040IN")
      (libsource (lib "eagle-import") (part "TEST_POINT_0.040IN"))
    )
    (comp (ref "TP31")
      (value "TEST_POINT_0.040IN")
      (footprint "eagle-import:TESTPOINT_0.040IN")
      (libsource (lib "eagle-import") (part "TEST_POINT_0.040IN"))
    )
    (comp (ref "TP32")
      (value "TEST_POINT_0.040IN")
      (footprint "eagle-import:TESTPOINT_0.040IN")
      (libsource (lib "eagle-import") (part "TEST_POINT_0.040IN"))
    )
    (comp (ref "TP33")
      (value "TEST_POINT_0.040IN")
      (footprint "eagle-import:TESTPOINT_0.040IN")
      (libsource (lib "eagle-import") (part "TEST_POINT_0.040IN"))
    )
    (comp (ref "TP34")
      (value "TEST_POINT_0.040IN")
      (footprint "eagle-import:TESTPOINT_0.040IN")
      (libsource (lib "eagle-import") (part "TEST_POINT_0.040IN"))
    )
    (comp (ref "TP35")
      (value "TEST_POINT_0.040IN")
      (footprint "eagle-import:TESTPOINT_0.040IN")
      (libsource (lib "eagle-import") (part "TEST_POINT_0.040IN"))
    )
    (comp (ref "TP36")
      (value "TEST_POINT_0.040IN")
      (footprint "eagle-import:TESTPOINT_0.040IN")
      (libsource (lib "eagle-import") (part "TEST_POINT_0.040IN"))
    )
    (comp (ref "TP37")
      (value "TEST_POINT_0.040IN")
      (footprint "eagle-import:TESTPOINT_0.040IN")
      (libsource (lib "eagle-import") (part "TEST_POINT_0.040IN"))
    )
    (comp (ref "TP41")
      (value "TEST_POINT_0.040IN")
      (footprint "eagle-import:TESTPOINT_0.040IN")
      (libsource (lib "eagle-import") (part "TEST_POINT_0.040IN"))
    )
    (comp (ref "TP42")
      (value "TEST_POINT_0.040IN")
      (footprint "eagle-import:TESTPOINT_0.040IN")
      (libsource (lib "eagle-import") (part "TEST_POINT_0.040IN"))
    )
    (comp (ref "TP43")
      (value "TEST_POINT_0.040IN")
      (footprint "eagle-import:TESTPOINT_0.040IN")
      (libsource (lib "eagle-import") (part "TEST_POINT_0.040IN"))
    )
    (comp (ref "TP44")
      (value "TEST_POINT_0.040IN")
      (footprint "eagle-import:TESTPOINT_0.040IN")
      (libsource (lib "eagle-import") (part "TEST_POINT_0.040IN"))
    )
    (comp (ref "TP45")
      (value "TEST_POINT_0.040IN")
      (footprint "eagle-import:TESTPOINT_0.040IN")
      (libsource (lib "eagle-import") (part "TEST_POINT_0.040IN"))
    )
    (comp (ref "TP46")
      (value "TEST_POINT_0.040IN")
      (footprint "eagle-import:TESTPOINT_0.040IN")
      (libsource (lib "eagle-import") (part "TEST_POINT_0.040IN"))
    )
    (comp (ref "TP47")
      (value "TEST_POINT_0.040IN")
      (footprint "eagle-import:TESTPOINT_0.040IN")
      (libsource (lib "eagle-import") (part "TEST_POINT_0.040IN"))
    )
    (comp (ref "TP48")
      (value "TEST_POINT_0.040IN")
      (footprint "eagle-import:TESTPOINT_0.040IN")
      (libsource (lib "eagle-import") (part "TEST_POINT_0.040IN"))
    )
    (comp (ref "TP49")
      (value "TEST_POINT_0.040IN")
      (footprint "eagle-import:TESTPOINT_0.040IN")
      (libsource (lib "eagle-import") (part "TEST_POINT_0.040IN"))
    )
    (comp (ref "TP50")
      (value "TEST_POINT_0.040IN")
      (footprint "eagle-import:TESTPOINT_0.040IN")
      (libsource (lib "eagle-import") (part "TEST_POINT_0.040IN"))
    )
    (comp (ref "TP51")
      (value "TEST_POINT_0.040IN")
      (footprint "eagle-import:TESTPOINT_0.040IN")
      (libsource (lib "eagle-import") (part "TEST_POINT_0.040IN"))
    )
    (comp (ref "TP52")
      (value "TEST_POINT_0.040IN")
      (footprint "eagle-import:TESTPOINT_0.040IN")
      (libsource (lib "eagle-import") (part "TEST_POINT_0.040IN"))
    )
    (comp (ref "TP53")
      (value "TEST_POINT_0.040IN")
      (footprint "eagle-import:TESTPOINT_0.040IN")
      (libsource (lib "eagle-import") (part "TEST_POINT_0.040IN"))
    )
    (comp (ref "TP55")
      (value "TEST_POINT_0.040IN")
      (footprint "eagle-import:TESTPOINT_0.040IN")
      (libsource (lib "eagle-import") (part "TEST_POINT_0.040IN"))
    )
    (comp (ref "TP56")
      (value "TEST_POINT_0.040IN")
      (footprint "eagle-import:TESTPOINT_0.040IN")
      (libsource (lib "eagle-import") (part "TEST_POINT_0.040IN"))
    )
    (comp (ref "TP57")
      (value "TEST_POINT_0.040IN")
      (footprint "eagle-import:TESTPOINT_0.040IN")
      (libsource (lib "eagle-import") (part "TEST_POINT_0.040IN"))
    )
    (comp (ref "TP58")
      (value "TEST_POINT_0.040IN")
      (footprint "eagle-import:TESTPOINT_0.040IN")
      (libsource (lib "eagle-import") (part "TEST_POINT_0.040IN"))
    )
    (comp (ref "TP1001")
      (value "TEST_POINT_0.040IN")
      (footprint "eagle-import:TESTPOINT_0.040IN")
      (libsource (lib "eagle-import") (part "TEST_POINT_0.040IN"))
    )
    (comp (ref "TP1002")
      (value "TEST_POINT_0.040IN")
      (footprint "eagle-import:TESTPOINT_0.040IN")
      (libsource (lib "eagle-import") (part "TEST_POINT_0.040IN"))
    )
    (comp (ref "TP1003")
      (value "TEST_POINT_0.040IN")
      (footprint "eagle-import:TESTPOINT_0.040IN")
      (libsource (lib "eagle-import") (part "TEST_POINT_0.040IN"))
    )
    (comp (ref "TP1004")
      (value "TEST_POINT_0.040IN")
      (footprint "eagle-import:TESTPOINT_0.040IN")
      (libsource (lib "eagle-import") (part "TEST_POINT_0.040IN"))
    )
    (comp (ref "TP1005")
      (value "TEST_POINT_0.040IN")
      (footprint "eagle-import:TESTPOINT_0.040IN")
      (libsource (lib "eagle-import") (part "TEST_POINT_0.040IN"))
    )
    (comp (ref "TP1006")
      (value "TEST_POINT_0.040IN")
      (footprint "eagle-import:TESTPOINT_0.040IN")
      (libsource (lib "eagle-import") (part "TEST_POINT_0.040IN"))
    )
    (comp (ref "C31")
      (value "100nF")
      (footprint "eagle-import:0603_CAP")
      (libsource (lib "eagle-import") (part "CAPACITOR0603_CAP"))
    )
    (comp (ref "C32")
      (value "100nF")
      (footprint "eagle-import:0603_CAP")
      (libsource (lib "eagle-import") (part "CAPACITOR0603_CAP"))
    )
    (comp (ref "C33")
      (value "100nF")
      (footprint "eagle-import:0603_CAP")
      (libsource (lib "eagle-import") (part "CAPACITOR0603_CAP"))
    )
    (comp (ref "C34")
      (value "100nF")
      (footprint "eagle-import:0603_CAP")
      (libsource (lib "eagle-import") (part "CAPACITOR0603_CAP"))
    )
    (comp (ref "C35")
      (value "100nF")
      (footprint "eagle-import:0603_CAP")
      (libsource (lib "eagle-import") (part "CAPACITOR0603_CAP"))
    )
    (comp (ref "C36")
      (value "100nF")
      (footprint "eagle-import:0603_CAP")
      (libsource (lib "eagle-import") (part "CAPACITOR0603_CAP"))
    )
    (comp (ref "C68")
      (value "150uF")
      (footprint "eagle-import:1210_CAP")
      (libsource (lib "eagle-import") (part "CAPACITOR1210_CAP"))
    )
    (comp (ref "C69")
      (value "150uF")
      (footprint "eagle-import:1210_CAP")
      (libsource (lib "eagle-import") (part "CAPACITOR1210_CAP"))
    )
    (comp (ref "R55")
      (value "10kΩ")
      (footprint "eagle-import:0603-RES")
      (libsource (lib "eagle-import") (part "RESISTOR0603_RES"))
    )
    (comp (ref "R56")
      (value "10kΩ")
      (footprint "eagle-import:0603-RES")
      (libsource (lib "eagle-import") (part "RESISTOR0603_RES"))
    )
    (comp (ref "S1")
      (value "AP2401MP")
      (footprint "eagle-import:MSOP-8EP")
      (libsource (lib "eagle-import") (part "AP2401MP"))
    )
    (comp (ref "S2")
      (value "AP2401MP")
      (footprint "eagle-import:MSOP-8EP")
      (libsource (lib "eagle-import") (part "AP2401MP"))
    )
    (comp (ref "S9")
      (value "NC7SZ157")
      (footprint "eagle-import:SC70-6")
      (libsource (lib "eagle-import") (part "NC7SZ157"))
    )
    (comp (ref "S10")
      (value "NC7SZ157")
      (footprint "eagle-import:SC70-6")
      (libsource (lib "eagle-import") (part "NC7SZ157"))
    )
    (comp (ref "J1")
      (value "BACKPLANE_CONTROLLER_MODULE_DEBUG")
      (footprint "eagle-import:BACKPLANE_MODULE_20PIN_10PIN_DEBUG")
      (libsource (lib "eagle-import") (part "BACKPLANE_CONTROLLER_MODULE_DEBUG"))
    )
    (comp (ref "R42")
      (value "1.5kΩ")
      (footprint "eagle-import:0603-RES")
      (libsource (lib "eagle-import") (part "RESISTOR0603_RES"))
    )
    (comp (ref "R61")
      (value "10kΩ")
      (footprint "eagle-import:0603-RES")
      (libsource (lib "eagle-import") (part "RESISTOR0603_RES"))
    )
    (comp (ref "R62")
      (value "10kΩ")
      (footprint "eagle-import:0603-RES")
      (libsource (lib "eagle-import") (part "RESISTOR0603_RES"))
    )
    (comp (ref "R63")
      (value "10kΩ")
      (footprint "eagle-import:0603-RES")
      (libsource (lib "eagle-import") (part "RESISTOR0603_RES"))
    )
    (comp (ref "R64")
      (value "10kΩ")
      (footprint "eagle-import:0603-RES")
      (libsource (lib "eagle-import") (part "RESISTOR0603_RES"))
    )
    (comp (ref "R65")
      (value "10kΩ")
      (footprint "eagle-import:0603-RES")
      (libsource (lib "eagle-import") (part "RESISTOR0603_RES"))
    )
    (comp (ref "S6")
      (value "B3U-1000P")
      (footprint "eagle-import:B3U-1000P")
      (libsource (lib "eagle-import") (part "B3U-1000P"))
    )
    (comp (ref "S7")
      (value "B3U-1000P")
      (footprint "eagle-import:B3U-1000P")
      (libsource (lib "eagle-import") (part "B3U-1000P"))
    )
    (comp (ref "S8")
      (value "B3U-1000P")
      (footprint "eagle-import:B3U-1000P")
      (libsource (lib "eagle-import") (part "B3U-1000P"))
    )
    (comp (ref "C49")
      (value "100nF")
      (footprint "eagle-import:0603_CAP")
      (libsource (lib "eagle-import") (part "CAPACITOR0603_CAP"))
    )
    (comp (ref "C50")
      (value "100nF")
      (footprint "eagle-import:0603_CAP")
      (libsource (lib "eagle-import") (part "CAPACITOR0603_CAP"))
    )
    (comp (ref "C51")
      (value "100nF")
      (footprint "eagle-import:0603_CAP")
      (libsource (lib "eagle-import") (part "CAPACITOR0603_CAP"))
    )
    (comp (ref "C52")
      (value "100nF")
      (footprint "eagle-import:0603_CAP")
      (libsource (lib "eagle-import") (part "CAPACITOR0603_CAP"))
    )
    (comp (ref "C53")
      (value "100nF")
      (footprint "eagle-import:0603_CAP")
      (libsource (lib "eagle-import") (part "CAPACITOR0603_CAP"))
    )
    (comp (ref "C54")
      (value "100nF")
      (footprint "eagle-import:0603_CAP")
      (libsource (lib "eagle-import") (part "CAPACITOR0603_CAP"))
    )
    (comp (ref "FB2")
      (value "600R")
      (footprint "eagle-import:0603_CAP")
      (libsource (lib "eagle-import") (part "FERRITE_BEAD0603"))
    )
    (comp (ref "FB3")
      (value "600R")
      (footprint "eagle-import:0603_CAP")
      (libsource (lib "eagle-import") (part "FERRITE_BEAD0603"))
    )
    (comp (ref "J5")
      (value "MICRO_USB_B_HIROSE_ZX62R-B-5P")
      (footprint "eagle-import:USB_MICRO_B-HIROSE-ZX62R-B-5P")
      (libsource (lib "eagle-import") (part "MICRO_USB_B_HIROSE_ZX62R-B-5P"))
    )
    (comp (ref "J6")
      (value "MICRO_USB_B_HIROSE_ZX62R-B-5P")
      (footprint "eagle-import:USB_MICRO_B-HIROSE-ZX62R-B-5P")
      (libsource (lib "eagle-import") (part "MICRO_USB_B_HIROSE_ZX62R-B-5P"))
    )
    (comp (ref "LED1")
      (value "LED0603")
      (footprint "eagle-import:LED-0603")
      (libsource (lib "eagle-import") (part "LED0603"))
    )
    (comp (ref "LED2")
      (value "LED0603")
      (footprint "eagle-import:LED-0603")
      (libsource (lib "eagle-import") (part "LED0603"))
    )
    (comp (ref "LED3")
      (value "LED0603")
      (footprint "eagle-import:LED-0603")
      (libsource (lib "eagle-import") (part "LED0603"))
    )
    (comp (ref "LED4")
      (value "LED0603")
      (footprint "eagle-import:LED-0603")
      (libsource (lib "eagle-import") (part "LED0603"))
    )
    (comp (ref "Q2")
      (value "MOSFET-NCHANNELSMD")
      (footprint "eagle-import:SOT23-3")
      (libsource (lib "eagle-import") (part "MOSFET-NCHANNELSMD"))
    )
    (comp (ref "Q3")
      (value "MOSFET-NCHANNELSMD")
      (footprint "eagle-import:SOT23-3")
      (libsource (lib "eagle-import") (part "MOSFET-NCHANNELSMD"))
    )
    (comp (ref "Q4")
      (value "MOSFET-NCHANNELSMD")
      (footprint "eagle-import:SOT23-3")
      (libsource (lib "eagle-import") (part "MOSFET-NCHANNELSMD"))
    )
    (comp (ref "Q5")
      (value "MOSFET-NCHANNELSMD")
      (footprint "eagle-import:SOT23-3")
      (libsource (lib "eagle-import") (part "MOSFET-NCHANNELSMD"))
    )
    (comp (ref "R22")
      (value "1kΩ")
      (footprint "eagle-import:0603-RES")
      (libsource (lib "eagle-import") (part "RESISTOR0603_RES"))
    )
    (comp (ref "R23")
      (value "1kΩ")
      (footprint "eagle-import:0603-RES")
      (libsource (lib "eagle-import") (part "RESISTOR0603_RES"))
    )
    (comp (ref "R24")
      (value "1kΩ")
      (footprint "eagle-import:0603-RES")
      (libsource (lib "eagle-import") (part "RESISTOR0603_RES"))
    )
    (comp (ref "R25")
      (value "1kΩ")
      (footprint "eagle-import:0603-RES")
      (libsource (lib "eagle-import") (part "RESISTOR0603_RES"))
    )
    (comp (ref "R97")
      (value "1MΩ")
      (footprint "eagle-import:0603-RES")
      (libsource (lib "eagle-import") (part "RESISTOR0603_RES"))
    )
    (comp (ref "R98")
      (value "1MΩ")
      (footprint "eagle-import:0603-RES")
      (libsource (lib "eagle-import") (part "RESISTOR0603_RES"))
    )
    (comp (ref "R99")
      (value "1MΩ")
      (footprint "eagle-import:0603-RES")
      (libsource (lib "eagle-import") (part "RESISTOR0603_RES"))
    )
    (comp (ref "R100")
      (value "1MΩ")
      (footprint "eagle-import:0603-RES")
      (libsource (lib "eagle-import") (part "RESISTOR0603_RES"))
    )
    (comp (ref "TP21")
      (value "TEST_POINT_0.040IN")
      (footprint "eagle-import:TESTPOINT_0.040IN")
      (libsource (lib "eagle-import") (part "TEST_POINT_0.040IN"))
    )
    (comp (ref "TP38")
      (value "TEST_POINT_0.040IN")
      (footprint "eagle-import:TESTPOINT_0.040IN")
      (libsource (lib "eagle-import") (part "TEST_POINT_0.040IN"))
    )
    (comp (ref "TP39")
      (value "TEST_POINT_0.040IN")
      (footprint "eagle-import:TESTPOINT_0.040IN")
      (libsource (lib "eagle-import") (part "TEST_POINT_0.040IN"))
    )
    (comp (ref "TP40")
      (value "TEST_POINT_0.040IN")
      (footprint "eagle-import:TESTPOINT_0.040IN")
      (libsource (lib "eagle-import") (part "TEST_POINT_0.040IN"))
    )
    (comp (ref "U2")
      (value "FT232RQ")
      (footprint "eagle-import:QFN32")
      (libsource (lib "eagle-import") (part "FT232RQ"))
    )
    (comp (ref "U3")
      (value "FT232RQ")
      (footprint "eagle-import:QFN32")
      (libsource (lib "eagle-import") (part "FT232RQ"))
    )
    (comp (ref "C61")
      (value "100nF")
      (footprint "eagle-import:0603_CAP")
      (libsource (lib "eagle-import") (part "CAPACITOR0603_CAP"))
    )
    (comp (ref "J9")
      (value "MICRO_USB_B_HIROSE_ZX62R-B-5P")
      (footprint "eagle-import:USB_MICRO_B-HIROSE-ZX62R-B-5P")
      (libsource (lib "eagle-import") (part "MICRO_USB_B_HIROSE_ZX62R-B-5P"))
    )
    (comp (ref "Q1")
      (value "DMN32D2LDF")
      (footprint "eagle-import:SOT353")
      (libsource (lib "eagle-import") (part "DMN32D2LDF"))
    )
    (comp (ref "R89")
      (value "100kΩ")
      (footprint "eagle-import:0603-RES")
      (libsource (lib "eagle-import") (part "RESISTOR0603_RES"))
    )
    (comp (ref "R90")
      (value "100kΩ")
      (footprint "eagle-import:0603-RES")
      (libsource (lib "eagle-import") (part "RESISTOR0603_RES"))
    )
    (comp (ref "U23")
      (value "TS3USB30E")
      (footprint "eagle-import:UQFN-10")
      (libsource (lib "eagle-import") (part "TS3USB30E"))
    )
    (comp (ref "C55")
      (value "100nF")
      (footprint "eagle-import:0603_CAP")
      (libsource (lib "eagle-import") (part "CAPACITOR0603_CAP"))
    )
    (comp (ref "C56")
      (value "100nF")
      (footprint "eagle-import:0603_CAP")
      (libsource (lib "eagle-import") (part "CAPACITOR0603_CAP"))
    )
    (comp (ref "C57")
      (value "100nF")
      (footprint "eagle-import:0603_CAP")
      (libsource (lib "eagle-import") (part "CAPACITOR0603_CAP"))
    )
    (comp (ref "C58")
      (value "100nF")
      (footprint "eagle-import:0603_CAP")
      (libsource (lib "eagle-import") (part "CAPACITOR0603_CAP"))
    )
    (comp (ref "C59")
      (value "100nF")
      (footprint "eagle-import:0603_CAP")
      (libsource (lib "eagle-import") (part "CAPACITOR0603_CAP"))
    )
    (comp (ref "C60")
      (value "100nF")
      (footprint "eagle-import:0603_CAP")
      (libsource (lib "eagle-import") (part "CAPACITOR0603_CAP"))
    )
    (comp (ref "FB4")
      (value "600R")
      (footprint "eagle-import:0603_CAP")
      (libsource (lib "eagle-import") (part "FERRITE_BEAD0603"))
    )
    (comp (ref "FB5")
      (value "600R")
      (footprint "eagle-import:0603_CAP")
      (libsource (lib "eagle-import") (part "FERRITE_BEAD0603"))
    )
    (comp (ref "J7")
      (value "MICRO_USB_B_HIROSE_ZX62R-B-5P")
      (footprint "eagle-import:USB_MICRO_B-HIROSE-ZX62R-B-5P")
      (libsource (lib "eagle-import") (part "MICRO_USB_B_HIROSE_ZX62R-B-5P"))
    )
    (comp (ref "J8")
      (value "MICRO_USB_B_HIROSE_ZX62R-B-5P")
      (footprint "eagle-import:USB_MICRO_B-HIROSE-ZX62R-B-5P")
      (libsource (lib "eagle-import") (part "MICRO_USB_B_HIROSE_ZX62R-B-5P"))
    )
    (comp (ref "LED10")
      (value "LED0603")
      (footprint "eagle-import:LED-0603")
      (libsource (lib "eagle-import") (part "LED0603"))
    )
    (comp (ref "LED11")
      (value "LED0603")
      (footprint "eagle-import:LED-0603")
      (libsource (lib "eagle-import") (part "LED0603"))
    )
    (comp (ref "LED12")
      (value "LED0603")
      (footprint "eagle-import:LED-0603")
      (libsource (lib "eagle-import") (part "LED0603"))
    )
    (comp (ref "LED13")
      (value "LED0603")
      (footprint "eagle-import:LED-0603")
      (libsource (lib "eagle-import") (part "LED0603"))
    )
    (comp (ref "Q6")
      (value "MOSFET-NCHANNELSMD")
      (footprint "eagle-import:SOT23-3")
      (libsource (lib "eagle-import") (part "MOSFET-NCHANNELSMD"))
    )
    (comp (ref "Q7")
      (value "MOSFET-NCHANNELSMD")
      (footprint "eagle-import:SOT23-3")
      (libsource (lib "eagle-import") (part "MOSFET-NCHANNELSMD"))
    )
    (comp (ref "Q8")
      (value "MOSFET-NCHANNELSMD")
      (footprint "eagle-import:SOT23-3")
      (libsource (lib "eagle-import") (part "MOSFET-NCHANNELSMD"))
    )
    (comp (ref "Q9")
      (value "MOSFET-NCHANNELSMD")
      (footprint "eagle-import:SOT23-3")
      (libsource (lib "eagle-import") (part "MOSFET-NCHANNELSMD"))
    )
    (comp (ref "R36")
      (value "1kΩ")
      (footprint "eagle-import:0603-RES")
      (libsource (lib "eagle-import") (part "RESISTOR0603_RES"))
    )
    (comp (ref "R37")
      (value "1kΩ")
      (footprint "eagle-import:0603-RES")
      (libsource (lib "eagle-import") (part "RESISTOR0603_RES"))
    )
    (comp (ref "R38")
      (value "1kΩ")
      (footprint "eagle-import:0603-RES")
      (libsource (lib "eagle-import") (part "RESISTOR0603_RES"))
    )
    (comp (ref "R39")
      (value "1kΩ")
      (footprint "eagle-import:0603-RES")
      (libsource (lib "eagle-import") (part "RESISTOR0603_RES"))
    )
    (comp (ref "R101")
      (value "1MΩ")
      (footprint "eagle-import:0603-RES")
      (libsource (lib "eagle-import") (part "RESISTOR0603_RES"))
    )
    (comp (ref "R102")
      (value "1MΩ")
      (footprint "eagle-import:0603-RES")
      (libsource (lib "eagle-import") (part "RESISTOR0603_RES"))
    )
    (comp (ref "R103")
      (value "1MΩ")
      (footprint "eagle-import:0603-RES")
      (libsource (lib "eagle-import") (part "RESISTOR0603_RES"))
    )
    (comp (ref "R104")
      (value "1MΩ")
      (footprint "eagle-import:0603-RES")
      (libsource (lib "eagle-import") (part "RESISTOR0603_RES"))
    )
    (comp (ref "TP12")
      (value "TEST_POINT_0.040IN")
      (footprint "eagle-import:TESTPOINT_0.040IN")
      (libsource (lib "eagle-import") (part "TEST_POINT_0.040IN"))
    )
    (comp (ref "TP13")
      (value "TEST_POINT_0.040IN")
      (footprint "eagle-import:TESTPOINT_0.040IN")
      (libsource (lib "eagle-import") (part "TEST_POINT_0.040IN"))
    )
    (comp (ref "TP14")
      (value "TEST_POINT_0.040IN")
      (footprint "eagle-import:TESTPOINT_0.040IN")
      (libsource (lib "eagle-import") (part "TEST_POINT_0.040IN"))
    )
    (comp (ref "TP15")
      (value "TEST_POINT_0.040IN")
      (footprint "eagle-import:TESTPOINT_0.040IN")
      (libsource (lib "eagle-import") (part "TEST_POINT_0.040IN"))
    )
    (comp (ref "U4")
      (value "FT232RQ")
      (footprint "eagle-import:QFN32")
      (libsource (lib "eagle-import") (part "FT232RQ"))
    )
    (comp (ref "U5")
      (value "FT232RQ")
      (footprint "eagle-import:QFN32")
      (libsource (lib "eagle-import") (part "FT232RQ"))
    )
    (comp (ref "J2")
      (value "BACKPLANE_GENERIC_MODULE_DEBUG")
      (footprint "eagle-import:BACKPLANE_MODULE_14PIN_8PIN")
      (libsource (lib "eagle-import") (part "BACKPLANE_GENERIC_MODULE_DEBUG"))
    )
    (comp (ref "J3")
      (value "BACKPLANE_GENERIC_MODULE_DEBUG")
      (footprint "eagle-import:BACKPLANE_MODULE_14PIN_8PIN")
      (libsource (lib "eagle-import") (part "BACKPLANE_GENERIC_MODULE_DEBUG"))
    )
    (comp (ref "S4")
      (value "B3U-1000P")
      (footprint "eagle-import:B3U-1000P")
      (libsource (lib "eagle-import") (part "B3U-1000P"))
    )
    (comp (ref "S5")
      (value "B3U-1000P")
      (footprint "eagle-import:B3U-1000P")
      (libsource (lib "eagle-import") (part "B3U-1000P"))
    )
  )
  (nets
    (net (code "1") (name "3V3") (class "Default")
      (node (ref "C42") (pin "1") (pinfunction "1_1") (pintype "bidirectional"))
      (node (ref "C43") (pin "1") (pinfunction "1_1") (pintype "bidirectional"))
      (node (ref "C44") (pin "1") (pinfunction "1_1") (pintype "bidirectional"))
      (node (ref "C63") (pin "1") (pinfunction "1_1") (pintype "bidirectional"))
      (node (ref "FB6") (pin "2") (pinfunction "P$2_2") (pintype "bidirectional"))
      (node (ref "LED1") (pin "A") (pinfunction "ANODE_A") (pintype "bidirectional"))
      (node (ref "LED10") (pin "A") (pinfunction "ANODE_A") (pintype "bidirectional"))
      (node (ref "LED11") (pin "A") (pinfunction "ANODE_A") (pintype "bidirectional"))
      (node (ref "LED12") (pin "A") (pinfunction "ANODE_A") (pintype "bidirectional"))
      (node (ref "LED13") (pin "A") (pinfunction "ANODE_A") (pintype "bidirectional"))
      (node (ref "LED2") (pin "A") (pinfunction "ANODE_A") (pintype "bidirectional"))
      (node (ref "LED3") (pin "A") (pinfunction "ANODE_A") (pintype "bidirectional"))
      (node (ref "LED4") (pin "A") (pinfunction "ANODE_A") (pintype "bidirectional"))
      (node (ref "R2") (pin "2") (pinfunction "2_2") (pintype "passive"))
      (node (ref "R43") (pin "2") (pinfunction "2_2") (pintype "passive"))
      (node (ref "R44") (pin "2") (pinfunction "2_2") (pintype "passive"))
      (node (ref "R45") (pin "2") (pinfunction "2_2") (pintype "passive"))
      (node (ref "R71") (pin "2") (pinfunction "2_2") (pintype "passive"))
      (node (ref "R87") (pin "2") (pinfunction "2_2") (pintype "passive"))
      (node (ref "R88") (pin "2") (pinfunction "2_2") (pintype "passive"))
      (node (ref "S11") (pin "C") (pinfunction "INPUT_C") (pintype "bidirectional"))
      (node (ref "S14") (pin "14") (pinfunction "VCC_14") (pintype "bidirectional"))
      (node (ref "S15") (pin "14") (pinfunction "VCC_14") (pintype "bidirectional"))
      (node (ref "S16") (pin "10") (pinfunction "A_10") (pintype "bidirectional"))
      (node (ref "S16") (pin "14") (pinfunction "VCC_14") (pintype "bidirectional"))
      (node (ref "S17") (pin "10") (pinfunction "A_10") (pintype "bidirectional"))
      (node (ref "S17") (pin "14") (pinfunction "VCC_14") (pintype "bidirectional"))
      (node (ref "S18") (pin "10") (pinfunction "A_10") (pintype "bidirectional"))
      (node (ref "S18") (pin "14") (pinfunction "VCC_14") (pintype "bidirectional"))
      (node (ref "TP7") (pin "TESTPOINT") (pinfunction "TESTPOINT_TESTPOINT") (pintype "bidirectional"))
      (node (ref "U12") (pin "5") (pinfunction "OUT_5") (pintype "bidirectional"))
      (node (ref "U16") (pin "27") (pinfunction "VLCD_27") (pintype "bidirectional"))
      (node (ref "U16") (pin "31") (pinfunction "VLCDIN_31") (pintype "power_in"))
      (node (ref "U16") (pin "40") (pinfunction "VDDIO_40") (pintype "power_in"))
      (node (ref "U16") (pin "45") (pinfunction "VDDIO_45") (pintype "power_in"))
      (node (ref "U16") (pin "8") (pinfunction "VDDIN_8") (pintype "power_in"))
      (node (ref "U8") (pin "1") (pinfunction "SENSE+_1") (pintype "open_collector"))
    )
    (net (code "2") (name "5V") (class "Default")
      (node (ref "C62") (pin "1") (pinfunction "1_1") (pintype "bidirectional"))
      (node (ref "C70") (pin "1") (pinfunction "1_1") (pintype "bidirectional"))
      (node (ref "D9") (pin "A") (pinfunction "ANODE_A") (pintype "bidirectional"))
      (node (ref "Q10") (pin "2") (pinfunction "S_2") (pintype "passive"))
      (node (ref "R106") (pin "1") (pinfunction "1_1") (pintype "passive"))
      (node (ref "R3") (pin "2") (pinfunction "2_2") (pintype "passive"))
      (node (ref "R4") (pin "2") (pinfunction "2_2") (pintype "passive"))
      (node (ref "R46") (pin "2") (pinfunction "2_2") (pintype "passive"))
      (node (ref "R47") (pin "2") (pinfunction "2_2") (pintype "passive"))
      (node (ref "R48") (pin "2") (pinfunction "2_2") (pintype "passive"))
      (node (ref "R49") (pin "2") (pinfunction "2_2") (pintype "passive"))
      (node (ref "R5") (pin "2") (pinfunction "2_2") (pintype "passive"))
      (node (ref "R50") (pin "2") (pinfunction "2_2") (pintype "passive"))
      (node (ref "R51") (pin "2") (pinfunction "2_2") (pintype "passive"))
      (node (ref "R52") (pin "2") (pinfunction "2_2") (pintype "passive"))
      (node (ref "R53") (pin "2") (pinfunction "2_2") (pintype "passive"))
      (node (ref "R54") (pin "2") (pinfunction "2_2") (pintype "passive"))
      (node (ref "R70") (pin "2") (pinfunction "2_2") (pintype "passive"))
      (node (ref "TP4") (pin "TESTPOINT") (pinfunction "TESTPOINT_TESTPOINT") (pintype "bidirectional"))
      (node (ref "U10") (pin "1") (pinfunction "SENSE+_1") (pintype "open_collector"))
      (node (ref "U11") (pin "1") (pinfunction "SENSE+_1") (pintype "open_collector"))
      (node (ref "U12") (pin "1") (pinfunction "IN_1") (pintype "bidirectional"))
      (node (ref "U25") (pin "7") (pinfunction "OUT_7") (pintype "bidirectional"))
      (node (ref "U9") (pin "1") (pinfunction "SENSE+_1") (pintype "open_collector"))
    )
    (net (code "3") (name "CONT0_DBG_GPIO1") (class "Default")
      (node (ref "J1") (pin "101") (pinfunction "DBG_GPIO1_101") (pintype "bidirectional"))
      (node (ref "Q6") (pin "1") (pinfunction "G_1") (pintype "passive"))
      (node (ref "R101") (pin "2") (pinfunction "2_2") (pintype "passive"))
      (node (ref "TP12") (pin "TESTPOINT") (pinfunction "TESTPOINT_TESTPOINT") (pintype "bidirectional"))
    )
    (net (code "4") (name "CONT0_DBG_GPIO2") (class "Default")
      (node (ref "J1") (pin "104") (pinfunction "DBG_GPIO2_104") (pintype "bidirectional"))
      (node (ref "Q7") (pin "1") (pinfunction "G_1") (pintype "passive"))
      (node (ref "R102") (pin "2") (pinfunction "2_2") (pintype "passive"))
      (node (ref "TP13") (pin "TESTPOINT") (pinfunction "TESTPOINT_TESTPOINT") (pintype "bidirectional"))
    )
    (net (code "5") (name "CONT0_DBG_RX") (class "Default")
      (node (ref "J1") (pin "103") (pinfunction "DBG_RX_103") (pintype "bidirectional"))
      (node (ref "U4") (pin "30") (pinfunction "TXD_30") (pintype "output"))
    )
    (net (code "6") (name "CONT0_DBG_TX") (class "Default")
      (node (ref "J1") (pin "102") (pinfunction "DBG_TX_102") (pintype "bidirectional"))
      (node (ref "U4") (pin "2") (pinfunction "RXD_2") (pintype "input"))
    )
    (net (code "7") (name "CONT0_SWDCLK") (class "Default")
      (node (ref "J1") (pin "106") (pinfunction "DBG_SWDCLK_106") (pintype "bidirectional"))
      (node (ref "S17") (pin "3") (pinfunction "A_3") (pintype "bidirectional"))
    )
    (net (code "8") (name "CONT0_SWDIO") (class "Default")
      (node (ref "J1") (pin "107") (pinfunction "DBG_SWDIO_107") (pintype "bidirectional"))
      (node (ref "S17") (pin "2") (pinfunction "A_2") (pintype "bidirectional"))
    )
    (net (code "9") (name "CONT0_~{RESET}") (class "Default")
      (node (ref "J1") (pin "105") (pinfunction "DBG_~{RESET}_105") (pintype "bidirectional"))
      (node (ref "S17") (pin "9") (pinfunction "A_9") (pintype "bidirectional"))
      (node (ref "S6") (pin "2") (pinfunction "P$2_2") (pintype "passive"))
    )
    (net (code "10") (name "CONT1_DBG_GPIO1") (class "Default")
      (node (ref "J1") (pin "201") (pinfunction "DBG_GPIO1_201") (pintype "bidirectional"))
      (node (ref "Q8") (pin "1") (pinfunction "G_1") (pintype "passive"))
      (node (ref "R103") (pin "2") (pinfunction "2_2") (pintype "passive"))
      (node (ref "TP14") (pin "TESTPOINT") (pinfunction "TESTPOINT_TESTPOINT") (pintype "bidirectional"))
    )
    (net (code "11") (name "CONT1_DBG_GPIO2") (class "Default")
      (node (ref "J1") (pin "204") (pinfunction "DBG_GPIO2_204") (pintype "bidirectional"))
      (node (ref "Q9") (pin "1") (pinfunction "G_1") (pintype "passive"))
      (node (ref "R104") (pin "2") (pinfunction "2_2") (pintype "passive"))
      (node (ref "TP15") (pin "TESTPOINT") (pinfunction "TESTPOINT_TESTPOINT") (pintype "bidirectional"))
    )
    (net (code "12") (name "CONT1_DBG_RX") (class "Default")
      (node (ref "J1") (pin "203") (pinfunction "DBG_RX_203") (pintype "bidirectional"))
      (node (ref "U5") (pin "30") (pinfunction "TXD_30") (pintype "output"))
    )
    (net (code "13") (name "CONT1_DBG_TX") (class "Default")
      (node (ref "J1") (pin "202") (pinfunction "DBG_TX_202") (pintype "bidirectional"))
      (node (ref "U5") (pin "2") (pinfunction "RXD_2") (pintype "input"))
    )
    (net (code "14") (name "CONT1_SWDCLK") (class "Default")
      (node (ref "J1") (pin "206") (pinfunction "DBG_SWDCLK_206") (pintype "bidirectional"))
      (node (ref "S18") (pin "3") (pinfunction "A_3") (pintype "bidirectional"))
    )
    (net (code "15") (name "CONT1_SWDIO") (class "Default")
      (node (ref "J1") (pin "207") (pinfunction "DBG_SWDIO_207") (pintype "bidirectional"))
      (node (ref "S18") (pin "2") (pinfunction "A_2") (pintype "bidirectional"))
    )
    (net (code "16") (name "CONT1_~{RESET}") (class "Default")
      (node (ref "J1") (pin "205") (pinfunction "DBG_~{RESET}_205") (pintype "bidirectional"))
      (node (ref "S18") (pin "9") (pinfunction "A_9") (pintype "bidirectional"))
      (node (ref "S7") (pin "2") (pinfunction "P$2_2") (pintype "passive"))
    )
    (net (code "17") (name "CONTROLLER_XIN") (class "Default")
      (node (ref "C1") (pin "1") (pinfunction "1_1") (pintype "bidirectional"))
      (node (ref "U16") (pin "1") (pinfunction "PA00_1") (pintype "bidirectional"))
      (node (ref "X1") (pin "3") (pinfunction "2_3") (pintype "bidirectional"))
    )
    (net (code "18") (name "CONTROLLER_XOUT") (class "Default")
      (node (ref "C2") (pin "1") (pinfunction "1_1") (pintype "bidirectional"))
      (node (ref "U16") (pin "2") (pinfunction "PA01_2") (pintype "bidirectional"))
      (node (ref "X1") (pin "1") (pinfunction "1_1") (pintype "bidirectional"))
    )
    (net (code "19") (name "CONT_MOD0_IN") (class "Default")
      (node (ref "J1") (pin "9") (pinfunction "MOD0_IN_9") (pintype "bidirectional"))
      (node (ref "U17") (pin "2") (pinfunction "A1_2") (pintype "bidirectional"))
    )
    (net (code "20") (name "CONT_MOD0_OUT") (class "Default")
      (node (ref "J1") (pin "10") (pinfunction "MOD0_OUT_10") (pintype "bidirectional"))
      (node (ref "U19") (pin "2") (pinfunction "A1_2") (pintype "bidirectional"))
    )
    (net (code "21") (name "CONT_MOD1_IN") (class "Default")
      (node (ref "J1") (pin "11") (pinfunction "MOD1_IN_11") (pintype "bidirectional"))
      (node (ref "U18") (pin "2") (pinfunction "A1_2") (pintype "bidirectional"))
    )
    (net (code "22") (name "CONT_MOD1_OUT") (class "Default")
      (node (ref "J1") (pin "12") (pinfunction "MOD1_OUT_12") (pintype "bidirectional"))
      (node (ref "U20") (pin "2") (pinfunction "A1_2") (pintype "bidirectional"))
    )
    (net (code "23") (name "CONT_MOD2_IN") (class "Default")
      (node (ref "J1") (pin "13") (pinfunction "MOD2_IN_13") (pintype "bidirectional"))
      (node (ref "U16") (pin "39") (pinfunction "PA20_39") (pintype "bidirectional"))
    )
    (net (code "24") (name "CONT_MOD2_OUT") (class "Default")
      (node (ref "J1") (pin "14") (pinfunction "MOD2_OUT_14") (pintype "bidirectional"))
      (node (ref "U16") (pin "38") (pinfunction "PA19_38") (pintype "bidirectional"))
    )
    (net (code "25") (name "CONT_USB+") (class "Default")
      (node (ref "J1") (pin "27") (pinfunction "USB_D+_27") (pintype "bidirectional"))
      (node (ref "U23") (pin "2") (pinfunction "D2+_2") (pintype "bidirectional"))
    )
    (net (code "26") (name "CONT_USB-") (class "Default")
      (node (ref "J1") (pin "28") (pinfunction "USB_D-_28") (pintype "bidirectional"))
      (node (ref "U23") (pin "6") (pinfunction "D2-_6") (pintype "bidirectional"))
    )
    (net (code "27") (name "GND") (class "Default")
      (node (ref "C1") (pin "2") (pinfunction "2_2") (pintype "bidirectional"))
      (node (ref "C10") (pin "2") (pinfunction "2_2") (pintype "bidirectional"))
      (node (ref "C11") (pin "2") (pinfunction "2_2") (pintype "bidirectional"))
      (node (ref "C12") (pin "2") (pinfunction "2_2") (pintype "bidirectional"))
      (node (ref "C13") (pin "2") (pinfunction "2_2") (pintype "bidirectional"))
      (node (ref "C14") (pin "2") (pinfunction "2_2") (pintype "bidirectional"))
      (node (ref "C15") (pin "2") (pinfunction "2_2") (pintype "bidirectional"))
      (node (ref "C16") (pin "2") (pinfunction "2_2") (pintype "bidirectional"))
      (node (ref "C17") (pin "2") (pinfunction "2_2") (pintype "bidirectional"))
      (node (ref "C18") (pin "2") (pinfunction "2_2") (pintype "bidirectional"))
      (node (ref "C19") (pin "2") (pinfunction "2_2") (pintype "bidirectional"))
      (node (ref "C2") (pin "2") (pinfunction "2_2") (pintype "bidirectional"))
      (node (ref "C20") (pin "2") (pinfunction "2_2") (pintype "bidirectional"))
      (node (ref "C21") (pin "2") (pinfunction "2_2") (pintype "bidirectional"))
      (node (ref "C22") (pin "2") (pinfunction "2_2") (pintype "bidirectional"))
      (node (ref "C23") (pin "2") (pinfunction "2_2") (pintype "bidirectional"))
      (node (ref "C24") (pin "2") (pinfunction "2_2") (pintype "bidirectional"))
      (node (ref "C25") (pin "2") (pinfunction "2_2") (pintype "bidirectional"))
      (node (ref "C26") (pin "2") (pinfunction "2_2") (pintype "bidirectional"))
      (node (ref "C27") (pin "2") (pinfunction "2_2") (pintype "bidirectional"))
      (node (ref "C28") (pin "1") (pinfunction "1_1") (pintype "bidirectional"))
      (node (ref "C29") (pin "2") (pinfunction "2_2") (pintype "bidirectional"))
      (node (ref "C3") (pin "1") (pinfunction "1_1") (pintype "bidirectional"))
      (node (ref "C30") (pin "2") (pinfunction "2_2") (pintype "bidirectional"))
      (node (ref "C31") (pin "2") (pinfunction "2_2") (pintype "bidirectional"))
      (node (ref "C32") (pin "2") (pinfunction "2_2") (pintype "bidirectional"))
      (node (ref "C33") (pin "2") (pinfunction "2_2") (pintype "bidirectional"))
      (node (ref "C34") (pin "2") (pinfunction "2_2") (pintype "bidirectional"))
      (node (ref "C35") (pin "2") (pinfunction "2_2") (pintype "bidirectional"))
      (node (ref "C36") (pin "2") (pinfunction "2_2") (pintype "bidirectional"))
      (node (ref "C37") (pin "1") (pinfunction "1_1") (pintype "bidirectional"))
      (node (ref "C38") (pin "1") (pinfunction "1_1") (pintype "bidirectional"))
      (node (ref "C39") (pin "2") (pinfunction "2_2") (pintype "bidirectional"))
      (node (ref "C4") (pin "1") (pinfunction "1_1") (pintype "bidirectional"))
      (node (ref "C40") (pin "2") (pinfunction "2_2") (pintype "bidirectional"))
      (node (ref "C41") (pin "2") (pinfunction "2_2") (pintype "bidirectional"))
      (node (ref "C42") (pin "2") (pinfunction "2_2") (pintype "bidirectional"))
      (node (ref "C43") (pin "2") (pinfunction "2_2") (pintype "bidirectional"))
      (node (ref "C44") (pin "2") (pinfunction "2_2") (pintype "bidirectional"))
      (node (ref "C45") (pin "2") (pinfunction "2_2") (pintype "bidirectional"))
      (node (ref "C46") (pin "2") (pinfunction "2_2") (pintype "bidirectional"))
      (node (ref "C47") (pin "2") (pinfunction "2_2") (pintype "bidirectional"))
      (node (ref "C48") (pin "2") (pinfunction "2_2") (pintype "bidirectional"))
      (node (ref "C49") (pin "2") (pinfunction "2_2") (pintype "bidirectional"))
      (node (ref "C5") (pin "2") (pinfunction "2_2") (pintype "bidirectional"))
      (node (ref "C50") (pin "2") (pinfunction "2_2") (pintype "bidirectional"))
      (node (ref "C51") (pin "2") (pinfunction "2_2") (pintype "bidirectional"))
      (node (ref "C52") (pin "2") (pinfunction "2_2") (pintype "bidirectional"))
      (node (ref "C53") (pin "2") (pinfunction "2_2") (pintype "bidirectional"))
      (node (ref "C54") (pin "2") (pinfunction "2_2") (pintype "bidirectional"))
      (node (ref "C55") (pin "2") (pinfunction "2_2") (pintype "bidirectional"))
      (node (ref "C56") (pin "2") (pinfunction "2_2") (pintype "bidirectional"))
      (node (ref "C57") (pin "2") (pinfunction "2_2") (pintype "bidirectional"))
      (node (ref "C58") (pin "2") (pinfunction "2_2") (pintype "bidirectional"))
      (node (ref "C59") (pin "2") (pinfunction "2_2") (pintype "bidirectional"))
      (node (ref "C6") (pin "2") (pinfunction "2_2") (pintype "bidirectional"))
      (node (ref "C60") (pin "2") (pinfunction "2_2") (pintype "bidirectional"))
      (node (ref "C61") (pin "1") (pinfunction "1_1") (pintype "bidirectional"))
      (node (ref "C62") (pin "2") (pinfunction "2_2") (pintype "bidirectional"))
      (node (ref "C63") (pin "2") (pinfunction "2_2") (pintype "bidirectional"))
      (node (ref "C64") (pin "2") (pinfunction "2_2") (pintype "bidirectional"))
      (node (ref "C65") (pin "2") (pinfunction "2_2") (pintype "bidirectional"))
      (node (ref "C66") (pin "1") (pinfunction "1_1") (pintype "bidirectional"))
      (node (ref "C67") (pin "2") (pinfunction "2_2") (pintype "bidirectional"))
      (node (ref "C68") (pin "2") (pinfunction "2_2") (pintype "bidirectional"))
      (node (ref "C69") (pin "2") (pinfunction "2_2") (pintype "bidirectional"))
      (node (ref "C7") (pin "2") (pinfunction "2_2") (pintype "bidirectional"))
      (node (ref "C70") (pin "2") (pinfunction "2_2") (pintype "bidirectional"))
      (node (ref "C8") (pin "2") (pinfunction "2_2") (pintype "bidirectional"))
      (node (ref "C9") (pin "2") (pinfunction "2_2") (pintype "bidirectional"))
      (node (ref "D7") (pin "1") (pinfunction "GND_1") (pintype "bidirectional"))
      (node (ref "D7") (pin "3") (pinfunction "GND_3") (pintype "bidirectional"))
      (node (ref "D7") (pin "5") (pinfunction "GND_5") (pintype "bidirectional"))
      (node (ref "D7") (pin "7") (pinfunction "GND_7") (pintype "bidirectional"))
      (node (ref "D8") (pin "1") (pinfunction "GND_1") (pintype "bidirectional"))
      (node (ref "D8") (pin "3") (pinfunction "GND_3") (pintype "bidirectional"))
      (node (ref "D8") (pin "5") (pinfunction "GND_5") (pintype "bidirectional"))
      (node (ref "D8") (pin "7") (pinfunction "GND_7") (pintype "bidirectional"))
      (node (ref "J1") (pin "1") (pinfunction "GND_1") (pintype "bidirectional"))
      (node (ref "J1") (pin "100") (pinfunction "GND1_100") (pintype "bidirectional"))
      (node (ref "J1") (pin "200") (pinfunction "GND1_200") (pintype "bidirectional"))
      (node (ref "J1") (pin "21") (pinfunction "GND_21") (pintype "bidirectional"))
      (node (ref "J1") (pin "MNT1") (pinfunction "GND_MNT1") (pintype "bidirectional"))
      (node (ref "J1") (pin "MNT2") (pinfunction "GND_MNT2") (pintype "bidirectional"))
      (node (ref "J1") (pin "MNT3") (pinfunction "GND_MNT3") (pintype "bidirectional"))
      (node (ref "J1") (pin "MNT4") (pinfunction "GND_MNT4") (pintype "bidirectional"))
      (node (ref "J10") (pin "10") (pinfunction "10_10") (pintype "passive"))
      (node (ref "J10") (pin "12") (pinfunction "12_12") (pintype "passive"))
      (node (ref "J10") (pin "14") (pinfunction "14_14") (pintype "passive"))
      (node (ref "J10") (pin "16") (pinfunction "16_16") (pintype "passive"))
      (node (ref "J10") (pin "18") (pinfunction "18_18") (pintype "passive"))
      (node (ref "J10") (pin "20") (pinfunction "20_20") (pintype "passive"))
      (node (ref "J10") (pin "4") (pinfunction "4_4") (pintype "passive"))
      (node (ref "J10") (pin "6") (pinfunction "6_6") (pintype "passive"))
      (node (ref "J10") (pin "8") (pinfunction "8_8") (pintype "passive"))
      (node (ref "J11") (pin "2") (pinfunction "GND_2") (pintype "bidirectional"))
      (node (ref "J2") (pin "1") (pinfunction "GND_1") (pintype "bidirectional"))
      (node (ref "J2") (pin "14") (pinfunction "GND_14") (pintype "bidirectional"))
      (node (ref "J2") (pin "15") (pinfunction "GND_15") (pintype "bidirectional"))
      (node (ref "J2") (pin "MNT1") (pinfunction "GND_MNT1") (pintype "bidirectional"))
      (node (ref "J2") (pin "MNT2") (pinfunction "GND_MNT2") (pintype "bidirectional"))
      (node (ref "J2") (pin "MNT3") (pinfunction "GND_MNT3") (pintype "bidirectional"))
      (node (ref "J2") (pin "MNT4") (pinfunction "GND_MNT4") (pintype "bidirectional"))
      (node (ref "J3") (pin "1") (pinfunction "GND_1") (pintype "bidirectional"))
      (node (ref "J3") (pin "14") (pinfunction "GND_14") (pintype "bidirectional"))
      (node (ref "J3") (pin "15") (pinfunction "GND_15") (pintype "bidirectional"))
      (node (ref "J3") (pin "MNT1") (pinfunction "GND_MNT1") (pintype "bidirectional"))
      (node (ref "J3") (pin "MNT2") (pinfunction "GND_MNT2") (pintype "bidirectional"))
      (node (ref "J3") (pin "MNT3") (pinfunction "GND_MNT3") (pintype "bidirectional"))
      (node (ref "J3") (pin "MNT4") (pinfunction "GND_MNT4") (pintype "bidirectional"))
      (node (ref "J4") (pin "5") (pinfunction "GND_5") (pintype "bidirectional"))
      (node (ref "J5") (pin "5") (pinfunction "GND_5") (pintype "bidirectional"))
      (node (ref "J6") (pin "5") (pinfunction "GND_5") (pintype "bidirectional"))
      (node (ref "J7") (pin "5") (pinfunction "GND_5") (pintype "bidirectional"))
      (node (ref "J8") (pin "5") (pinfunction "GND_5") (pintype "bidirectional"))
      (node (ref "J9") (pin "5") (pinfunction "GND_5") (pintype "bidirectional"))
      (node (ref "LED5") (pin "C") (pinfunction "CATHODE_C") (pintype "bidirectional"))
      (node (ref "LED6") (pin "C") (pinfunction "CATHODE_C") (pintype "bidirectional"))
      (node (ref "LED7") (pin "C") (pinfunction "CATHODE_C") (pintype "bidirectional"))
      (node (ref "LED8") (pin "C") (pinfunction "CATHODE_C") (pintype "bidirectional"))
      (node (ref "LED9") (pin "C") (pinfunction "CATHODE_C") (pintype "bidirectional"))
      (node (ref "Q1") (pin "S") (pinfunction "S_S") (pintype "bidirectional"))
      (node (ref "Q2") (pin "2") (pinfunction "S_2") (pintype "passive"))
      (node (ref "Q3") (pin "2") (pinfunction "S_2") (pintype "passive"))
      (node (ref "Q4") (pin "2") (pinfunction "S_2") (pintype "passive"))
      (node (ref "Q5") (pin "2") (pinfunction "S_2") (pintype "passive"))
      (node (ref "Q6") (pin "2") (pinfunction "S_2") (pintype "passive"))
      (node (ref "Q7") (pin "2") (pinfunction "S_2") (pintype "passive"))
      (node (ref "Q8") (pin "2") (pinfunction "S_2") (pintype "passive"))
      (node (ref "Q9") (pin "2") (pinfunction "S_2") (pintype "passive"))
      (node (ref "R1") (pin "1") (pinfunction "1_1") (pintype "passive"))
      (node (ref "R100") (pin "1") (pinfunction "1_1") (pintype "passive"))
      (node (ref "R101") (pin "1") (pinfunction "1_1") (pintype "passive"))
      (node (ref "R102") (pin "1") (pinfunction "1_1") (pintype "passive"))
      (node (ref "R103") (pin "1") (pinfunction "1_1") (pintype "passive"))
      (node (ref "R104") (pin "1") (pinfunction "1_1") (pintype "passive"))
      (node (ref "R12") (pin "2") (pinfunction "2_2") (pintype "passive"))
      (node (ref "R13") (pin "2") (pinfunction "2_2") (pintype "passive"))
      (node (ref "R14") (pin "2") (pinfunction "2_2") (pintype "passive"))
      (node (ref "R15") (pin "2") (pinfunction "2_2") (pintype "passive"))
      (node (ref "R16") (pin "1") (pinfunction "1_1") (pintype "passive"))
      (node (ref "R17") (pin "1") (pinfunction "1_1") (pintype "passive"))
      (node (ref "R18") (pin "1") (pinfunction "1_1") (pintype "passive"))
      (node (ref "R19") (pin "1") (pinfunction "1_1") (pintype "passive"))
      (node (ref "R20") (pin "1") (pinfunction "1_1") (pintype "passive"))
      (node (ref "R21") (pin "1") (pinfunction "1_1") (pintype "passive"))
      (node (ref "R26") (pin "1") (pinfunction "1_1") (pintype "passive"))
      (node (ref "R27") (pin "1") (pinfunction "1_1") (pintype "passive"))
      (node (ref "R28") (pin "1") (pinfunction "1_1") (pintype "passive"))
      (node (ref "R29") (pin "1") (pinfunction "1_1") (pintype "passive"))
      (node (ref "R30") (pin "1") (pinfunction "1_1") (pintype "passive"))
      (node (ref "R73") (pin "1") (pinfunction "1_1") (pintype "passive"))
      (node (ref "R74") (pin "1") (pinfunction "1_1") (pintype "passive"))
      (node (ref "R75") (pin "1") (pinfunction "1_1") (pintype "passive"))
      (node (ref "R76") (pin "1") (pinfunction "1_1") (pintype "passive"))
      (node (ref "R77") (pin "1") (pinfunction "1_1") (pintype "passive"))
      (node (ref "R78") (pin "1") (pinfunction "1_1") (pintype "passive"))
      (node (ref "R79") (pin "2") (pinfunction "2_2") (pintype "passive"))
      (node (ref "R80") (pin "2") (pinfunction "2_2") (pintype "passive"))
      (node (ref "R81") (pin "2") (pinfunction "2_2") (pintype "passive"))
      (node (ref "R82") (pin "2") (pinfunction "2_2") (pintype "passive"))
      (node (ref "R83") (pin "2") (pinfunction "2_2") (pintype "passive"))
      (node (ref "R84") (pin "2") (pinfunction "2_2") (pintype "passive"))
      (node (ref "R85") (pin "2") (pinfunction "2_2") (pintype "passive"))
      (node (ref "R86") (pin "2") (pinfunction "2_2") (pintype "passive"))
      (node (ref "R90") (pin "1") (pinfunction "1_1") (pintype "passive"))
      (node (ref "R91") (pin "1") (pinfunction "1_1") (pintype "passive"))
      (node (ref "R92") (pin "1") (pinfunction "1_1") (pintype "passive"))
      (node (ref "R93") (pin "1") (pinfunction "1_1") (pintype "passive"))
      (node (ref "R94") (pin "1") (pinfunction "1_1") (pintype "passive"))
      (node (ref "R95") (pin "1") (pinfunction "1_1") (pintype "passive"))
      (node (ref "R96") (pin "1") (pinfunction "1_1") (pintype "passive"))
      (node (ref "R97") (pin "1") (pinfunction "1_1") (pintype "passive"))
      (node (ref "R98") (pin "1") (pinfunction "1_1") (pintype "passive"))
      (node (ref "R99") (pin "1") (pinfunction "1_1") (pintype "passive"))
      (node (ref "S1") (pin "1") (pinfunction "GND_1") (pintype "bidirectional"))
      (node (ref "S1") (pin "PAD") (pinfunction "GND_PAD") (pintype "bidirectional"))
      (node (ref "S10") (pin "2") (pinfunction "GND_2") (pintype "bidirectional"))
      (node (ref "S12") (pin "2") (pinfunction "GND_2") (pintype "bidirectional"))
      (node (ref "S12") (pin "PAD") (pinfunction "GND_PAD") (pintype "bidirectional"))
      (node (ref "S13") (pin "2") (pinfunction "GND_2") (pintype "bidirectional"))
      (node (ref "S13") (pin "PAD") (pinfunction "GND_PAD") (pintype "bidirectional"))
      (node (ref "S14") (pin "7") (pinfunction "GND_7") (pintype "bidirectional"))
      (node (ref "S15") (pin "7") (pinfunction "GND_7") (pintype "bidirectional"))
      (node (ref "S16") (pin "7") (pinfunction "GND_7") (pintype "bidirectional"))
      (node (ref "S17") (pin "7") (pinfunction "GND_7") (pintype "bidirectional"))
      (node (ref "S18") (pin "7") (pinfunction "GND_7") (pintype "bidirectional"))
      (node (ref "S2") (pin "1") (pinfunction "GND_1") (pintype "bidirectional"))
      (node (ref "S2") (pin "PAD") (pinfunction "GND_PAD") (pintype "bidirectional"))
      (node (ref "S3") (pin "1") (pinfunction "P$1_1") (pintype "passive"))
      (node (ref "S4") (pin "1") (pinfunction "P$1_1") (pintype "passive"))
      (node (ref "S5") (pin "1") (pinfunction "P$1_1") (pintype "passive"))
      (node (ref "S6") (pin "1") (pinfunction "P$1_1") (pintype "passive"))
      (node (ref "S7") (pin "1") (pinfunction "P$1_1") (pintype "passive"))
      (node (ref "S8") (pin "1") (pinfunction "P$1_1") (pintype "passive"))
      (node (ref "S9") (pin "2") (pinfunction "GND_2") (pintype "bidirectional"))
      (node (ref "TP11") (pin "TESTPOINT") (pinfunction "TESTPOINT_TESTPOINT") (pintype "bidirectional"))
      (node (ref "TP19") (pin "TESTPOINT") (pinfunction "TESTPOINT_TESTPOINT") (pintype "bidirectional"))
      (node (ref "TP25") (pin "TESTPOINT") (pinfunction "TESTPOINT_TESTPOINT") (pintype "bidirectional"))
      (node (ref "TP27") (pin "TESTPOINT") (pinfunction "TESTPOINT_TESTPOINT") (pintype "bidirectional"))
      (node (ref "TP51") (pin "TESTPOINT") (pinfunction "TESTPOINT_TESTPOINT") (pintype "bidirectional"))
      (node (ref "TP54") (pin "TESTPOINT") (pinfunction "TESTPOINT_TESTPOINT") (pintype "bidirectional"))
      (node (ref "TP56") (pin "TESTPOINT") (pinfunction "TESTPOINT_TESTPOINT") (pintype "bidirectional"))
      (node (ref "U1") (pin "17") (pinfunction "GND_17") (pintype "power_in"))
      (node (ref "U1") (pin "20") (pinfunction "GND_20") (pintype "power_in"))
      (node (ref "U1") (pin "24") (pinfunction "GND_24") (pintype "power_in"))
      (node (ref "U1") (pin "26") (pinfunction "TEST_26") (pintype "input"))
      (node (ref "U1") (pin "4") (pinfunction "GND_4") (pintype "power_in"))
      (node (ref "U10") (pin "2") (pinfunction "GND_2") (pintype "open_collector"))
      (node (ref "U11") (pin "2") (pinfunction "GND_2") (pintype "open_collector"))
      (node (ref "U12") (pin "2") (pinfunction "GND_2") (pintype "bidirectional"))
      (node (ref "U13") (pin "1") (pinfunction "A2_1") (pintype "bidirectional"))
      (node (ref "U13") (pin "17") (pinfunction "GND_17") (pintype "bidirectional"))
      (node (ref "U13") (pin "2") (pinfunction "A1_2") (pintype "bidirectional"))
      (node (ref "U13") (pin "3") (pinfunction "A0_3") (pintype "bidirectional"))
      (node (ref "U13") (pin "GND") (pinfunction "GND_GND") (pintype "bidirectional"))
      (node (ref "U14") (pin "1") (pinfunction "A2_1") (pintype "bidirectional"))
      (node (ref "U14") (pin "17") (pinfunction "GND_17") (pintype "bidirectional"))
      (node (ref "U14") (pin "2") (pinfunction "A1_2") (pintype "bidirectional"))
      (node (ref "U14") (pin "GND") (pinfunction "GND_GND") (pintype "bidirectional"))
      (node (ref "U15") (pin "1") (pinfunction "A0_1") (pintype "bidirectional"))
      (node (ref "U15") (pin "10") (pinfunction "GND_10") (pintype "bidirectional"))
      (node (ref "U15") (pin "2") (pinfunction "A1_2") (pintype "bidirectional"))
      (node (ref "U15") (pin "3") (pinfunction "A2_3") (pintype "bidirectional"))
      (node (ref "U16") (pin "17") (pinfunction "GNDANA_17") (pintype "power_in"))
      (node (ref "U16") (pin "30") (pinfunction "GND_30") (pintype "power_in"))
      (node (ref "U16") (pin "48") (pinfunction "GND_48") (pintype "power_in"))
      (node (ref "U16") (pin "6") (pinfunction "GND_6") (pintype "power_in"))
      (node (ref "U16") (pin "THERMAL") (pinfunction "GND_THERMAL") (pintype "power_in"))
      (node (ref "U17") (pin "4") (pinfunction "GND_4") (pintype "bidirectional"))
      (node (ref "U18") (pin "4") (pinfunction "GND_4") (pintype "bidirectional"))
      (node (ref "U19") (pin "4") (pinfunction "GND_4") (pintype "bidirectional"))
      (node (ref "U19") (pin "5") (pinfunction "DIR_5") (pintype "bidirectional"))
      (node (ref "U2") (pin "17") (pinfunction "GND_17") (pintype "power_in"))
      (node (ref "U2") (pin "20") (pinfunction "GND_20") (pintype "power_in"))
      (node (ref "U2") (pin "24") (pinfunction "GND_24") (pintype "power_in"))
      (node (ref "U2") (pin "26") (pinfunction "TEST_26") (pintype "input"))
      (node (ref "U2") (pin "4") (pinfunction "GND_4") (pintype "power_in"))
      (node (ref "U20") (pin "4") (pinfunction "GND_4") (pintype "bidirectional"))
      (node (ref "U20") (pin "5") (pinfunction "DIR_5") (pintype "bidirectional"))
      (node (ref "U21") (pin "10") (pinfunction "S_10") (pintype "bidirectional"))
      (node (ref "U21") (pin "4") (pinfunction "GND_4") (pintype "bidirectional"))
      (node (ref "U22") (pin "10") (pinfunction "S_10") (pintype "bidirectional"))
      (node (ref "U22") (pin "4") (pinfunction "GND_4") (pintype "bidirectional"))
      (node (ref "U23") (pin "4") (pinfunction "GND_4") (pintype "bidirectional"))
      (node (ref "U23") (pin "8") (pinfunction "~{OE}_8") (pintype "bidirectional"))
      (node (ref "U24") (pin "10") (pinfunction "~{BUSPWR}_10") (pintype "bidirectional"))
      (node (ref "U24") (pin "24") (pinfunction "GND_24") (pintype "bidirectional"))
      (node (ref "U24") (pin "43") (pinfunction "GND_43") (pintype "bidirectional"))
      (node (ref "U24") (pin "48") (pinfunction "MODE_48") (pintype "bidirectional"))
      (node (ref "U24") (pin "5") (pinfunction "GND_5") (pintype "bidirectional"))
      (node (ref "U25") (pin "2") (pinfunction "GND_2") (pintype "bidirectional"))
      (node (ref "U25") (pin "3") (pinfunction "GND_3") (pintype "bidirectional"))
      (node (ref "U25") (pin "4") (pinfunction "GND_4") (pintype "bidirectional"))
      (node (ref "U25") (pin "6") (pinfunction "~{ON}_6") (pintype "bidirectional"))
      (node (ref "U3") (pin "17") (pinfunction "GND_17") (pintype "power_in"))
      (node (ref "U3") (pin "20") (pinfunction "GND_20") (pintype "power_in"))
      (node (ref "U3") (pin "24") (pinfunction "GND_24") (pintype "power_in"))
      (node (ref "U3") (pin "26") (pinfunction "TEST_26") (pintype "input"))
      (node (ref "U3") (pin "4") (pinfunction "GND_4") (pintype "power_in"))
      (node (ref "U4") (pin "17") (pinfunction "GND_17") (pintype "power_in"))
      (node (ref "U4") (pin "20") (pinfunction "GND_20") (pintype "power_in"))
      (node (ref "U4") (pin "24") (pinfunction "GND_24") (pintype "power_in"))
      (node (ref "U4") (pin "26") (pinfunction "TEST_26") (pintype "input"))
      (node (ref "U4") (pin "4") (pinfunction "GND_4") (pintype "power_in"))
      (node (ref "U5") (pin "17") (pinfunction "GND_17") (pintype "power_in"))
      (node (ref "U5") (pin "20") (pinfunction "GND_20") (pintype "power_in"))
      (node (ref "U5") (pin "24") (pinfunction "GND_24") (pintype "power_in"))
      (node (ref "U5") (pin "26") (pinfunction "TEST_26") (pintype "input"))
      (node (ref "U5") (pin "4") (pinfunction "GND_4") (pintype "power_in"))
      (node (ref "U6") (pin "4") (pinfunction "GND_4") (pintype "bidirectional"))
      (node (ref "U7") (pin "4") (pinfunction "GND_4") (pintype "bidirectional"))
      (node (ref "U8") (pin "2") (pinfunction "GND_2") (pintype "open_collector"))
      (node (ref "U9") (pin "2") (pinfunction "GND_2") (pintype "open_collector"))
      (node (ref "X1") (pin "2") (pinfunction "GND_2") (pintype "bidirectional"))
      (node (ref "X1") (pin "4") (pinfunction "GND_4") (pintype "bidirectional"))
    )
    (net (code "28") (name "HUB_CFG") (class "Default")
      (node (ref "TP28") (pin "TESTPOINT") (pinfunction "TESTPOINT_TESTPOINT") (pintype "bidirectional"))
      (node (ref "U24") (pin "40") (pinfunction "HUBCFG_40") (pintype "bidirectional"))
    )
    (net (code "29") (name "HUB_DM1") (class "Default")
      (node (ref "C8") (pin "1") (pinfunction "1_1") (pintype "bidirectional"))
      (node (ref "R9") (pin "2") (pinfunction "P$2_2") (pintype "passive"))
      (node (ref "U24") (pin "13") (pinfunction "DM1_13") (pintype "bidirectional"))
    )
    (net (code "30") (name "HUB_DM2") (class "Default")
      (node (ref "C6") (pin "1") (pinfunction "1_1") (pintype "bidirectional"))
      (node (ref "R7") (pin "2") (pinfunction "P$2_2") (pintype "passive"))
      (node (ref "U24") (pin "17") (pinfunction "DM2_17") (pintype "bidirectional"))
    )
    (net (code "31") (name "HUB_DM3") (class "Default")
      (node (ref "C10") (pin "1") (pinfunction "1_1") (pintype "bidirectional"))
      (node (ref "R11") (pin "2") (pinfunction "P$2_2") (pintype "passive"))
      (node (ref "U24") (pin "21") (pinfunction "DM3_21") (pintype "bidirectional"))
    )
    (net (code "32") (name "HUB_DM4") (class "Default")
      (node (ref "R82") (pin "1") (pinfunction "1_1") (pintype "passive"))
      (node (ref "U24") (pin "26") (pinfunction "DM4_26") (pintype "bidirectional"))
    )
    (net (code "33") (name "HUB_DM5") (class "Default")
      (node (ref "R80") (pin "1") (pinfunction "1_1") (pintype "passive"))
      (node (ref "U24") (pin "30") (pinfunction "DM5_30") (pintype "bidirectional"))
    )
    (net (code "34") (name "HUB_DM6") (class "Default")
      (node (ref "R84") (pin "1") (pinfunction "1_1") (pintype "passive"))
      (node (ref "U24") (pin "34") (pinfunction "DM6_34") (pintype "bidirectional"))
    )
    (net (code "35") (name "HUB_DM7") (class "Default")
      (node (ref "R86") (pin "1") (pinfunction "1_1") (pintype "passive"))
      (node (ref "U24") (pin "38") (pinfunction "DM7_38") (pintype "bidirectional"))
    )
    (net (code "36") (name "HUB_DP1") (class "Default")
      (node (ref "C7") (pin "1") (pinfunction "1_1") (pintype "bidirectional"))
      (node (ref "R8") (pin "2") (pinfunction "P$2_2") (pintype "passive"))
      (node (ref "U24") (pin "14") (pinfunction "DP1_14") (pintype "bidirectional"))
    )
    (net (code "37") (name "HUB_DP2") (class "Default")
      (node (ref "C5") (pin "1") (pinfunction "1_1") (pintype "bidirectional"))
      (node (ref "R6") (pin "2") (pinfunction "P$2_2") (pintype "passive"))
      (node (ref "U24") (pin "18") (pinfunction "DP2_18") (pintype "bidirectional"))
    )
    (net (code "38") (name "HUB_DP3") (class "Default")
      (node (ref "C9") (pin "1") (pinfunction "1_1") (pintype "bidirectional"))
      (node (ref "R10") (pin "2") (pinfunction "P$2_2") (pintype "passive"))
      (node (ref "U24") (pin "22") (pinfunction "DP3_22") (pintype "bidirectional"))
    )
    (net (code "39") (name "HUB_DP4") (class "Default")
      (node (ref "R81") (pin "1") (pinfunction "1_1") (pintype "passive"))
      (node (ref "U24") (pin "27") (pinfunction "DP4_27") (pintype "bidirectional"))
    )
    (net (code "40") (name "HUB_DP5") (class "Default")
      (node (ref "R79") (pin "1") (pinfunction "1_1") (pintype "passive"))
      (node (ref "U24") (pin "31") (pinfunction "DP5_31") (pintype "bidirectional"))
    )
    (net (code "41") (name "HUB_DP6") (class "Default")
      (node (ref "R83") (pin "1") (pinfunction "1_1") (pintype "passive"))
      (node (ref "U24") (pin "35") (pinfunction "DP6_35") (pintype "bidirectional"))
    )
    (net (code "42") (name "HUB_DP7") (class "Default")
      (node (ref "R85") (pin "1") (pinfunction "1_1") (pintype "passive"))
      (node (ref "U24") (pin "39") (pinfunction "DP7_39") (pintype "bidirectional"))
    )
    (net (code "43") (name "HUB_PORTDIS") (class "Default")
      (node (ref "TP30") (pin "TESTPOINT") (pinfunction "TESTPOINT_TESTPOINT") (pintype "bidirectional"))
      (node (ref "U24") (pin "42") (pinfunction "PORTDIS_42") (pintype "bidirectional"))
    )
    (net (code "44") (name "HUB_PORTPWR") (class "Default")
      (node (ref "TP29") (pin "TESTPOINT") (pinfunction "TESTPOINT_TESTPOINT") (pintype "bidirectional"))
      (node (ref "U24") (pin "41") (pinfunction "PORTPWR_41") (pintype "bidirectional"))
    )
    (net (code "45") (name "HUB_~{OVRCUR1}") (class "Default")
      (node (ref "R56") (pin "1") (pinfunction "1_1") (pintype "passive"))
      (node (ref "S2") (pin "5") (pinfunction "~{FLG}_5") (pintype "bidirectional"))
      (node (ref "TP33") (pin "TESTPOINT") (pinfunction "TESTPOINT_TESTPOINT") (pintype "bidirectional"))
      (node (ref "U24") (pin "12") (pinfunction "~{OVRCUR1}_12") (pintype "bidirectional"))
    )
    (net (code "46") (name "HUB_~{OVRCUR2}") (class "Default")
      (node (ref "R55") (pin "1") (pinfunction "1_1") (pintype "passive"))
      (node (ref "S1") (pin "5") (pinfunction "~{FLG}_5") (pintype "bidirectional"))
      (node (ref "TP35") (pin "TESTPOINT") (pinfunction "TESTPOINT_TESTPOINT") (pintype "bidirectional"))
      (node (ref "U24") (pin "16") (pinfunction "~{OVRCUR2}_16") (pintype "bidirectional"))
    )
    (net (code "47") (name "HUB_~{OVRCUR3}") (class "Default")
      (node (ref "R72") (pin "1") (pinfunction "1_1") (pintype "passive"))
      (node (ref "TP37") (pin "TESTPOINT") (pinfunction "TESTPOINT_TESTPOINT") (pintype "bidirectional"))
      (node (ref "U24") (pin "20") (pinfunction "~{OVRCUR3}_20") (pintype "bidirectional"))
    )
    (net (code "48") (name "HUB_~{OVRCUR4}") (class "Default")
      (node (ref "R67") (pin "1") (pinfunction "1_1") (pintype "passive"))
      (node (ref "U24") (pin "25") (pinfunction "~{OVRCUR4}_25") (pintype "bidirectional"))
    )
    (net (code "49") (name "HUB_~{OVRCUR5}") (class "Default")
      (node (ref "R66") (pin "1") (pinfunction "1_1") (pintype "passive"))
      (node (ref "U24") (pin "29") (pinfunction "~{OVRCUR5}_29") (pintype "bidirectional"))
    )
    (net (code "50") (name "HUB_~{OVRCUR6}") (class "Default")
      (node (ref "R68") (pin "1") (pinfunction "1_1") (pintype "passive"))
      (node (ref "U24") (pin "33") (pinfunction "~{OVRCUR6}_33") (pintype "bidirectional"))
    )
    (net (code "51") (name "HUB_~{OVRCUR7}") (class "Default")
      (node (ref "R69") (pin "1") (pinfunction "1_1") (pintype "passive"))
      (node (ref "U24") (pin "37") (pinfunction "~{OVRCUR7}_37") (pintype "bidirectional"))
    )
    (net (code "52") (name "HUB_~{PWRON1}") (class "Default")
      (node (ref "S10") (pin "1") (pinfunction "I1_1") (pintype "bidirectional"))
      (node (ref "TP32") (pin "TESTPOINT") (pinfunction "TESTPOINT_TESTPOINT") (pintype "bidirectional"))
      (node (ref "U24") (pin "11") (pinfunction "~{PWRON1}_11") (pintype "bidirectional"))
    )
    (net (code "53") (name "HUB_~{PWRON2}") (class "Default")
      (node (ref "S9") (pin "1") (pinfunction "I1_1") (pintype "bidirectional"))
      (node (ref "TP34") (pin "TESTPOINT") (pinfunction "TESTPOINT_TESTPOINT") (pintype "bidirectional"))
      (node (ref "U24") (pin "15") (pinfunction "~{PWRON2}_15") (pintype "bidirectional"))
    )
    (net (code "54") (name "HUB_~{PWRON3}") (class "Default")
      (node (ref "TP36") (pin "TESTPOINT") (pinfunction "TESTPOINT_TESTPOINT") (pintype "bidirectional"))
      (node (ref "U24") (pin "19") (pinfunction "~{PWRON3}_19") (pintype "bidirectional"))
    )
    (net (code "55") (name "HUB_~{PWRON4}") (class "Default")
      (node (ref "U24") (pin "23") (pinfunction "~{PWRON4}_23") (pintype "bidirectional"))
    )
    (net (code "56") (name "HUB_~{PWRON5}") (class "Default")
      (node (ref "U24") (pin "28") (pinfunction "~{PWRON5}_28") (pintype "bidirectional"))
    )
    (net (code "57") (name "HUB_~{PWRON6}") (class "Default")
      (node (ref "U24") (pin "32") (pinfunction "~{PWRON6}_32") (pintype "bidirectional"))
    )
    (net (code "58") (name "HUB_~{PWRON7}") (class "Default")
      (node (ref "U24") (pin "36") (pinfunction "~{PWRON7}_36") (pintype "bidirectional"))
    )
    (net (code "59") (name "JTAG_5V") (class "Default")
      (node (ref "J10") (pin "19") (pinfunction "19_19") (pintype "passive"))
    )
    (net (code "60") (name "JTAG_DBGRQ") (class "Default")
      (node (ref "J10") (pin "17") (pinfunction "17_17") (pintype "passive"))
    )
    (net (code "61") (name "JTAG_NTRST") (class "Default")
      (node (ref "J10") (pin "3") (pinfunction "3_3") (pintype "passive"))
    )
    (net (code "62") (name "JTAG_RTCK") (class "Default")
      (node (ref "J10") (pin "11") (pinfunction "11_11") (pintype "passive"))
    )
    (net (code "63") (name "JTAG_SWDCLK") (class "Default")
      (node (ref "J10") (pin "9") (pinfunction "9_9") (pintype "passive"))
      (node (ref "S14") (pin "4") (pinfunction "IN_4") (pintype "bidirectional"))
      (node (ref "S15") (pin "4") (pinfunction "IN_4") (pintype "bidirectional"))
      (node (ref "S16") (pin "4") (pinfunction "IN_4") (pintype "bidirectional"))
      (node (ref "S17") (pin "4") (pinfunction "IN_4") (pintype "bidirectional"))
      (node (ref "S18") (pin "4") (pinfunction "IN_4") (pintype "bidirectional"))
    )
    (net (code "64") (name "JTAG_SWDIO") (class "Default")
      (node (ref "J10") (pin "7") (pinfunction "7_7") (pintype "passive"))
      (node (ref "S14") (pin "1") (pinfunction "IN_1") (pintype "bidirectional"))
      (node (ref "S15") (pin "1") (pinfunction "IN_1") (pintype "bidirectional"))
      (node (ref "S16") (pin "1") (pinfunction "IN_1") (pintype "bidirectional"))
      (node (ref "S17") (pin "1") (pinfunction "IN_1") (pintype "bidirectional"))
      (node (ref "S18") (pin "1") (pinfunction "IN_1") (pintype "bidirectional"))
      (node (ref "S19") (pin "IN") (pinfunction "IN_IN") (pintype "bidirectional"))
    )
    (net (code "65") (name "JTAG_SWO{slash}TDO") (class "Default")
      (node (ref "J10") (pin "13") (pinfunction "13_13") (pintype "passive"))
    )
    (net (code "66") (name "JTAG_TDI") (class "Default")
      (node (ref "J10") (pin "5") (pinfunction "5_5") (pintype "passive"))
    )
    (net (code "67") (name "JTAG_VTREF") (class "Default")
      (node (ref "J10") (pin "1") (pinfunction "1_1") (pintype "passive"))
      (node (ref "S14") (pin "11") (pinfunction "IN_11") (pintype "bidirectional"))
      (node (ref "S15") (pin "11") (pinfunction "IN_11") (pintype "bidirectional"))
      (node (ref "S16") (pin "11") (pinfunction "IN_11") (pintype "bidirectional"))
      (node (ref "S17") (pin "11") (pinfunction "IN_11") (pintype "bidirectional"))
      (node (ref "S18") (pin "11") (pinfunction "IN_11") (pintype "bidirectional"))
    )
    (net (code "68") (name "JTAG_~{RESET}") (class "Default")
      (node (ref "J10") (pin "15") (pinfunction "15_15") (pintype "passive"))
      (node (ref "S14") (pin "8") (pinfunction "IN_8") (pintype "bidirectional"))
      (node (ref "S15") (pin "8") (pinfunction "IN_8") (pintype "bidirectional"))
      (node (ref "S16") (pin "8") (pinfunction "IN_8") (pintype "bidirectional"))
      (node (ref "S17") (pin "8") (pinfunction "IN_8") (pintype "bidirectional"))
      (node (ref "S18") (pin "8") (pinfunction "IN_8") (pintype "bidirectional"))
      (node (ref "S19") (pin "1") (pinfunction "A_1") (pintype "bidirectional"))
    )
    (net (code "69") (name "MOD0_5V") (class "Default")
      (node (ref "C18") (pin "1") (pinfunction "1_1") (pintype "bidirectional"))
      (node (ref "J3") (pin "2") (pinfunction "5V_2") (pintype "bidirectional"))
      (node (ref "S12") (pin "1") (pinfunction "VLOAD_1") (pintype "bidirectional"))
      (node (ref "TP57") (pin "TESTPOINT") (pinfunction "TESTPOINT_TESTPOINT") (pintype "bidirectional"))
    )
    (net (code "70") (name "MOD0_5V_METERED") (class "Default")
      (node (ref "C14") (pin "1") (pinfunction "1_1") (pintype "bidirectional"))
      (node (ref "C35") (pin "1") (pinfunction "1_1") (pintype "bidirectional"))
      (node (ref "C64") (pin "1") (pinfunction "1_1") (pintype "bidirectional"))
      (node (ref "R4") (pin "1") (pinfunction "1_1") (pintype "passive"))
      (node (ref "S1") (pin "2") (pinfunction "IN_2") (pintype "bidirectional"))
      (node (ref "S1") (pin "3") (pinfunction "IN_3") (pintype "bidirectional"))
      (node (ref "S12") (pin "3") (pinfunction "VSUPP_3") (pintype "bidirectional"))
      (node (ref "TP16") (pin "TESTPOINT") (pinfunction "TESTPOINT_TESTPOINT") (pintype "bidirectional"))
      (node (ref "U10") (pin "6") (pinfunction "SENSE-_6") (pintype "open_collector"))
    )
    (net (code "71") (name "MOD0_D+_HUB-SW") (class "Default")
      (node (ref "D8") (pin "4") (pinfunction "D_4") (pintype "bidirectional"))
      (node (ref "R6") (pin "1") (pinfunction "P$1_1") (pintype "passive"))
      (node (ref "R73") (pin "2") (pinfunction "2_2") (pintype "passive"))
      (node (ref "U21") (pin "3") (pinfunction "D+_3") (pintype "bidirectional"))
    )
    (net (code "72") (name "MOD0_D-_HUB-SW") (class "Default")
      (node (ref "D8") (pin "2") (pinfunction "C_2") (pintype "bidirectional"))
      (node (ref "R7") (pin "1") (pinfunction "P$1_1") (pintype "passive"))
      (node (ref "R74") (pin "2") (pinfunction "2_2") (pintype "passive"))
      (node (ref "U21") (pin "5") (pinfunction "D-_5") (pintype "bidirectional"))
    )
    (net (code "73") (name "MOD0_DBG_GPIO1") (class "Default")
      (node (ref "J3") (pin "16") (pinfunction "DBG_GPIO1_16") (pintype "bidirectional"))
      (node (ref "Q2") (pin "1") (pinfunction "G_1") (pintype "passive"))
      (node (ref "R97") (pin "2") (pinfunction "2_2") (pintype "passive"))
      (node (ref "TP21") (pin "TESTPOINT") (pinfunction "TESTPOINT_TESTPOINT") (pintype "bidirectional"))
    )
    (net (code "74") (name "MOD0_DBG_GPIO2") (class "Default")
      (node (ref "J3") (pin "19") (pinfunction "DBG_GPIO2_19") (pintype "bidirectional"))
      (node (ref "Q3") (pin "1") (pinfunction "G_1") (pintype "passive"))
      (node (ref "R98") (pin "2") (pinfunction "2_2") (pintype "passive"))
      (node (ref "TP38") (pin "TESTPOINT") (pinfunction "TESTPOINT_TESTPOINT") (pintype "bidirectional"))
    )
    (net (code "75") (name "MOD0_DBG_RX") (class "Default")
      (node (ref "J3") (pin "18") (pinfunction "DBG_RX_18") (pintype "bidirectional"))
      (node (ref "U2") (pin "30") (pinfunction "TXD_30") (pintype "output"))
    )
    (net (code "76") (name "MOD0_DBG_SWDCLK") (class "Default")
      (node (ref "J3") (pin "21") (pinfunction "DBG_SWDCLK_21") (pintype "bidirectional"))
      (node (ref "S14") (pin "3") (pinfunction "A_3") (pintype "bidirectional"))
    )
    (net (code "77") (name "MOD0_DBG_SWDIO") (class "Default")
      (node (ref "J3") (pin "22") (pinfunction "DBG_SWDIO_22") (pintype "bidirectional"))
      (node (ref "S14") (pin "2") (pinfunction "A_2") (pintype "bidirectional"))
    )
    (net (code "78") (name "MOD0_DBG_TX") (class "Default")
      (node (ref "J3") (pin "17") (pinfunction "DBG_TX_17") (pintype "bidirectional"))
      (node (ref "U2") (pin "2") (pinfunction "RXD_2") (pintype "input"))
    )
    (net (code "79") (name "MOD0_DBG_~{RESET}") (class "Default")
      (node (ref "J3") (pin "20") (pinfunction "DBG_~{RESET}_20") (pintype "bidirectional"))
      (node (ref "S14") (pin "9") (pinfunction "A_9") (pintype "bidirectional"))
      (node (ref "S4") (pin "2") (pinfunction "P$2_2") (pintype "passive"))
    )
    (net (code "80") (name "MOD0_IN") (class "Default")
      (node (ref "J3") (pin "10") (pinfunction "MOD_IN_10") (pintype "bidirectional"))
      (node (ref "TP48") (pin "TESTPOINT") (pinfunction "TESTPOINT_TESTPOINT") (pintype "bidirectional"))
      (node (ref "U17") (pin "7") (pinfunction "B1_7") (pintype "bidirectional"))
    )
    (net (code "81") (name "MOD0_ISO_I2C") (class "Default")
      (node (ref "D2") (pin "A") (pinfunction "ANODE_A") (pintype "bidirectional"))
      (node (ref "R92") (pin "2") (pinfunction "2_2") (pintype "passive"))
      (node (ref "TP1002") (pin "TESTPOINT") (pinfunction "TESTPOINT_TESTPOINT") (pintype "bidirectional"))
      (node (ref "U13") (pin "10") (pinfunction "P1_10") (pintype "bidirectional"))
      (node (ref "U6") (pin "5") (pinfunction "OE_5") (pintype "bidirectional"))
    )
    (net (code "82") (name "MOD0_ISO_POWER") (class "Default")
      (node (ref "D1") (pin "A") (pinfunction "ANODE_A") (pintype "bidirectional"))
      (node (ref "R91") (pin "2") (pinfunction "2_2") (pintype "passive"))
      (node (ref "S12") (pin "4") (pinfunction "EN_4") (pintype "bidirectional"))
      (node (ref "TP1001") (pin "TESTPOINT") (pinfunction "TESTPOINT_TESTPOINT") (pintype "bidirectional"))
      (node (ref "U13") (pin "9") (pinfunction "P0_9") (pintype "bidirectional"))
    )
    (net (code "83") (name "MOD0_ISO_USB") (class "Default")
      (node (ref "D3") (pin "A") (pinfunction "ANODE_A") (pintype "bidirectional"))
      (node (ref "R93") (pin "2") (pinfunction "2_2") (pintype "passive"))
      (node (ref "S9") (pin "6") (pinfunction "S_6") (pintype "bidirectional"))
      (node (ref "TP1003") (pin "TESTPOINT") (pinfunction "TESTPOINT_TESTPOINT") (pintype "bidirectional"))
      (node (ref "U13") (pin "11") (pinfunction "P2_11") (pintype "bidirectional"))
    )
    (net (code "84") (name "MOD0_OUT") (class "Default")
      (node (ref "J3") (pin "8") (pinfunction "MOD_OUT_8") (pintype "bidirectional"))
      (node (ref "TP49") (pin "TESTPOINT") (pinfunction "TESTPOINT_TESTPOINT") (pintype "bidirectional"))
      (node (ref "U19") (pin "7") (pinfunction "B1_7") (pintype "bidirectional"))
    )
    (net (code "85") (name "MOD0_PPS") (class "Default")
      (node (ref "J3") (pin "7") (pinfunction "PPS_7") (pintype "bidirectional"))
      (node (ref "TP46") (pin "TESTPOINT") (pinfunction "TESTPOINT_TESTPOINT") (pintype "bidirectional"))
      (node (ref "U17") (pin "6") (pinfunction "B2_6") (pintype "bidirectional"))
    )
    (net (code "86") (name "MOD0_SCL") (class "Default")
      (node (ref "J3") (pin "5") (pinfunction "SCL_5") (pintype "bidirectional"))
      (node (ref "R58") (pin "2") (pinfunction "2_2") (pintype "passive"))
      (node (ref "TP43") (pin "TESTPOINT") (pinfunction "TESTPOINT_TESTPOINT") (pintype "bidirectional"))
      (node (ref "U6") (pin "6") (pinfunction "B1_6") (pintype "bidirectional"))
    )
    (net (code "87") (name "MOD0_SDA") (class "Default")
      (node (ref "J3") (pin "6") (pinfunction "SDA_6") (pintype "bidirectional"))
      (node (ref "R57") (pin "2") (pinfunction "2_2") (pintype "passive"))
      (node (ref "TP42") (pin "TESTPOINT") (pinfunction "TESTPOINT_TESTPOINT") (pintype "bidirectional"))
      (node (ref "U6") (pin "7") (pinfunction "B0_7") (pintype "bidirectional"))
    )
    (net (code "88") (name "MOD0_USB+") (class "Default")
      (node (ref "J3") (pin "11") (pinfunction "USB_D+_11") (pintype "bidirectional"))
      (node (ref "U21") (pin "1") (pinfunction "D1+_1") (pintype "bidirectional"))
    )
    (net (code "89") (name "MOD0_USB-") (class "Default")
      (node (ref "J3") (pin "12") (pinfunction "USB_D-_12") (pintype "bidirectional"))
      (node (ref "U21") (pin "7") (pinfunction "D1-_7") (pintype "bidirectional"))
    )
    (net (code "90") (name "MOD0_USB_VBUS") (class "Default")
      (node (ref "C31") (pin "1") (pinfunction "1_1") (pintype "bidirectional"))
      (node (ref "C68") (pin "1") (pinfunction "1_1") (pintype "bidirectional"))
      (node (ref "J3") (pin "13") (pinfunction "USB_VBUS_13") (pintype "bidirectional"))
      (node (ref "S1") (pin "6") (pinfunction "OUT_6") (pintype "bidirectional"))
      (node (ref "S1") (pin "7") (pinfunction "OUT_7") (pintype "bidirectional"))
      (node (ref "TP20") (pin "TESTPOINT") (pinfunction "TESTPOINT_TESTPOINT") (pintype "bidirectional"))
    )
    (net (code "91") (name "MOD0_USB_~{EN}") (class "Default")
      (node (ref "S1") (pin "4") (pinfunction "~{EN}_4") (pintype "bidirectional"))
      (node (ref "S9") (pin "4") (pinfunction "Z_4") (pintype "bidirectional"))
      (node (ref "U21") (pin "8") (pinfunction "~{OE}_8") (pintype "bidirectional"))
    )
    (net (code "92") (name "MOD0_VCCIO") (class "Default")
      (node (ref "C24") (pin "1") (pinfunction "1_1") (pintype "bidirectional"))
      (node (ref "C26") (pin "1") (pinfunction "1_1") (pintype "bidirectional"))
      (node (ref "C39") (pin "1") (pinfunction "1_1") (pintype "bidirectional"))
      (node (ref "J3") (pin "4") (pinfunction "VCCIO_4") (pintype "bidirectional"))
      (node (ref "R57") (pin "1") (pinfunction "1_1") (pintype "passive"))
      (node (ref "R58") (pin "1") (pinfunction "1_1") (pintype "passive"))
      (node (ref "S14") (pin "10") (pinfunction "A_10") (pintype "bidirectional"))
      (node (ref "TP50") (pin "TESTPOINT") (pinfunction "TESTPOINT_TESTPOINT") (pintype "bidirectional"))
      (node (ref "U17") (pin "8") (pinfunction "VCC_B_8") (pintype "bidirectional"))
      (node (ref "U19") (pin "8") (pinfunction "VCC_B_8") (pintype "bidirectional"))
      (node (ref "U2") (pin "1") (pinfunction "VCCIO_1") (pintype "power_in"))
      (node (ref "U6") (pin "8") (pinfunction "VCC_B_8") (pintype "bidirectional"))
    )
    (net (code "93") (name "MOD1_5V") (class "Default")
      (node (ref "C19") (pin "1") (pinfunction "1_1") (pintype "bidirectional"))
      (node (ref "J2") (pin "2") (pinfunction "5V_2") (pintype "bidirectional"))
      (node (ref "S13") (pin "1") (pinfunction "VLOAD_1") (pintype "bidirectional"))
      (node (ref "TP58") (pin "TESTPOINT") (pinfunction "TESTPOINT_TESTPOINT") (pintype "bidirectional"))
    )
    (net (code "94") (name "MOD1_5V_METERED") (class "Default")
      (node (ref "C15") (pin "1") (pinfunction "1_1") (pintype "bidirectional"))
      (node (ref "C36") (pin "1") (pinfunction "1_1") (pintype "bidirectional"))
      (node (ref "C65") (pin "1") (pinfunction "1_1") (pintype "bidirectional"))
      (node (ref "R5") (pin "1") (pinfunction "1_1") (pintype "passive"))
      (node (ref "S13") (pin "3") (pinfunction "VSUPP_3") (pintype "bidirectional"))
      (node (ref "S2") (pin "2") (pinfunction "IN_2") (pintype "bidirectional"))
      (node (ref "S2") (pin "3") (pinfunction "IN_3") (pintype "bidirectional"))
      (node (ref "TP17") (pin "TESTPOINT") (pinfunction "TESTPOINT_TESTPOINT") (pintype "bidirectional"))
      (node (ref "U11") (pin "6") (pinfunction "SENSE-_6") (pintype "open_collector"))
    )
    (net (code "95") (name "MOD1_D+_HUB-SW") (class "Default")
      (node (ref "D8") (pin "8") (pinfunction "A_8") (pintype "bidirectional"))
      (node (ref "R75") (pin "2") (pinfunction "2_2") (pintype "passive"))
      (node (ref "R8") (pin "1") (pinfunction "P$1_1") (pintype "passive"))
      (node (ref "U22") (pin "3") (pinfunction "D+_3") (pintype "bidirectional"))
    )
    (net (code "96") (name "MOD1_D-_HUB-SW") (class "Default")
      (node (ref "D8") (pin "6") (pinfunction "B_6") (pintype "bidirectional"))
      (node (ref "R76") (pin "2") (pinfunction "2_2") (pintype "passive"))
      (node (ref "R9") (pin "1") (pinfunction "P$1_1") (pintype "passive"))
      (node (ref "U22") (pin "5") (pinfunction "D-_5") (pintype "bidirectional"))
    )
    (net (code "97") (name "MOD1_DBG_GPIO1") (class "Default")
      (node (ref "J2") (pin "16") (pinfunction "DBG_GPIO1_16") (pintype "bidirectional"))
      (node (ref "Q4") (pin "1") (pinfunction "G_1") (pintype "passive"))
      (node (ref "R99") (pin "2") (pinfunction "2_2") (pintype "passive"))
      (node (ref "TP39") (pin "TESTPOINT") (pinfunction "TESTPOINT_TESTPOINT") (pintype "bidirectional"))
    )
    (net (code "98") (name "MOD1_DBG_GPIO2") (class "Default")
      (node (ref "J2") (pin "19") (pinfunction "DBG_GPIO2_19") (pintype "bidirectional"))
      (node (ref "Q5") (pin "1") (pinfunction "G_1") (pintype "passive"))
      (node (ref "R100") (pin "2") (pinfunction "2_2") (pintype "passive"))
      (node (ref "TP40") (pin "TESTPOINT") (pinfunction "TESTPOINT_TESTPOINT") (pintype "bidirectional"))
    )
    (net (code "99") (name "MOD1_DBG_RX") (class "Default")
      (node (ref "J2") (pin "18") (pinfunction "DBG_RX_18") (pintype "bidirectional"))
      (node (ref "U3") (pin "30") (pinfunction "TXD_30") (pintype "output"))
    )
    (net (code "100") (name "MOD1_DBG_SWDCLK") (class "Default")
      (node (ref "J2") (pin "21") (pinfunction "DBG_SWDCLK_21") (pintype "bidirectional"))
      (node (ref "S15") (pin "3") (pinfunction "A_3") (pintype "bidirectional"))
    )
    (net (code "101") (name "MOD1_DBG_SWDIO") (class "Default")
      (node (ref "J2") (pin "22") (pinfunction "DBG_SWDIO_22") (pintype "bidirectional"))
      (node (ref "S15") (pin "2") (pinfunction "A_2") (pintype "bidirectional"))
    )
    (net (code "102") (name "MOD1_DBG_TX") (class "Default")
      (node (ref "J2") (pin "17") (pinfunction "DBG_TX_17") (pintype "bidirectional"))
      (node (ref "U3") (pin "2") (pinfunction "RXD_2") (pintype "input"))
    )
    (net (code "103") (name "MOD1_DBG_~{RESET}") (class "Default")
      (node (ref "J2") (pin "20") (pinfunction "DBG_~{RESET}_20") (pintype "bidirectional"))
      (node (ref "S15") (pin "9") (pinfunction "A_9") (pintype "bidirectional"))
      (node (ref "S5") (pin "2") (pinfunction "P$2_2") (pintype "passive"))
    )
    (net (code "104") (name "MOD1_IN") (class "Default")
      (node (ref "J2") (pin "10") (pinfunction "MOD_IN_10") (pintype "bidirectional"))
      (node (ref "TP52") (pin "TESTPOINT") (pinfunction "TESTPOINT_TESTPOINT") (pintype "bidirectional"))
      (node (ref "U18") (pin "7") (pinfunction "B1_7") (pintype "bidirectional"))
    )
    (net (code "105") (name "MOD1_ISO_I2C") (class "Default")
      (node (ref "D5") (pin "A") (pinfunction "ANODE_A") (pintype "bidirectional"))
      (node (ref "R95") (pin "2") (pinfunction "2_2") (pintype "passive"))
      (node (ref "TP1005") (pin "TESTPOINT") (pinfunction "TESTPOINT_TESTPOINT") (pintype "bidirectional"))
      (node (ref "U14") (pin "10") (pinfunction "P1_10") (pintype "bidirectional"))
      (node (ref "U7") (pin "5") (pinfunction "OE_5") (pintype "bidirectional"))
    )
    (net (code "106") (name "MOD1_ISO_POWER") (class "Default")
      (node (ref "D4") (pin "A") (pinfunction "ANODE_A") (pintype "bidirectional"))
      (node (ref "R94") (pin "2") (pinfunction "2_2") (pintype "passive"))
      (node (ref "S13") (pin "4") (pinfunction "EN_4") (pintype "bidirectional"))
      (node (ref "TP1004") (pin "TESTPOINT") (pinfunction "TESTPOINT_TESTPOINT") (pintype "bidirectional"))
      (node (ref "U14") (pin "9") (pinfunction "P0_9") (pintype "bidirectional"))
    )
    (net (code "107") (name "MOD1_ISO_USB") (class "Default")
      (node (ref "D6") (pin "A") (pinfunction "ANODE_A") (pintype "bidirectional"))
      (node (ref "R96") (pin "2") (pinfunction "2_2") (pintype "passive"))
      (node (ref "S10") (pin "6") (pinfunction "S_6") (pintype "bidirectional"))
      (node (ref "TP1006") (pin "TESTPOINT") (pinfunction "TESTPOINT_TESTPOINT") (pintype "bidirectional"))
      (node (ref "U14") (pin "11") (pinfunction "P2_11") (pintype "bidirectional"))
    )
    (net (code "108") (name "MOD1_OUT") (class "Default")
      (node (ref "J2") (pin "8") (pinfunction "MOD_OUT_8") (pintype "bidirectional"))
      (node (ref "TP53") (pin "TESTPOINT") (pinfunction "TESTPOINT_TESTPOINT") (pintype "bidirectional"))
      (node (ref "U20") (pin "7") (pinfunction "B1_7") (pintype "bidirectional"))
    )
    (net (code "109") (name "MOD1_PPS") (class "Default")
      (node (ref "J2") (pin "7") (pinfunction "PPS_7") (pintype "bidirectional"))
      (node (ref "TP47") (pin "TESTPOINT") (pinfunction "TESTPOINT_TESTPOINT") (pintype "bidirectional"))
      (node (ref "U18") (pin "6") (pinfunction "B2_6") (pintype "bidirectional"))
    )
    (net (code "110") (name "MOD1_SCL") (class "Default")
      (node (ref "J2") (pin "5") (pinfunction "SCL_5") (pintype "bidirectional"))
      (node (ref "R60") (pin "2") (pinfunction "2_2") (pintype "passive"))
      (node (ref "TP45") (pin "TESTPOINT") (pinfunction "TESTPOINT_TESTPOINT") (pintype "bidirectional"))
      (node (ref "U7") (pin "6") (pinfunction "B1_6") (pintype "bidirectional"))
    )
    (net (code "111") (name "MOD1_SDA") (class "Default")
      (node (ref "J2") (pin "6") (pinfunction "SDA_6") (pintype "bidirectional"))
      (node (ref "R59") (pin "2") (pinfunction "2_2") (pintype "passive"))
      (node (ref "TP44") (pin "TESTPOINT") (pinfunction "TESTPOINT_TESTPOINT") (pintype "bidirectional"))
      (node (ref "U7") (pin "7") (pinfunction "B0_7") (pintype "bidirectional"))
    )
    (net (code "112") (name "MOD1_USB+") (class "Default")
      (node (ref "J2") (pin "11") (pinfunction "USB_D+_11") (pintype "bidirectional"))
      (node (ref "U22") (pin "1") (pinfunction "D1+_1") (pintype "bidirectional"))
    )
    (net (code "113") (name "MOD1_USB-") (class "Default")
      (node (ref "J2") (pin "12") (pinfunction "USB_D-_12") (pintype "bidirectional"))
      (node (ref "U22") (pin "7") (pinfunction "D1-_7") (pintype "bidirectional"))
    )
    (net (code "114") (name "MOD1_USB_VBUS") (class "Default")
      (node (ref "C32") (pin "1") (pinfunction "1_1") (pintype "bidirectional"))
      (node (ref "C69") (pin "1") (pinfunction "1_1") (pintype "bidirectional"))
      (node (ref "J2") (pin "13") (pinfunction "USB_VBUS_13") (pintype "bidirectional"))
      (node (ref "S2") (pin "6") (pinfunction "OUT_6") (pintype "bidirectional"))
      (node (ref "S2") (pin "7") (pinfunction "OUT_7") (pintype "bidirectional"))
      (node (ref "TP41") (pin "TESTPOINT") (pinfunction "TESTPOINT_TESTPOINT") (pintype "bidirectional"))
    )
    (net (code "115") (name "MOD1_USB_~{EN}") (class "Default")
      (node (ref "S10") (pin "4") (pinfunction "Z_4") (pintype "bidirectional"))
      (node (ref "S2") (pin "4") (pinfunction "~{EN}_4") (pintype "bidirectional"))
      (node (ref "U22") (pin "8") (pinfunction "~{OE}_8") (pintype "bidirectional"))
    )
    (net (code "116") (name "MOD1_VCCIO") (class "Default")
      (node (ref "C25") (pin "1") (pinfunction "1_1") (pintype "bidirectional"))
      (node (ref "C27") (pin "1") (pinfunction "1_1") (pintype "bidirectional"))
      (node (ref "C40") (pin "1") (pinfunction "1_1") (pintype "bidirectional"))
      (node (ref "J2") (pin "4") (pinfunction "VCCIO_4") (pintype "bidirectional"))
      (node (ref "R59") (pin "1") (pinfunction "1_1") (pintype "passive"))
      (node (ref "R60") (pin "1") (pinfunction "1_1") (pintype "passive"))
      (node (ref "S15") (pin "10") (pinfunction "A_10") (pintype "bidirectional"))
      (node (ref "TP55") (pin "TESTPOINT") (pinfunction "TESTPOINT_TESTPOINT") (pintype "bidirectional"))
      (node (ref "U18") (pin "8") (pinfunction "VCC_B_8") (pintype "bidirectional"))
      (node (ref "U20") (pin "8") (pinfunction "VCC_B_8") (pintype "bidirectional"))
      (node (ref "U3") (pin "1") (pinfunction "VCCIO_1") (pintype "power_in"))
      (node (ref "U7") (pin "8") (pinfunction "VCC_B_8") (pintype "bidirectional"))
    )
    (net (code "117") (name "MOD2_USB+") (class "Default")
      (node (ref "D7") (pin "8") (pinfunction "A_8") (pintype "bidirectional"))
      (node (ref "R10") (pin "1") (pinfunction "P$1_1") (pintype "passive"))
      (node (ref "R77") (pin "2") (pinfunction "2_2") (pintype "passive"))
      (node (ref "U16") (pin "47") (pinfunction "PA26_47") (pintype "bidirectional"))
    )
    (net (code "118") (name "MOD2_USB-") (class "Default")
      (node (ref "D7") (pin "6") (pinfunction "B_6") (pintype "bidirectional"))
      (node (ref "R11") (pin "1") (pinfunction "P$1_1") (pintype "passive"))
      (node (ref "R78") (pin "2") (pinfunction "2_2") (pintype "passive"))
      (node (ref "U16") (pin "46") (pinfunction "PA25_46") (pintype "bidirectional"))
    )
    (net (code "119") (name "MOD_SCL") (class "Default")
      (node (ref "J1") (pin "24") (pinfunction "MODULES_SCL_24") (pintype "bidirectional"))
      (node (ref "R65") (pin "1") (pinfunction "1_1") (pintype "passive"))
      (node (ref "TP6") (pin "TESTPOINT") (pinfunction "TESTPOINT_TESTPOINT") (pintype "bidirectional"))
      (node (ref "U16") (pin "44") (pinfunction "PA24_44") (pintype "bidirectional"))
      (node (ref "U6") (pin "3") (pinfunction "A1_3") (pintype "bidirectional"))
      (node (ref "U7") (pin "3") (pinfunction "A1_3") (pintype "bidirectional"))
    )
    (net (code "120") (name "MOD_SDA") (class "Default")
      (node (ref "J1") (pin "23") (pinfunction "MODULES_SDA_23") (pintype "bidirectional"))
      (node (ref "R64") (pin "1") (pinfunction "1_1") (pintype "passive"))
      (node (ref "TP5") (pin "TESTPOINT") (pinfunction "TESTPOINT_TESTPOINT") (pintype "bidirectional"))
      (node (ref "U16") (pin "43") (pinfunction "PA23_43") (pintype "bidirectional"))
      (node (ref "U6") (pin "2") (pinfunction "A0_2") (pintype "bidirectional"))
      (node (ref "U7") (pin "2") (pinfunction "A0_2") (pintype "bidirectional"))
    )
    (net (code "121") (name "Net-(C4-Pad2)") (class "Default")
      (node (ref "C4") (pin "2") (pinfunction "2_2") (pintype "bidirectional"))
      (node (ref "R41") (pin "1") (pinfunction "1_1") (pintype "passive"))
      (node (ref "Y1") (pin "1") (pinfunction "1_1") (pintype "bidirectional"))
    )
    (net (code "122") (name "Net-(D1-CATHODE)") (class "Default")
      (node (ref "D1") (pin "C") (pinfunction "CATHODE_C") (pintype "bidirectional"))
      (node (ref "R16") (pin "2") (pinfunction "2_2") (pintype "passive"))
    )
    (net (code "123") (name "Net-(D2-CATHODE)") (class "Default")
      (node (ref "D2") (pin "C") (pinfunction "CATHODE_C") (pintype "bidirectional"))
      (node (ref "R18") (pin "2") (pinfunction "2_2") (pintype "passive"))
    )
    (net (code "124") (name "Net-(D3-CATHODE)") (class "Default")
      (node (ref "D3") (pin "C") (pinfunction "CATHODE_C") (pintype "bidirectional"))
      (node (ref "R17") (pin "2") (pinfunction "2_2") (pintype "passive"))
    )
    (net (code "125") (name "Net-(D4-CATHODE)") (class "Default")
      (node (ref "D4") (pin "C") (pinfunction "CATHODE_C") (pintype "bidirectional"))
      (node (ref "R19") (pin "2") (pinfunction "2_2") (pintype "passive"))
    )
    (net (code "126") (name "Net-(D5-CATHODE)") (class "Default")
      (node (ref "D5") (pin "C") (pinfunction "CATHODE_C") (pintype "bidirectional"))
      (node (ref "R20") (pin "2") (pinfunction "2_2") (pintype "passive"))
    )
    (net (code "127") (name "Net-(D6-CATHODE)") (class "Default")
      (node (ref "D6") (pin "C") (pinfunction "CATHODE_C") (pintype "bidirectional"))
      (node (ref "R21") (pin "2") (pinfunction "2_2") (pintype "passive"))
    )
    (net (code "128") (name "Net-(D9-CATHODE)") (class "Default")
      (node (ref "D9") (pin "C") (pinfunction "CATHODE_C") (pintype "bidirectional"))
      (node (ref "R105") (pin "2") (pinfunction "2_2") (pintype "passive"))
    )
    (net (code "129") (name "Net-(FB1-P$1)") (class "Default")
      (node (ref "C47") (pin "1") (pinfunction "1_1") (pintype "bidirectional"))
      (node (ref "FB1") (pin "1") (pinfunction "P$1_1") (pintype "bidirectional"))
      (node (ref "U1") (pin "19") (pinfunction "VCC_19") (pintype "power_in"))
    )
    (net (code "130") (name "Net-(FB1-P$2)") (class "Default")
      (node (ref "C46") (pin "1") (pinfunction "1_1") (pintype "bidirectional"))
      (node (ref "FB1") (pin "2") (pinfunction "P$2_2") (pintype "bidirectional"))
      (node (ref "J4") (pin "1") (pinfunction "+5V_1") (pintype "bidirectional"))
    )
    (net (code "131") (name "Net-(FB2-P$1)") (class "Default")
      (node (ref "C50") (pin "1") (pinfunction "1_1") (pintype "bidirectional"))
      (node (ref "FB2") (pin "1") (pinfunction "P$1_1") (pintype "bidirectional"))
      (node (ref "J5") (pin "1") (pinfunction "+5V_1") (pintype "bidirectional"))
    )
    (net (code "132") (name "Net-(FB2-P$2)") (class "Default")
      (node (ref "C51") (pin "1") (pinfunction "1_1") (pintype "bidirectional"))
      (node (ref "FB2") (pin "2") (pinfunction "P$2_2") (pintype "bidirectional"))
      (node (ref "U2") (pin "19") (pinfunction "VCC_19") (pintype "power_in"))
    )
    (net (code "133") (name "Net-(FB3-P$1)") (class "Default")
      (node (ref "C53") (pin "1") (pinfunction "1_1") (pintype "bidirectional"))
      (node (ref "FB3") (pin "1") (pinfunction "P$1_1") (pintype "bidirectional"))
      (node (ref "J6") (pin "1") (pinfunction "+5V_1") (pintype "bidirectional"))
    )
    (net (code "134") (name "Net-(FB3-P$2)") (class "Default")
      (node (ref "C54") (pin "1") (pinfunction "1_1") (pintype "bidirectional"))
      (node (ref "FB3") (pin "2") (pinfunction "P$2_2") (pintype "bidirectional"))
      (node (ref "U3") (pin "19") (pinfunction "VCC_19") (pintype "power_in"))
    )
    (net (code "135") (name "Net-(FB4-P$1)") (class "Default")
      (node (ref "C56") (pin "1") (pinfunction "1_1") (pintype "bidirectional"))
      (node (ref "FB4") (pin "1") (pinfunction "P$1_1") (pintype "bidirectional"))
      (node (ref "J7") (pin "1") (pinfunction "+5V_1") (pintype "bidirectional"))
    )
    (net (code "136") (name "Net-(FB4-P$2)") (class "Default")
      (node (ref "C57") (pin "1") (pinfunction "1_1") (pintype "bidirectional"))
      (node (ref "FB4") (pin "2") (pinfunction "P$2_2") (pintype "bidirectional"))
      (node (ref "U4") (pin "19") (pinfunction "VCC_19") (pintype "power_in"))
    )
    (net (code "137") (name "Net-(FB5-P$1)") (class "Default")
      (node (ref "C59") (pin "1") (pinfunction "1_1") (pintype "bidirectional"))
      (node (ref "FB5") (pin "1") (pinfunction "P$1_1") (pintype "bidirectional"))
      (node (ref "J8") (pin "1") (pinfunction "+5V_1") (pintype "bidirectional"))
    )
    (net (code "138") (name "Net-(FB5-P$2)") (class "Default")
      (node (ref "C60") (pin "1") (pinfunction "1_1") (pintype "bidirectional"))
      (node (ref "FB5") (pin "2") (pinfunction "P$2_2") (pintype "bidirectional"))
      (node (ref "U5") (pin "19") (pinfunction "VCC_19") (pintype "power_in"))
    )
    (net (code "139") (name "Net-(FB6-P$1)") (class "Default")
      (node (ref "C41") (pin "1") (pinfunction "1_1") (pintype "bidirectional"))
      (node (ref "FB6") (pin "1") (pinfunction "P$1_1") (pintype "bidirectional"))
      (node (ref "U16") (pin "19") (pinfunction "VDDANA_19") (pintype "power_in"))
    )
    (net (code "140") (name "Net-(J4-D+)") (class "Default")
      (node (ref "J4") (pin "3") (pinfunction "D+_3") (pintype "bidirectional"))
      (node (ref "U1") (pin "14") (pinfunction "USBDP_14") (pintype "bidirectional"))
    )
    (net (code "141") (name "Net-(J4-D-)") (class "Default")
      (node (ref "J4") (pin "2") (pinfunction "D-_2") (pintype "bidirectional"))
      (node (ref "U1") (pin "15") (pinfunction "USBDM_15") (pintype "bidirectional"))
    )
    (net (code "142") (name "Net-(J5-D+)") (class "Default")
      (node (ref "J5") (pin "3") (pinfunction "D+_3") (pintype "bidirectional"))
      (node (ref "U2") (pin "14") (pinfunction "USBDP_14") (pintype "bidirectional"))
    )
    (net (code "143") (name "Net-(J5-D-)") (class "Default")
      (node (ref "J5") (pin "2") (pinfunction "D-_2") (pintype "bidirectional"))
      (node (ref "U2") (pin "15") (pinfunction "USBDM_15") (pintype "bidirectional"))
    )
    (net (code "144") (name "Net-(J6-D+)") (class "Default")
      (node (ref "J6") (pin "3") (pinfunction "D+_3") (pintype "bidirectional"))
      (node (ref "U3") (pin "14") (pinfunction "USBDP_14") (pintype "bidirectional"))
    )
    (net (code "145") (name "Net-(J6-D-)") (class "Default")
      (node (ref "J6") (pin "2") (pinfunction "D-_2") (pintype "bidirectional"))
      (node (ref "U3") (pin "15") (pinfunction "USBDM_15") (pintype "bidirectional"))
    )
    (net (code "146") (name "Net-(J7-D+)") (class "Default")
      (node (ref "J7") (pin "3") (pinfunction "D+_3") (pintype "bidirectional"))
      (node (ref "U4") (pin "14") (pinfunction "USBDP_14") (pintype "bidirectional"))
    )
    (net (code "147") (name "Net-(J7-D-)") (class "Default")
      (node (ref "J7") (pin "2") (pinfunction "D-_2") (pintype "bidirectional"))
      (node (ref "U4") (pin "15") (pinfunction "USBDM_15") (pintype "bidirectional"))
    )
    (net (code "148") (name "Net-(J8-D+)") (class "Default")
      (node (ref "J8") (pin "3") (pinfunction "D+_3") (pintype "bidirectional"))
      (node (ref "U5") (pin "14") (pinfunction "USBDP_14") (pintype "bidirectional"))
    )
    (net (code "149") (name "Net-(J8-D-)") (class "Default")
      (node (ref "J8") (pin "2") (pinfunction "D-_2") (pintype "bidirectional"))
      (node (ref "U5") (pin "15") (pinfunction "USBDM_15") (pintype "bidirectional"))
    )
    (net (code "150") (name "Net-(J9-+5V)") (class "Default")
      (node (ref "J9") (pin "1") (pinfunction "+5V_1") (pintype "bidirectional"))
      (node (ref "Q1") (pin "G2") (pinfunction "G2_G2") (pintype "input"))
      (node (ref "R90") (pin "2") (pinfunction "2_2") (pintype "passive"))
    )
    (net (code "151") (name "Net-(J9-D+)") (class "Default")
      (node (ref "J9") (pin "3") (pinfunction "D+_3") (pintype "bidirectional"))
      (node (ref "U23") (pin "1") (pinfunction "D1+_1") (pintype "bidirectional"))
    )
    (net (code "152") (name "Net-(J9-D-)") (class "Default")
      (node (ref "J9") (pin "2") (pinfunction "D-_2") (pintype "bidirectional"))
      (node (ref "U23") (pin "7") (pinfunction "D1-_7") (pintype "bidirectional"))
    )
    (net (code "153") (name "Net-(J11-VCC)") (class "Default")
      (node (ref "J11") (pin "1") (pinfunction "VCC_1") (pintype "bidirectional"))
      (node (ref "Q10") (pin "3") (pinfunction "D_3") (pintype "passive"))
      (node (ref "R106") (pin "2") (pinfunction "2_2") (pintype "passive"))
      (node (ref "U25") (pin "1") (pinfunction "IN_1") (pintype "bidirectional"))
    )
    (net (code "154") (name "Net-(L1-1)") (class "Default")
      (node (ref "C45") (pin "1") (pinfunction "1_1") (pintype "bidirectional"))
      (node (ref "C67") (pin "1") (pinfunction "1_1") (pintype "bidirectional"))
      (node (ref "L1") (pin "P$1") (pinfunction "1_P$1") (pintype "bidirectional"))
      (node (ref "U16") (pin "7") (pinfunction "VDDOUT_7") (pintype "power_in"))
    )
    (net (code "155") (name "Net-(L1-2)") (class "Default")
      (node (ref "L1") (pin "P$2") (pinfunction "2_P$2") (pintype "bidirectional"))
      (node (ref "U16") (pin "5") (pinfunction "VDDCORE_5") (pintype "power_in"))
    )
    (net (code "156") (name "Net-(LED1-CATHODE)") (class "Default")
      (node (ref "LED1") (pin "C") (pinfunction "CATHODE_C") (pintype "bidirectional"))
      (node (ref "R22") (pin "2") (pinfunction "2_2") (pintype "passive"))
    )
    (net (code "157") (name "Net-(LED2-CATHODE)") (class "Default")
      (node (ref "LED2") (pin "C") (pinfunction "CATHODE_C") (pintype "bidirectional"))
      (node (ref "R23") (pin "2") (pinfunction "2_2") (pintype "passive"))
    )
    (net (code "158") (name "Net-(LED3-CATHODE)") (class "Default")
      (node (ref "LED3") (pin "C") (pinfunction "CATHODE_C") (pintype "bidirectional"))
      (node (ref "R24") (pin "2") (pinfunction "2_2") (pintype "passive"))
    )
    (net (code "159") (name "Net-(LED4-CATHODE)") (class "Default")
      (node (ref "LED4") (pin "C") (pinfunction "CATHODE_C") (pintype "bidirectional"))
      (node (ref "R25") (pin "2") (pinfunction "2_2") (pintype "passive"))
    )
    (net (code "160") (name "Net-(LED5-ANODE)") (class "Default")
      (node (ref "LED5") (pin "A") (pinfunction "ANODE_A") (pintype "bidirectional"))
      (node (ref "R31") (pin "1") (pinfunction "1_1") (pintype "passive"))
    )
    (net (code "161") (name "Net-(LED6-ANODE)") (class "Default")
      (node (ref "LED6") (pin "A") (pinfunction "ANODE_A") (pintype "bidirectional"))
      (node (ref "R32") (pin "1") (pinfunction "1_1") (pintype "passive"))
    )
    (net (code "162") (name "Net-(LED7-ANODE)") (class "Default")
      (node (ref "LED7") (pin "A") (pinfunction "ANODE_A") (pintype "bidirectional"))
      (node (ref "R33") (pin "1") (pinfunction "1_1") (pintype "passive"))
    )
    (net (code "163") (name "Net-(LED8-ANODE)") (class "Default")
      (node (ref "LED8") (pin "A") (pinfunction "ANODE_A") (pintype "bidirectional"))
      (node (ref "R34") (pin "1") (pinfunction "1_1") (pintype "passive"))
    )
    (net (code "164") (name "Net-(LED9-ANODE)") (class "Default")
      (node (ref "LED9") (pin "A") (pinfunction "ANODE_A") (pintype "bidirectional"))
      (node (ref "R35") (pin "1") (pinfunction "1_1") (pintype "passive"))
    )
    (net (code "165") (name "Net-(LED10-CATHODE)") (class "Default")
      (node (ref "LED10") (pin "C") (pinfunction "CATHODE_C") (pintype "bidirectional"))
      (node (ref "R36") (pin "2") (pinfunction "2_2") (pintype "passive"))
    )
    (net (code "166") (name "Net-(LED11-CATHODE)") (class "Default")
      (node (ref "LED11") (pin "C") (pinfunction "CATHODE_C") (pintype "bidirectional"))
      (node (ref "R37") (pin "2") (pinfunction "2_2") (pintype "passive"))
    )
    (net (code "167") (name "Net-(LED12-CATHODE)") (class "Default")
      (node (ref "LED12") (pin "C") (pinfunction "CATHODE_C") (pintype "bidirectional"))
      (node (ref "R38") (pin "2") (pinfunction "2_2") (pintype "passive"))
    )
    (net (code "168") (name "Net-(LED13-CATHODE)") (class "Default")
      (node (ref "LED13") (pin "C") (pinfunction "CATHODE_C") (pintype "bidirectional"))
      (node (ref "R39") (pin "2") (pinfunction "2_2") (pintype "passive"))
    )
    (net (code "169") (name "Net-(Q2-D)") (class "Default")
      (node (ref "Q2") (pin "3") (pinfunction "D_3") (pintype "passive"))
      (node (ref "R22") (pin "1") (pinfunction "1_1") (pintype "passive"))
    )
    (net (code "170") (name "Net-(Q3-D)") (class "Default")
      (node (ref "Q3") (pin "3") (pinfunction "D_3") (pintype "passive"))
      (node (ref "R23") (pin "1") (pinfunction "1_1") (pintype "passive"))
    )
    (net (code "171") (name "Net-(Q4-D)") (class "Default")
      (node (ref "Q4") (pin "3") (pinfunction "D_3") (pintype "passive"))
      (node (ref "R24") (pin "1") (pinfunction "1_1") (pintype "passive"))
    )
    (net (code "172") (name "Net-(Q5-D)") (class "Default")
      (node (ref "Q5") (pin "3") (pinfunction "D_3") (pintype "passive"))
      (node (ref "R25") (pin "1") (pinfunction "1_1") (pintype "passive"))
    )
    (net (code "173") (name "Net-(Q6-D)") (class "Default")
      (node (ref "Q6") (pin "3") (pinfunction "D_3") (pintype "passive"))
      (node (ref "R36") (pin "1") (pinfunction "1_1") (pintype "passive"))
    )
    (net (code "174") (name "Net-(Q7-D)") (class "Default")
      (node (ref "Q7") (pin "3") (pinfunction "D_3") (pintype "passive"))
      (node (ref "R37") (pin "1") (pinfunction "1_1") (pintype "passive"))
    )
    (net (code "175") (name "Net-(Q8-D)") (class "Default")
      (node (ref "Q8") (pin "3") (pinfunction "D_3") (pintype "passive"))
      (node (ref "R38") (pin "1") (pinfunction "1_1") (pintype "passive"))
    )
    (net (code "176") (name "Net-(Q9-D)") (class "Default")
      (node (ref "Q9") (pin "3") (pinfunction "D_3") (pintype "passive"))
      (node (ref "R39") (pin "1") (pinfunction "1_1") (pintype "passive"))
    )
    (net (code "177") (name "Net-(Q10-G)") (class "Default")
      (node (ref "Q10") (pin "1") (pinfunction "G_1") (pintype "passive"))
      (node (ref "U25") (pin "8") (pinfunction "GATE_8") (pintype "bidirectional"))
    )
    (net (code "178") (name "Net-(U1-3V3OUT)") (class "Default")
      (node (ref "C48") (pin "1") (pinfunction "1_1") (pintype "bidirectional"))
      (node (ref "U1") (pin "1") (pinfunction "VCCIO_1") (pintype "power_in"))
      (node (ref "U1") (pin "16") (pinfunction "3V3OUT_16") (pintype "output"))
    )
    (net (code "179") (name "Net-(U2-3V3OUT)") (class "Default")
      (node (ref "C49") (pin "1") (pinfunction "1_1") (pintype "bidirectional"))
      (node (ref "U2") (pin "16") (pinfunction "3V3OUT_16") (pintype "output"))
    )
    (net (code "180") (name "Net-(U3-3V3OUT)") (class "Default")
      (node (ref "C52") (pin "1") (pinfunction "1_1") (pintype "bidirectional"))
      (node (ref "U3") (pin "16") (pinfunction "3V3OUT_16") (pintype "output"))
    )
    (net (code "181") (name "Net-(U4-3V3OUT)") (class "Default")
      (node (ref "C55") (pin "1") (pinfunction "1_1") (pintype "bidirectional"))
      (node (ref "U4") (pin "1") (pinfunction "VCCIO_1") (pintype "power_in"))
      (node (ref "U4") (pin "16") (pinfunction "3V3OUT_16") (pintype "output"))
    )
    (net (code "182") (name "Net-(U5-3V3OUT)") (class "Default")
      (node (ref "C58") (pin "1") (pinfunction "1_1") (pintype "bidirectional"))
      (node (ref "U5") (pin "1") (pinfunction "VCCIO_1") (pintype "power_in"))
      (node (ref "U5") (pin "16") (pinfunction "3V3OUT_16") (pintype "output"))
    )
    (net (code "183") (name "Net-(U10-SCL)") (class "Default")
      (node (ref "R50") (pin "1") (pinfunction "1_1") (pintype "passive"))
      (node (ref "U10") (pin "3") (pinfunction "SCL_3") (pintype "open_collector"))
      (node (ref "U15") (pin "13") (pinfunction "SC2_13") (pintype "bidirectional"))
    )
    (net (code "184") (name "Net-(U10-SDA)") (class "Default")
      (node (ref "R49") (pin "1") (pinfunction "1_1") (pintype "passive"))
      (node (ref "U10") (pin "4") (pinfunction "SDA_4") (pintype "open_collector"))
      (node (ref "U15") (pin "12") (pinfunction "SD2_12") (pintype "bidirectional"))
    )
    (net (code "185") (name "Net-(U10-~{ALERT})") (class "Default")
      (node (ref "R51") (pin "1") (pinfunction "1_1") (pintype "passive"))
      (node (ref "U10") (pin "5") (pinfunction "~{ALERT}_5") (pintype "open_collector"))
      (node (ref "U15") (pin "11") (pinfunction "~{INT2}_11") (pintype "bidirectional"))
    )
    (net (code "186") (name "Net-(U11-SCL)") (class "Default")
      (node (ref "R53") (pin "1") (pinfunction "1_1") (pintype "passive"))
      (node (ref "U11") (pin "3") (pinfunction "SCL_3") (pintype "open_collector"))
      (node (ref "U15") (pin "16") (pinfunction "SC3_16") (pintype "bidirectional"))
    )
    (net (code "187") (name "Net-(U11-SDA)") (class "Default")
      (node (ref "R52") (pin "1") (pinfunction "1_1") (pintype "passive"))
      (node (ref "U11") (pin "4") (pinfunction "SDA_4") (pintype "open_collector"))
      (node (ref "U15") (pin "15") (pinfunction "SD3_15") (pintype "bidirectional"))
    )
    (net (code "188") (name "Net-(U11-~{ALERT})") (class "Default")
      (node (ref "R54") (pin "1") (pinfunction "1_1") (pintype "passive"))
      (node (ref "U11") (pin "5") (pinfunction "~{ALERT}_5") (pintype "open_collector"))
      (node (ref "U15") (pin "14") (pinfunction "~{INT3}_14") (pintype "bidirectional"))
    )
    (net (code "189") (name "Net-(U12-BP)") (class "Default")
      (node (ref "C11") (pin "1") (pinfunction "1_1") (pintype "bidirectional"))
      (node (ref "U12") (pin "4") (pinfunction "BP_4") (pintype "bidirectional"))
    )
    (net (code "190") (name "Net-(U12-~{SHDN})") (class "Default")
      (node (ref "R70") (pin "1") (pinfunction "1_1") (pintype "passive"))
      (node (ref "U12") (pin "3") (pinfunction "~{SHDN}_3") (pintype "bidirectional"))
    )
    (net (code "191") (name "Net-(U15-SC0)") (class "Default")
      (node (ref "R44") (pin "1") (pinfunction "1_1") (pintype "passive"))
      (node (ref "U15") (pin "6") (pinfunction "SC0_6") (pintype "bidirectional"))
      (node (ref "U8") (pin "3") (pinfunction "SCL_3") (pintype "open_collector"))
    )
    (net (code "192") (name "Net-(U15-SC1)") (class "Default")
      (node (ref "R47") (pin "1") (pinfunction "1_1") (pintype "passive"))
      (node (ref "U15") (pin "9") (pinfunction "SC1_9") (pintype "bidirectional"))
      (node (ref "U9") (pin "3") (pinfunction "SCL_3") (pintype "open_collector"))
    )
    (net (code "193") (name "Net-(U15-SD0)") (class "Default")
      (node (ref "R43") (pin "1") (pinfunction "1_1") (pintype "passive"))
      (node (ref "U15") (pin "5") (pinfunction "SD0_5") (pintype "bidirectional"))
      (node (ref "U8") (pin "4") (pinfunction "SDA_4") (pintype "open_collector"))
    )
    (net (code "194") (name "Net-(U15-SD1)") (class "Default")
      (node (ref "R46") (pin "1") (pinfunction "1_1") (pintype "passive"))
      (node (ref "U15") (pin "8") (pinfunction "SD1_8") (pintype "bidirectional"))
      (node (ref "U9") (pin "4") (pinfunction "SDA_4") (pintype "open_collector"))
    )
    (net (code "195") (name "Net-(U15-~{INT0})") (class "Default")
      (node (ref "R45") (pin "1") (pinfunction "1_1") (pintype "passive"))
      (node (ref "U15") (pin "4") (pinfunction "~{INT0}_4") (pintype "bidirectional"))
      (node (ref "U8") (pin "5") (pinfunction "~{ALERT}_5") (pintype "open_collector"))
    )
    (net (code "196") (name "Net-(U15-~{INT1})") (class "Default")
      (node (ref "R48") (pin "1") (pinfunction "1_1") (pintype "passive"))
      (node (ref "U15") (pin "7") (pinfunction "~{INT1}_7") (pintype "bidirectional"))
      (node (ref "U9") (pin "5") (pinfunction "~{ALERT}_5") (pintype "open_collector"))
    )
    (net (code "197") (name "Net-(U16-BIASH)") (class "Default")
      (node (ref "U16") (pin "28") (pinfunction "BIASH_28") (pintype "bidirectional"))
      (node (ref "U16") (pin "29") (pinfunction "BIASL_29") (pintype "bidirectional"))
    )
    (net (code "198") (name "Net-(U16-CAPH)") (class "Default")
      (node (ref "U16") (pin "25") (pinfunction "CAPH_25") (pintype "bidirectional"))
      (node (ref "U16") (pin "26") (pinfunction "CAPL_26") (pintype "bidirectional"))
    )
    (net (code "199") (name "Net-(U16-PA02)") (class "Default")
      (node (ref "R1") (pin "2") (pinfunction "2_2") (pintype "passive"))
      (node (ref "R71") (pin "1") (pinfunction "1_1") (pintype "passive"))
      (node (ref "U16") (pin "3") (pinfunction "PA02_3") (pintype "bidirectional"))
    )
    (net (code "200") (name "Net-(U21-D2+)") (class "Default")
      (node (ref "R12") (pin "1") (pinfunction "1_1") (pintype "passive"))
      (node (ref "U21") (pin "2") (pinfunction "D2+_2") (pintype "bidirectional"))
    )
    (net (code "201") (name "Net-(U21-D2-)") (class "Default")
      (node (ref "R13") (pin "1") (pinfunction "1_1") (pintype "passive"))
      (node (ref "U21") (pin "6") (pinfunction "D2-_6") (pintype "bidirectional"))
    )
    (net (code "202") (name "Net-(U22-D2+)") (class "Default")
      (node (ref "R14") (pin "1") (pinfunction "1_1") (pintype "passive"))
      (node (ref "U22") (pin "2") (pinfunction "D2+_2") (pintype "bidirectional"))
    )
    (net (code "203") (name "Net-(U22-D2-)") (class "Default")
      (node (ref "R15") (pin "1") (pinfunction "1_1") (pintype "passive"))
      (node (ref "U22") (pin "6") (pinfunction "D2-_6") (pintype "bidirectional"))
    )
    (net (code "204") (name "Net-(U23-S)") (class "Default")
      (node (ref "Q1") (pin "D2") (pinfunction "D2_D2") (pintype "bidirectional"))
      (node (ref "R89") (pin "1") (pinfunction "1_1") (pintype "passive"))
      (node (ref "U23") (pin "10") (pinfunction "S_10") (pintype "bidirectional"))
    )
    (net (code "205") (name "Net-(U24-DP0PUR)") (class "Default")
      (node (ref "R40") (pin "2") (pinfunction "2_2") (pintype "passive"))
      (node (ref "U24") (pin "2") (pinfunction "DP0PUR_2") (pintype "bidirectional"))
    )
    (net (code "206") (name "Net-(U24-XTAL1)") (class "Default")
      (node (ref "C3") (pin "2") (pinfunction "2_2") (pintype "bidirectional"))
      (node (ref "U24") (pin "45") (pinfunction "XTAL1_45") (pintype "bidirectional"))
      (node (ref "Y1") (pin "3") (pinfunction "2_3") (pintype "bidirectional"))
    )
    (net (code "207") (name "Net-(U24-XTAL2)") (class "Default")
      (node (ref "R41") (pin "2") (pinfunction "2_2") (pintype "passive"))
      (node (ref "U24") (pin "44") (pinfunction "XTAL2_44") (pintype "bidirectional"))
    )
    (net (code "208") (name "Net-(U25-~{PWRGD})") (class "Default")
      (node (ref "R105") (pin "1") (pinfunction "1_1") (pintype "passive"))
      (node (ref "U25") (pin "5") (pinfunction "~{PWRGD}_5") (pintype "bidirectional"))
    )
    (net (code "209") (name "PPS") (class "Default")
      (node (ref "J1") (pin "25") (pinfunction "PPS_25") (pintype "bidirectional"))
      (node (ref "TP10") (pin "TESTPOINT") (pinfunction "TESTPOINT_TESTPOINT") (pintype "bidirectional"))
      (node (ref "U16") (pin "37") (pinfunction "PA18_37") (pintype "bidirectional"))
      (node (ref "U17") (pin "3") (pinfunction "A2_3") (pintype "bidirectional"))
      (node (ref "U18") (pin "3") (pinfunction "A2_3") (pintype "bidirectional"))
    )
    (net (code "210") (name "PROG0_EN") (class "Default")
      (node (ref "R26") (pin "2") (pinfunction "2_2") (pintype "passive"))
      (node (ref "R31") (pin "2") (pinfunction "2_2") (pintype "passive"))
      (node (ref "S11") (pin "1") (pinfunction "A_1") (pintype "bidirectional"))
      (node (ref "S14") (pin "12") (pinfunction "CTRL_12") (pintype "bidirectional"))
      (node (ref "S14") (pin "13") (pinfunction "CTRL_13") (pintype "bidirectional"))
      (node (ref "S14") (pin "5") (pinfunction "CTRL_5") (pintype "bidirectional"))
      (node (ref "S14") (pin "6") (pinfunction "CTRL_6") (pintype "bidirectional"))
    )
    (net (code "211") (name "PROG1_EN") (class "Default")
      (node (ref "R27") (pin "2") (pinfunction "2_2") (pintype "passive"))
      (node (ref "R32") (pin "2") (pinfunction "2_2") (pintype "passive"))
      (node (ref "S11") (pin "2") (pinfunction "B_2") (pintype "bidirectional"))
      (node (ref "S15") (pin "12") (pinfunction "CTRL_12") (pintype "bidirectional"))
      (node (ref "S15") (pin "13") (pinfunction "CTRL_13") (pintype "bidirectional"))
      (node (ref "S15") (pin "5") (pinfunction "CTRL_5") (pintype "bidirectional"))
      (node (ref "S15") (pin "6") (pinfunction "CTRL_6") (pintype "bidirectional"))
    )
    (net (code "212") (name "PROG2_EN") (class "Default")
      (node (ref "R28") (pin "2") (pinfunction "2_2") (pintype "passive"))
      (node (ref "R34") (pin "2") (pinfunction "2_2") (pintype "passive"))
      (node (ref "S11") (pin "3") (pinfunction "C_3") (pintype "bidirectional"))
      (node (ref "S17") (pin "12") (pinfunction "CTRL_12") (pintype "bidirectional"))
      (node (ref "S17") (pin "13") (pinfunction "CTRL_13") (pintype "bidirectional"))
      (node (ref "S17") (pin "5") (pinfunction "CTRL_5") (pintype "bidirectional"))
      (node (ref "S17") (pin "6") (pinfunction "CTRL_6") (pintype "bidirectional"))
    )
    (net (code "213") (name "PROG3_EN") (class "Default")
      (node (ref "R29") (pin "2") (pinfunction "2_2") (pintype "passive"))
      (node (ref "R35") (pin "2") (pinfunction "2_2") (pintype "passive"))
      (node (ref "S11") (pin "4") (pinfunction "D_4") (pintype "bidirectional"))
      (node (ref "S18") (pin "12") (pinfunction "CTRL_12") (pintype "bidirectional"))
      (node (ref "S18") (pin "13") (pinfunction "CTRL_13") (pintype "bidirectional"))
      (node (ref "S18") (pin "5") (pinfunction "CTRL_5") (pintype "bidirectional"))
      (node (ref "S18") (pin "6") (pinfunction "CTRL_6") (pintype "bidirectional"))
    )
    (net (code "214") (name "PROG4_EN") (class "Default")
      (node (ref "R30") (pin "2") (pinfunction "2_2") (pintype "passive"))
      (node (ref "R33") (pin "2") (pinfunction "2_2") (pintype "passive"))
      (node (ref "S11") (pin "5") (pinfunction "E_5") (pintype "bidirectional"))
      (node (ref "S16") (pin "12") (pinfunction "CTRL_12") (pintype "bidirectional"))
      (node (ref "S16") (pin "13") (pinfunction "CTRL_13") (pintype "bidirectional"))
      (node (ref "S16") (pin "5") (pinfunction "CTRL_5") (pintype "bidirectional"))
      (node (ref "S16") (pin "6") (pinfunction "CTRL_6") (pintype "bidirectional"))
    )
    (net (code "215") (name "RADIO_RX") (class "Default")
      (node (ref "U1") (pin "30") (pinfunction "TXD_30") (pintype "output"))
      (node (ref "U16") (pin "23") (pinfunction "PA11_23") (pintype "bidirectional"))
    )
    (net (code "216") (name "RADIO_SWDCLK") (class "Default")
      (node (ref "R88") (pin "1") (pinfunction "1_1") (pintype "passive"))
      (node (ref "S16") (pin "3") (pinfunction "A_3") (pintype "bidirectional"))
      (node (ref "U16") (pin "9") (pinfunction "TCK_9") (pintype "bidirectional"))
    )
    (net (code "217") (name "RADIO_SWDIO") (class "Default")
      (node (ref "R87") (pin "1") (pinfunction "1_1") (pintype "passive"))
      (node (ref "S16") (pin "2") (pinfunction "A_2") (pintype "bidirectional"))
      (node (ref "U16") (pin "10") (pinfunction "PA03_10") (pintype "bidirectional"))
    )
    (net (code "218") (name "RADIO_TX") (class "Default")
      (node (ref "U1") (pin "2") (pinfunction "RXD_2") (pintype "input"))
      (node (ref "U16") (pin "24") (pinfunction "PA12_24") (pintype "bidirectional"))
    )
    (net (code "219") (name "RADIO_~{RESET}") (class "Default")
      (node (ref "S16") (pin "9") (pinfunction "A_9") (pintype "bidirectional"))
      (node (ref "S3") (pin "2") (pinfunction "P$2_2") (pintype "passive"))
      (node (ref "U16") (pin "4") (pinfunction "~{RESET}_4") (pintype "bidirectional"))
    )
    (net (code "220") (name "SMBCLK") (class "Default")
      (node (ref "J1") (pin "5") (pinfunction "SMBCLK_5") (pintype "bidirectional"))
      (node (ref "R62") (pin "1") (pinfunction "1_1") (pintype "passive"))
      (node (ref "TP2") (pin "TESTPOINT") (pinfunction "TESTPOINT_TESTPOINT") (pintype "bidirectional"))
      (node (ref "U13") (pin "19") (pinfunction "SCL_19") (pintype "bidirectional"))
      (node (ref "U14") (pin "19") (pinfunction "SCL_19") (pintype "bidirectional"))
      (node (ref "U15") (pin "18") (pinfunction "SCL_18") (pintype "bidirectional"))
    )
    (net (code "221") (name "SMBDATA") (class "Default")
      (node (ref "J1") (pin "3") (pinfunction "SMBDATA_3") (pintype "bidirectional"))
      (node (ref "R61") (pin "1") (pinfunction "1_1") (pintype "passive"))
      (node (ref "TP1") (pin "TESTPOINT") (pinfunction "TESTPOINT_TESTPOINT") (pintype "bidirectional"))
      (node (ref "U13") (pin "20") (pinfunction "SDA_20") (pintype "bidirectional"))
      (node (ref "U14") (pin "20") (pinfunction "SDA_20") (pintype "bidirectional"))
      (node (ref "U15") (pin "19") (pinfunction "SDA_19") (pintype "bidirectional"))
    )
    (net (code "222") (name "USB+") (class "Default")
      (node (ref "R40") (pin "1") (pinfunction "1_1") (pintype "passive"))
      (node (ref "U23") (pin "3") (pinfunction "D+_3") (pintype "bidirectional"))
      (node (ref "U24") (pin "3") (pinfunction "DP0_3") (pintype "bidirectional"))
    )
    (net (code "223") (name "USB-") (class "Default")
      (node (ref "U23") (pin "5") (pinfunction "D-_5") (pintype "bidirectional"))
      (node (ref "U24") (pin "4") (pinfunction "DM0_4") (pintype "bidirectional"))
    )
    (net (code "224") (name "USB_SUSPEND_STATUS") (class "Default")
      (node (ref "TP31") (pin "TESTPOINT") (pinfunction "TESTPOINT_TESTPOINT") (pintype "bidirectional"))
      (node (ref "U24") (pin "1") (pinfunction "SUSPND_1") (pintype "bidirectional"))
    )
    (net (code "225") (name "VCC_BACKPLANE") (class "Default")
      (node (ref "C12") (pin "1") (pinfunction "1_1") (pintype "bidirectional"))
      (node (ref "C16") (pin "1") (pinfunction "1_1") (pintype "bidirectional"))
      (node (ref "C17") (pin "1") (pinfunction "1_1") (pintype "bidirectional"))
      (node (ref "C20") (pin "1") (pinfunction "1_1") (pintype "bidirectional"))
      (node (ref "C21") (pin "1") (pinfunction "1_1") (pintype "bidirectional"))
      (node (ref "C22") (pin "1") (pinfunction "1_1") (pintype "bidirectional"))
      (node (ref "C23") (pin "1") (pinfunction "1_1") (pintype "bidirectional"))
      (node (ref "C28") (pin "2") (pinfunction "2_2") (pintype "bidirectional"))
      (node (ref "C29") (pin "1") (pinfunction "1_1") (pintype "bidirectional"))
      (node (ref "C30") (pin "1") (pinfunction "1_1") (pintype "bidirectional"))
      (node (ref "C33") (pin "1") (pinfunction "1_1") (pintype "bidirectional"))
      (node (ref "C34") (pin "1") (pinfunction "1_1") (pintype "bidirectional"))
      (node (ref "C37") (pin "2") (pinfunction "2_2") (pintype "bidirectional"))
      (node (ref "C38") (pin "2") (pinfunction "2_2") (pintype "bidirectional"))
      (node (ref "C61") (pin "2") (pinfunction "2_2") (pintype "bidirectional"))
      (node (ref "C66") (pin "2") (pinfunction "2_2") (pintype "bidirectional"))
      (node (ref "J1") (pin "2") (pinfunction "VCC_CONTROLLER_2") (pintype "bidirectional"))
      (node (ref "R2") (pin "1") (pinfunction "1_1") (pintype "passive"))
      (node (ref "R42") (pin "1") (pinfunction "1_1") (pintype "passive"))
      (node (ref "R55") (pin "2") (pinfunction "2_2") (pintype "passive"))
      (node (ref "R56") (pin "2") (pinfunction "2_2") (pintype "passive"))
      (node (ref "R61") (pin "2") (pinfunction "2_2") (pintype "passive"))
      (node (ref "R62") (pin "2") (pinfunction "2_2") (pintype "passive"))
      (node (ref "R63") (pin "2") (pinfunction "2_2") (pintype "passive"))
      (node (ref "R64") (pin "2") (pinfunction "2_2") (pintype "passive"))
      (node (ref "R65") (pin "2") (pinfunction "2_2") (pintype "passive"))
      (node (ref "R66") (pin "2") (pinfunction "2_2") (pintype "passive"))
      (node (ref "R67") (pin "2") (pinfunction "2_2") (pintype "passive"))
      (node (ref "R68") (pin "2") (pinfunction "2_2") (pintype "passive"))
      (node (ref "R69") (pin "2") (pinfunction "2_2") (pintype "passive"))
      (node (ref "R72") (pin "2") (pinfunction "2_2") (pintype "passive"))
      (node (ref "R89") (pin "2") (pinfunction "2_2") (pintype "passive"))
      (node (ref "S10") (pin "3") (pinfunction "I0_3") (pintype "bidirectional"))
      (node (ref "S10") (pin "5") (pinfunction "VCC_5") (pintype "bidirectional"))
      (node (ref "S9") (pin "3") (pinfunction "I0_3") (pintype "bidirectional"))
      (node (ref "S9") (pin "5") (pinfunction "VCC_5") (pintype "bidirectional"))
      (node (ref "TP24") (pin "TESTPOINT") (pinfunction "TESTPOINT_TESTPOINT") (pintype "bidirectional"))
      (node (ref "TP8") (pin "TESTPOINT") (pinfunction "TESTPOINT_TESTPOINT") (pintype "bidirectional"))
      (node (ref "U13") (pin "18") (pinfunction "VCC_18") (pintype "bidirectional"))
      (node (ref "U14") (pin "18") (pinfunction "VCC_18") (pintype "bidirectional"))
      (node (ref "U14") (pin "3") (pinfunction "A0_3") (pintype "bidirectional"))
      (node (ref "U15") (pin "20") (pinfunction "VCC_20") (pintype "bidirectional"))
      (node (ref "U17") (pin "1") (pinfunction "VCC_A_1") (pintype "bidirectional"))
      (node (ref "U17") (pin "5") (pinfunction "DIR_5") (pintype "bidirectional"))
      (node (ref "U18") (pin "1") (pinfunction "VCC_A_1") (pintype "bidirectional"))
      (node (ref "U18") (pin "5") (pinfunction "DIR_5") (pintype "bidirectional"))
      (node (ref "U19") (pin "1") (pinfunction "VCC_A_1") (pintype "bidirectional"))
      (node (ref "U20") (pin "1") (pinfunction "VCC_A_1") (pintype "bidirectional"))
      (node (ref "U21") (pin "9") (pinfunction "VCC_9") (pintype "bidirectional"))
      (node (ref "U22") (pin "9") (pinfunction "VCC_9") (pintype "bidirectional"))
      (node (ref "U23") (pin "9") (pinfunction "VCC_9") (pintype "bidirectional"))
      (node (ref "U24") (pin "46") (pinfunction "VCC_46") (pintype "bidirectional"))
      (node (ref "U24") (pin "47") (pinfunction "~{EXTMEM}_47") (pintype "bidirectional"))
      (node (ref "U24") (pin "8") (pinfunction "EEDATA/~{GANGED}_8") (pintype "bidirectional"))
      (node (ref "U24") (pin "9") (pinfunction "VCC_9") (pintype "bidirectional"))
      (node (ref "U6") (pin "1") (pinfunction "VCC_A_1") (pintype "bidirectional"))
      (node (ref "U7") (pin "1") (pinfunction "VCC_A_1") (pintype "bidirectional"))
      (node (ref "U8") (pin "6") (pinfunction "SENSE-_6") (pintype "open_collector"))
    )
    (net (code "226") (name "VCC_LINUX") (class "Default")
      (node (ref "C13") (pin "1") (pinfunction "1_1") (pintype "bidirectional"))
      (node (ref "J1") (pin "4") (pinfunction "VCC_LINUX_4") (pintype "bidirectional"))
      (node (ref "R3") (pin "1") (pinfunction "1_1") (pintype "passive"))
      (node (ref "TP18") (pin "TESTPOINT") (pinfunction "TESTPOINT_TESTPOINT") (pintype "bidirectional"))
      (node (ref "TP23") (pin "TESTPOINT") (pinfunction "TESTPOINT_TESTPOINT") (pintype "bidirectional"))
      (node (ref "U9") (pin "6") (pinfunction "SENSE-_6") (pintype "open_collector"))
    )
    (net (code "227") (name "unconnected-(D7-C-Pad2)") (class "Default")
      (node (ref "D7") (pin "2") (pinfunction "C_2") (pintype "bidirectional"))
    )
    (net (code "228") (name "unconnected-(D7-D-Pad4)") (class "Default")
      (node (ref "D7") (pin "4") (pinfunction "D_4") (pintype "bidirectional"))
    )
    (net (code "229") (name "unconnected-(J1B-MOD5_IN-Pad15)") (class "Default")
      (node (ref "J1") (pin "15") (pinfunction "MOD5_IN_15") (pintype "bidirectional"))
    )
    (net (code "230") (name "unconnected-(J1B-MOD5_OUT-Pad16)") (class "Default")
      (node (ref "J1") (pin "16") (pinfunction "MOD5_OUT_16") (pintype "bidirectional"))
    )
    (net (code "231") (name "unconnected-(J1B-MOD6_IN-Pad17)") (class "Default")
      (node (ref "J1") (pin "17") (pinfunction "MOD6_IN_17") (pintype "bidirectional"))
    )
    (net (code "232") (name "unconnected-(J1B-MOD6_OUT-Pad18)") (class "Default")
      (node (ref "J1") (pin "18") (pinfunction "MOD6_OUT_18") (pintype "bidirectional"))
    )
    (net (code "233") (name "unconnected-(J1B-MOD7_IN-Pad19)") (class "Default")
      (node (ref "J1") (pin "19") (pinfunction "MOD7_IN_19") (pintype "bidirectional"))
    )
    (net (code "234") (name "unconnected-(J1B-MOD7_OUT-Pad20)") (class "Default")
      (node (ref "J1") (pin "20") (pinfunction "MOD7_OUT_20") (pintype "bidirectional"))
    )
    (net (code "235") (name "unconnected-(J4-ID-Pad4)") (class "Default")
      (node (ref "J4") (pin "4") (pinfunction "ID_4") (pintype "bidirectional"))
    )
    (net (code "236") (name "unconnected-(J5-ID-Pad4)") (class "Default")
      (node (ref "J5") (pin "4") (pinfunction "ID_4") (pintype "bidirectional"))
    )
    (net (code "237") (name "unconnected-(J6-ID-Pad4)") (class "Default")
      (node (ref "J6") (pin "4") (pinfunction "ID_4") (pintype "bidirectional"))
    )
    (net (code "238") (name "unconnected-(J7-ID-Pad4)") (class "Default")
      (node (ref "J7") (pin "4") (pinfunction "ID_4") (pintype "bidirectional"))
    )
    (net (code "239") (name "unconnected-(J8-ID-Pad4)") (class "Default")
      (node (ref "J8") (pin "4") (pinfunction "ID_4") (pintype "bidirectional"))
    )
    (net (code "240") (name "unconnected-(J9-ID-Pad4)") (class "Default")
      (node (ref "J9") (pin "4") (pinfunction "ID_4") (pintype "bidirectional"))
    )
    (net (code "241") (name "unconnected-(J10-Pad2)") (class "Default")
      (node (ref "J10") (pin "2") (pinfunction "2_2") (pintype "passive"))
    )
    (net (code "242") (name "unconnected-(J11-NC-Pad3)") (class "Default")
      (node (ref "J11") (pin "3") (pinfunction "NC_3") (pintype "bidirectional"))
    )
    (net (code "243") (name "unconnected-(Q1-PadD1)") (class "Default")
      (node (ref "Q1") (pin "D1") (pinfunction "D1_D1") (pintype "bidirectional"))
    )
    (net (code "244") (name "unconnected-(Q1-PadG1)") (class "Default")
      (node (ref "Q1") (pin "G1") (pinfunction "G1_G1") (pintype "input"))
    )
    (net (code "245") (name "unconnected-(S11-F-Pad6)") (class "Default")
      (node (ref "S11") (pin "6") (pinfunction "F_6") (pintype "bidirectional"))
    )
    (net (code "246") (name "unconnected-(S19-B-Pad2)") (class "Default")
      (node (ref "S19") (pin "2") (pinfunction "B_2") (pintype "bidirectional"))
    )
    (net (code "247") (name "unconnected-(U1-CBUS0-Pad22)") (class "Default")
      (node (ref "U1") (pin "22") (pinfunction "CBUS0_22") (pintype "bidirectional"))
    )
    (net (code "248") (name "unconnected-(U1-CBUS1-Pad21)") (class "Default")
      (node (ref "U1") (pin "21") (pinfunction "CBUS1_21") (pintype "bidirectional"))
    )
    (net (code "249") (name "unconnected-(U1-CBUS2-Pad10)") (class "Default")
      (node (ref "U1") (pin "10") (pinfunction "CBUS2_10") (pintype "bidirectional"))
    )
    (net (code "250") (name "unconnected-(U1-CBUS3-Pad11)") (class "Default")
      (node (ref "U1") (pin "11") (pinfunction "CBUS3_11") (pintype "bidirectional"))
    )
    (net (code "251") (name "unconnected-(U1-CBUS4-Pad9)") (class "Default")
      (node (ref "U1") (pin "9") (pinfunction "CBUS4_9") (pintype "bidirectional"))
    )
    (net (code "252") (name "unconnected-(U1-OSCI-Pad27)") (class "Default")
      (node (ref "U1") (pin "27") (pinfunction "OSCI_27") (pintype "input"))
    )
    (net (code "253") (name "unconnected-(U1-OSCO-Pad28)") (class "Default")
      (node (ref "U1") (pin "28") (pinfunction "OSCO_28") (pintype "output"))
    )
    (net (code "254") (name "unconnected-(U1-~{CTS}-Pad8)") (class "Default")
      (node (ref "U1") (pin "8") (pinfunction "~{CTS}_8") (pintype "input"))
    )
    (net (code "255") (name "unconnected-(U1-~{DCD}-Pad7)") (class "Default")
      (node (ref "U1") (pin "7") (pinfunction "~{DCD}_7") (pintype "input"))
    )
    (net (code "256") (name "unconnected-(U1-~{DSR}-Pad6)") (class "Default")
      (node (ref "U1") (pin "6") (pinfunction "~{DSR}_6") (pintype "input"))
    )
    (net (code "257") (name "unconnected-(U1-~{DTR}-Pad31)") (class "Default")
      (node (ref "U1") (pin "31") (pinfunction "~{DTR}_31") (pintype "output"))
    )
    (net (code "258") (name "unconnected-(U1-~{RESET}-Pad18)") (class "Default")
      (node (ref "U1") (pin "18") (pinfunction "~{RESET}_18") (pintype "input"))
    )
    (net (code "259") (name "unconnected-(U1-~{RI}-Pad3)") (class "Default")
      (node (ref "U1") (pin "3") (pinfunction "~{RI}_3") (pintype "input"))
    )
    (net (code "260") (name "unconnected-(U1-~{RTS}-Pad32)") (class "Default")
      (node (ref "U1") (pin "32") (pinfunction "~{RTS}_32") (pintype "output"))
    )
    (net (code "261") (name "unconnected-(U2-CBUS0-Pad22)") (class "Default")
      (node (ref "U2") (pin "22") (pinfunction "CBUS0_22") (pintype "bidirectional"))
    )
    (net (code "262") (name "unconnected-(U2-CBUS1-Pad21)") (class "Default")
      (node (ref "U2") (pin "21") (pinfunction "CBUS1_21") (pintype "bidirectional"))
    )
    (net (code "263") (name "unconnected-(U2-CBUS2-Pad10)") (class "Default")
      (node (ref "U2") (pin "10") (pinfunction "CBUS2_10") (pintype "bidirectional"))
    )
    (net (code "264") (name "unconnected-(U2-CBUS3-Pad11)") (class "Default")
      (node (ref "U2") (pin "11") (pinfunction "CBUS3_11") (pintype "bidirectional"))
    )
    (net (code "265") (name "unconnected-(U2-CBUS4-Pad9)") (class "Default")
      (node (ref "U2") (pin "9") (pinfunction "CBUS4_9") (pintype "bidirectional"))
    )
    (net (code "266") (name "unconnected-(U2-OSCI-Pad27)") (class "Default")
      (node (ref "U2") (pin "27") (pinfunction "OSCI_27") (pintype "input"))
    )
    (net (code "267") (name "unconnected-(U2-OSCO-Pad28)") (class "Default")
      (node (ref "U2") (pin "28") (pinfunction "OSCO_28") (pintype "output"))
    )
    (net (code "268") (name "unconnected-(U2-~{CTS}-Pad8)") (class "Default")
      (node (ref "U2") (pin "8") (pinfunction "~{CTS}_8") (pintype "input"))
    )
    (net (code "269") (name "unconnected-(U2-~{DCD}-Pad7)") (class "Default")
      (node (ref "U2") (pin "7") (pinfunction "~{DCD}_7") (pintype "input"))
    )
    (net (code "270") (name "unconnected-(U2-~{DSR}-Pad6)") (class "Default")
      (node (ref "U2") (pin "6") (pinfunction "~{DSR}_6") (pintype "input"))
    )
    (net (code "271") (name "unconnected-(U2-~{DTR}-Pad31)") (class "Default")
      (node (ref "U2") (pin "31") (pinfunction "~{DTR}_31") (pintype "output"))
    )
    (net (code "272") (name "unconnected-(U2-~{RESET}-Pad18)") (class "Default")
      (node (ref "U2") (pin "18") (pinfunction "~{RESET}_18") (pintype "input"))
    )
    (net (code "273") (name "unconnected-(U2-~{RI}-Pad3)") (class "Default")
      (node (ref "U2") (pin "3") (pinfunction "~{RI}_3") (pintype "input"))
    )
    (net (code "274") (name "unconnected-(U2-~{RTS}-Pad32)") (class "Default")
      (node (ref "U2") (pin "32") (pinfunction "~{RTS}_32") (pintype "output"))
    )
    (net (code "275") (name "unconnected-(U3-CBUS0-Pad22)") (class "Default")
      (node (ref "U3") (pin "22") (pinfunction "CBUS0_22") (pintype "bidirectional"))
    )
    (net (code "276") (name "unconnected-(U3-CBUS1-Pad21)") (class "Default")
      (node (ref "U3") (pin "21") (pinfunction "CBUS1_21") (pintype "bidirectional"))
    )
    (net (code "277") (name "unconnected-(U3-CBUS2-Pad10)") (class "Default")
      (node (ref "U3") (pin "10") (pinfunction "CBUS2_10") (pintype "bidirectional"))
    )
    (net (code "278") (name "unconnected-(U3-CBUS3-Pad11)") (class "Default")
      (node (ref "U3") (pin "11") (pinfunction "CBUS3_11") (pintype "bidirectional"))
    )
    (net (code "279") (name "unconnected-(U3-CBUS4-Pad9)") (class "Default")
      (node (ref "U3") (pin "9") (pinfunction "CBUS4_9") (pintype "bidirectional"))
    )
    (net (code "280") (name "unconnected-(U3-OSCI-Pad27)") (class "Default")
      (node (ref "U3") (pin "27") (pinfunction "OSCI_27") (pintype "input"))
    )
    (net (code "281") (name "unconnected-(U3-OSCO-Pad28)") (class "Default")
      (node (ref "U3") (pin "28") (pinfunction "OSCO_28") (pintype "output"))
    )
    (net (code "282") (name "unconnected-(U3-~{CTS}-Pad8)") (class "Default")
      (node (ref "U3") (pin "8") (pinfunction "~{CTS}_8") (pintype "input"))
    )
    (net (code "283") (name "unconnected-(U3-~{DCD}-Pad7)") (class "Default")
      (node (ref "U3") (pin "7") (pinfunction "~{DCD}_7") (pintype "input"))
    )
    (net (code "284") (name "unconnected-(U3-~{DSR}-Pad6)") (class "Default")
      (node (ref "U3") (pin "6") (pinfunction "~{DSR}_6") (pintype "input"))
    )
    (net (code "285") (name "unconnected-(U3-~{DTR}-Pad31)") (class "Default")
      (node (ref "U3") (pin "31") (pinfunction "~{DTR}_31") (pintype "output"))
    )
    (net (code "286") (name "unconnected-(U3-~{RESET}-Pad18)") (class "Default")
      (node (ref "U3") (pin "18") (pinfunction "~{RESET}_18") (pintype "input"))
    )
    (net (code "287") (name "unconnected-(U3-~{RI}-Pad3)") (class "Default")
      (node (ref "U3") (pin "3") (pinfunction "~{RI}_3") (pintype "input"))
    )
    (net (code "288") (name "unconnected-(U3-~{RTS}-Pad32)") (class "Default")
      (node (ref "U3") (pin "32") (pinfunction "~{RTS}_32") (pintype "output"))
    )
    (net (code "289") (name "unconnected-(U4-CBUS0-Pad22)") (class "Default")
      (node (ref "U4") (pin "22") (pinfunction "CBUS0_22") (pintype "bidirectional"))
    )
    (net (code "290") (name "unconnected-(U4-CBUS1-Pad21)") (class "Default")
      (node (ref "U4") (pin "21") (pinfunction "CBUS1_21") (pintype "bidirectional"))
    )
    (net (code "291") (name "unconnected-(U4-CBUS2-Pad10)") (class "Default")
      (node (ref "U4") (pin "10") (pinfunction "CBUS2_10") (pintype "bidirectional"))
    )
    (net (code "292") (name "unconnected-(U4-CBUS3-Pad11)") (class "Default")
      (node (ref "U4") (pin "11") (pinfunction "CBUS3_11") (pintype "bidirectional"))
    )
    (net (code "293") (name "unconnected-(U4-CBUS4-Pad9)") (class "Default")
      (node (ref "U4") (pin "9") (pinfunction "CBUS4_9") (pintype "bidirectional"))
    )
    (net (code "294") (name "unconnected-(U4-OSCI-Pad27)") (class "Default")
      (node (ref "U4") (pin "27") (pinfunction "OSCI_27") (pintype "input"))
    )
    (net (code "295") (name "unconnected-(U4-OSCO-Pad28)") (class "Default")
      (node (ref "U4") (pin "28") (pinfunction "OSCO_28") (pintype "output"))
    )
    (net (code "296") (name "unconnected-(U4-~{CTS}-Pad8)") (class "Default")
      (node (ref "U4") (pin "8") (pinfunction "~{CTS}_8") (pintype "input"))
    )
    (net (code "297") (name "unconnected-(U4-~{DCD}-Pad7)") (class "Default")
      (node (ref "U4") (pin "7") (pinfunction "~{DCD}_7") (pintype "input"))
    )
    (net (code "298") (name "unconnected-(U4-~{DSR}-Pad6)") (class "Default")
      (node (ref "U4") (pin "6") (pinfunction "~{DSR}_6") (pintype "input"))
    )
    (net (code "299") (name "unconnected-(U4-~{DTR}-Pad31)") (class "Default")
      (node (ref "U4") (pin "31") (pinfunction "~{DTR}_31") (pintype "output"))
    )
    (net (code "300") (name "unconnected-(U4-~{RESET}-Pad18)") (class "Default")
      (node (ref "U4") (pin "18") (pinfunction "~{RESET}_18") (pintype "input"))
    )
    (net (code "301") (name "unconnected-(U4-~{RI}-Pad3)") (class "Default")
      (node (ref "U4") (pin "3") (pinfunction "~{RI}_3") (pintype "input"))
    )
    (net (code "302") (name "unconnected-(U4-~{RTS}-Pad32)") (class "Default")
      (node (ref "U4") (pin "32") (pinfunction "~{RTS}_32") (pintype "output"))
    )
    (net (code "303") (name "unconnected-(U5-CBUS0-Pad22)") (class "Default")
      (node (ref "U5") (pin "22") (pinfunction "CBUS0_22") (pintype "bidirectional"))
    )
    (net (code "304") (name "unconnected-(U5-CBUS1-Pad21)") (class "Default")
      (node (ref "U5") (pin "21") (pinfunction "CBUS1_21") (pintype "bidirectional"))
    )
    (net (code "305") (name "unconnected-(U5-CBUS2-Pad10)") (class "Default")
      (node (ref "U5") (pin "10") (pinfunction "CBUS2_10") (pintype "bidirectional"))
    )
    (net (code "306") (name "unconnected-(U5-CBUS3-Pad11)") (class "Default")
      (node (ref "U5") (pin "11") (pinfunction "CBUS3_11") (pintype "bidirectional"))
    )
    (net (code "307") (name "unconnected-(U5-CBUS4-Pad9)") (class "Default")
      (node (ref "U5") (pin "9") (pinfunction "CBUS4_9") (pintype "bidirectional"))
    )
    (net (code "308") (name "unconnected-(U5-OSCI-Pad27)") (class "Default")
      (node (ref "U5") (pin "27") (pinfunction "OSCI_27") (pintype "input"))
    )
    (net (code "309") (name "unconnected-(U5-OSCO-Pad28)") (class "Default")
      (node (ref "U5") (pin "28") (pinfunction "OSCO_28") (pintype "output"))
    )
    (net (code "310") (name "unconnected-(U5-~{CTS}-Pad8)") (class "Default")
      (node (ref "U5") (pin "8") (pinfunction "~{CTS}_8") (pintype "input"))
    )
    (net (code "311") (name "unconnected-(U5-~{DCD}-Pad7)") (class "Default")
      (node (ref "U5") (pin "7") (pinfunction "~{DCD}_7") (pintype "input"))
    )
    (net (code "312") (name "unconnected-(U5-~{DSR}-Pad6)") (class "Default")
      (node (ref "U5") (pin "6") (pinfunction "~{DSR}_6") (pintype "input"))
    )
    (net (code "313") (name "unconnected-(U5-~{DTR}-Pad31)") (class "Default")
      (node (ref "U5") (pin "31") (pinfunction "~{DTR}_31") (pintype "output"))
    )
    (net (code "314") (name "unconnected-(U5-~{RESET}-Pad18)") (class "Default")
      (node (ref "U5") (pin "18") (pinfunction "~{RESET}_18") (pintype "input"))
    )
    (net (code "315") (name "unconnected-(U5-~{RI}-Pad3)") (class "Default")
      (node (ref "U5") (pin "3") (pinfunction "~{RI}_3") (pintype "input"))
    )
    (net (code "316") (name "unconnected-(U5-~{RTS}-Pad32)") (class "Default")
      (node (ref "U5") (pin "32") (pinfunction "~{RTS}_32") (pintype "output"))
    )
    (net (code "317") (name "unconnected-(U13-INT-Pad7)") (class "Default")
      (node (ref "U13") (pin "7") (pinfunction "INT_7") (pintype "bidirectional"))
    )
    (net (code "318") (name "unconnected-(U13-P3-Pad12)") (class "Default")
      (node (ref "U13") (pin "12") (pinfunction "P3_12") (pintype "bidirectional"))
    )
    (net (code "319") (name "unconnected-(U13-P4-Pad13)") (class "Default")
      (node (ref "U13") (pin "13") (pinfunction "P4_13") (pintype "bidirectional"))
    )
    (net (code "320") (name "unconnected-(U13-P5-Pad14)") (class "Default")
      (node (ref "U13") (pin "14") (pinfunction "P5_14") (pintype "bidirectional"))
    )
    (net (code "321") (name "unconnected-(U13-P6-Pad15)") (class "Default")
      (node (ref "U13") (pin "15") (pinfunction "P6_15") (pintype "bidirectional"))
    )
    (net (code "322") (name "unconnected-(U13-P7-Pad16)") (class "Default")
      (node (ref "U13") (pin "16") (pinfunction "P7_16") (pintype "bidirectional"))
    )
    (net (code "323") (name "unconnected-(U14-INT-Pad7)") (class "Default")
      (node (ref "U14") (pin "7") (pinfunction "INT_7") (pintype "bidirectional"))
    )
    (net (code "324") (name "unconnected-(U14-P3-Pad12)") (class "Default")
      (node (ref "U14") (pin "12") (pinfunction "P3_12") (pintype "bidirectional"))
    )
    (net (code "325") (name "unconnected-(U14-P4-Pad13)") (class "Default")
      (node (ref "U14") (pin "13") (pinfunction "P4_13") (pintype "bidirectional"))
    )
    (net (code "326") (name "unconnected-(U14-P5-Pad14)") (class "Default")
      (node (ref "U14") (pin "14") (pinfunction "P5_14") (pintype "bidirectional"))
    )
    (net (code "327") (name "unconnected-(U14-P6-Pad15)") (class "Default")
      (node (ref "U14") (pin "15") (pinfunction "P6_15") (pintype "bidirectional"))
    )
    (net (code "328") (name "unconnected-(U14-P7-Pad16)") (class "Default")
      (node (ref "U14") (pin "16") (pinfunction "P7_16") (pintype "bidirectional"))
    )
    (net (code "329") (name "unconnected-(U16-ADVREFP-Pad18)") (class "Default")
      (node (ref "U16") (pin "18") (pinfunction "ADVREFP_18") (pintype "bidirectional"))
    )
    (net (code "330") (name "unconnected-(U16-PA04-Pad11)") (class "Default")
      (node (ref "U16") (pin "11") (pinfunction "PA04_11") (pintype "bidirectional"))
    )
    (net (code "331") (name "unconnected-(U16-PA05-Pad12)") (class "Default")
      (node (ref "U16") (pin "12") (pinfunction "PA05_12") (pintype "bidirectional"))
    )
    (net (code "332") (name "unconnected-(U16-PA06-Pad15)") (class "Default")
      (node (ref "U16") (pin "15") (pinfunction "PA06_15") (pintype "bidirectional"))
    )
    (net (code "333") (name "unconnected-(U16-PA07-Pad16)") (class "Default")
      (node (ref "U16") (pin "16") (pinfunction "PA07_16") (pintype "bidirectional"))
    )
    (net (code "334") (name "unconnected-(U16-PA08-Pad20)") (class "Default")
      (node (ref "U16") (pin "20") (pinfunction "PA08_20") (pintype "bidirectional"))
    )
    (net (code "335") (name "unconnected-(U16-PA09-Pad21)") (class "Default")
      (node (ref "U16") (pin "21") (pinfunction "PA09_21") (pintype "bidirectional"))
    )
    (net (code "336") (name "unconnected-(U16-PA10-Pad22)") (class "Default")
      (node (ref "U16") (pin "22") (pinfunction "PA10_22") (pintype "bidirectional"))
    )
    (net (code "337") (name "unconnected-(U16-PA13-Pad32)") (class "Default")
      (node (ref "U16") (pin "32") (pinfunction "PA13_32") (pintype "bidirectional"))
    )
    (net (code "338") (name "unconnected-(U16-PA14-Pad33)") (class "Default")
      (node (ref "U16") (pin "33") (pinfunction "PA14_33") (pintype "bidirectional"))
    )
    (net (code "339") (name "unconnected-(U16-PA15-Pad34)") (class "Default")
      (node (ref "U16") (pin "34") (pinfunction "PA15_34") (pintype "bidirectional"))
    )
    (net (code "340") (name "unconnected-(U16-PA16-Pad35)") (class "Default")
      (node (ref "U16") (pin "35") (pinfunction "PA16_35") (pintype "bidirectional"))
    )
    (net (code "341") (name "unconnected-(U16-PA17-Pad36)") (class "Default")
      (node (ref "U16") (pin "36") (pinfunction "PA17_36") (pintype "bidirectional"))
    )
    (net (code "342") (name "unconnected-(U16-PA21-Pad41)") (class "Default")
      (node (ref "U16") (pin "41") (pinfunction "PA21_41") (pintype "bidirectional"))
    )
    (net (code "343") (name "unconnected-(U16-PA22-Pad42)") (class "Default")
      (node (ref "U16") (pin "42") (pinfunction "PA22_42") (pintype "bidirectional"))
    )
    (net (code "344") (name "unconnected-(U16-XIN32-Pad13)") (class "Default")
      (node (ref "U16") (pin "13") (pinfunction "XIN32_13") (pintype "bidirectional"))
    )
    (net (code "345") (name "unconnected-(U16-XOUT32-Pad14)") (class "Default")
      (node (ref "U16") (pin "14") (pinfunction "XOUT32_14") (pintype "bidirectional"))
    )
    (net (code "346") (name "unconnected-(U19-A2-Pad3)") (class "Default")
      (node (ref "U19") (pin "3") (pinfunction "A2_3") (pintype "bidirectional"))
    )
    (net (code "347") (name "unconnected-(U19-B2-Pad6)") (class "Default")
      (node (ref "U19") (pin "6") (pinfunction "B2_6") (pintype "bidirectional"))
    )
    (net (code "348") (name "unconnected-(U20-A2-Pad3)") (class "Default")
      (node (ref "U20") (pin "3") (pinfunction "A2_3") (pintype "bidirectional"))
    )
    (net (code "349") (name "unconnected-(U20-B2-Pad6)") (class "Default")
      (node (ref "U20") (pin "6") (pinfunction "B2_6") (pintype "bidirectional"))
    )
    (net (code "350") (name "unconnected-(U24-EECLK-Pad7)") (class "Default")
      (node (ref "U24") (pin "7") (pinfunction "EECLK_7") (pintype "bidirectional"))
    )
    (net (code "351") (name "~{BACKPLANE_RESET}") (class "Default")
      (node (ref "J1") (pin "22") (pinfunction "~{BACKPLANE_RESET}_22") (pintype "bidirectional"))
      (node (ref "R42") (pin "2") (pinfunction "2_2") (pintype "passive"))
      (node (ref "S8") (pin "2") (pinfunction "P$2_2") (pintype "passive"))
      (node (ref "TP9") (pin "TESTPOINT") (pinfunction "TESTPOINT_TESTPOINT") (pintype "bidirectional"))
      (node (ref "U13") (pin "4") (pinfunction "~{RESET}_4") (pintype "bidirectional"))
      (node (ref "U14") (pin "4") (pinfunction "~{RESET}_4") (pintype "bidirectional"))
      (node (ref "U24") (pin "6") (pinfunction "~{RESET}_6") (pintype "bidirectional"))
    )
    (net (code "352") (name "~{SMBALERT}") (class "Default")
      (node (ref "J1") (pin "6") (pinfunction "~{SMBALERT}_6") (pintype "bidirectional"))
      (node (ref "R63") (pin "1") (pinfunction "1_1") (pintype "passive"))
      (node (ref "TP3") (pin "TESTPOINT") (pinfunction "TESTPOINT_TESTPOINT") (pintype "bidirectional"))
      (node (ref "U15") (pin "17") (pinfunction "~{INT}_17") (pintype "bidirectional"))
    )
  )
)
